# CABLE_JIG_TEST_SCH.net
KiCad netlist of a schematic drawn in Altium Designer
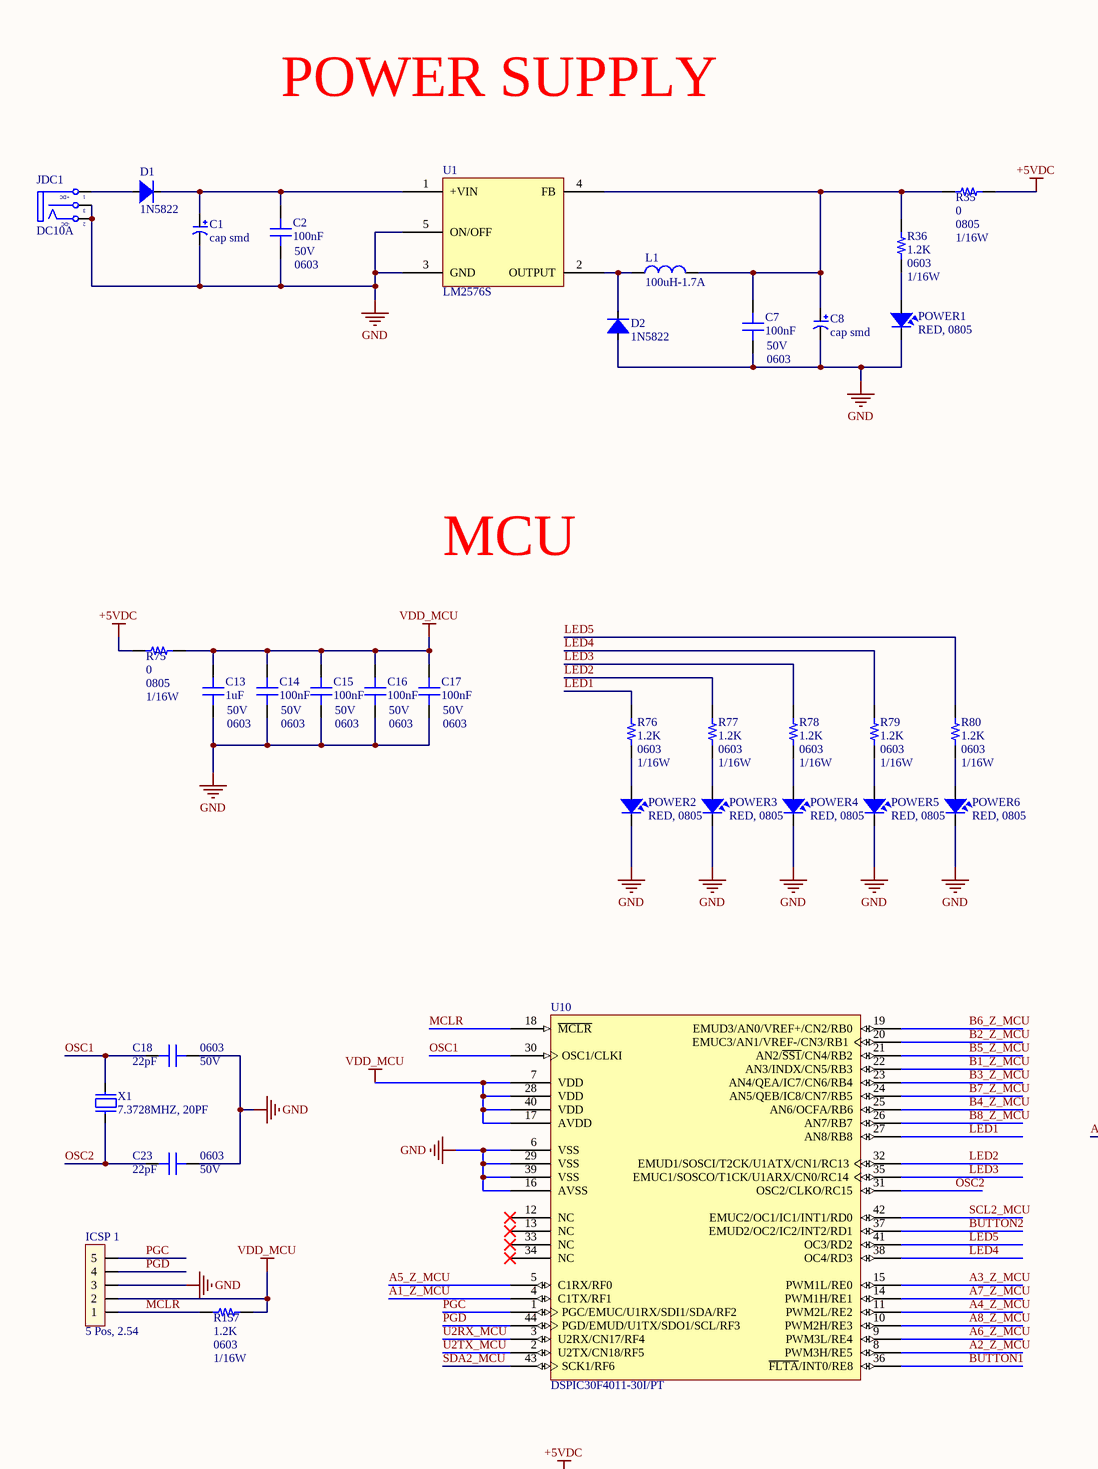
[diagram p0: CABLE_JIG_TEST_SCH.SchDoc, top left]
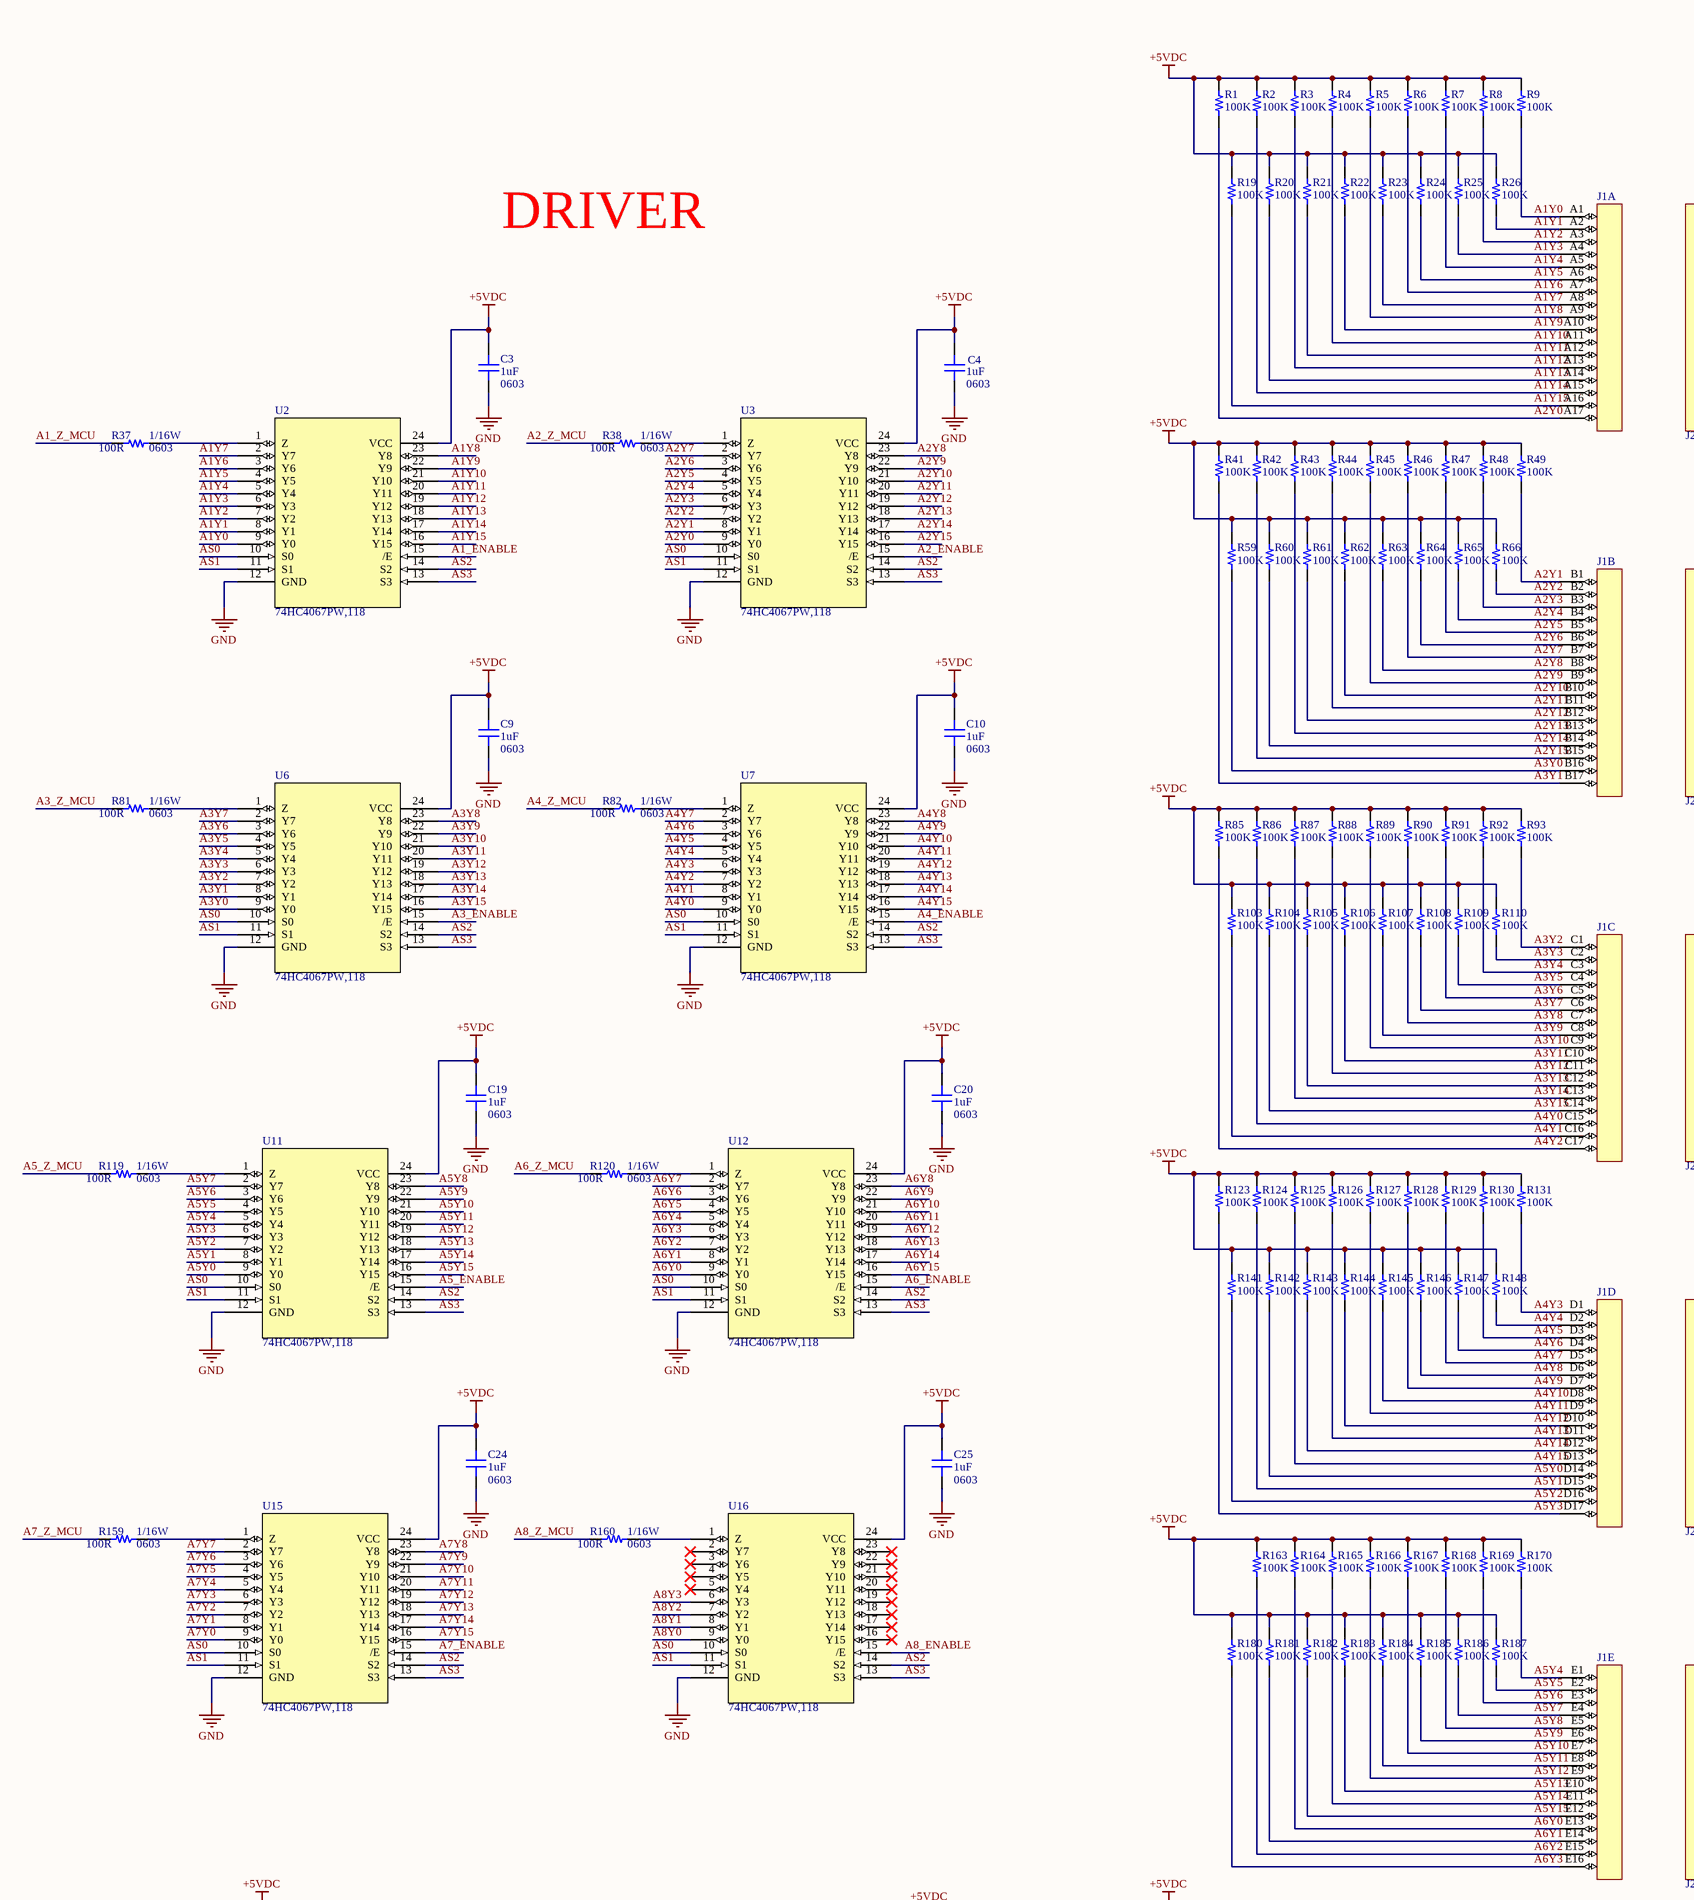
[diagram p1: CABLE_JIG_TEST_SCH.SchDoc, top middle]
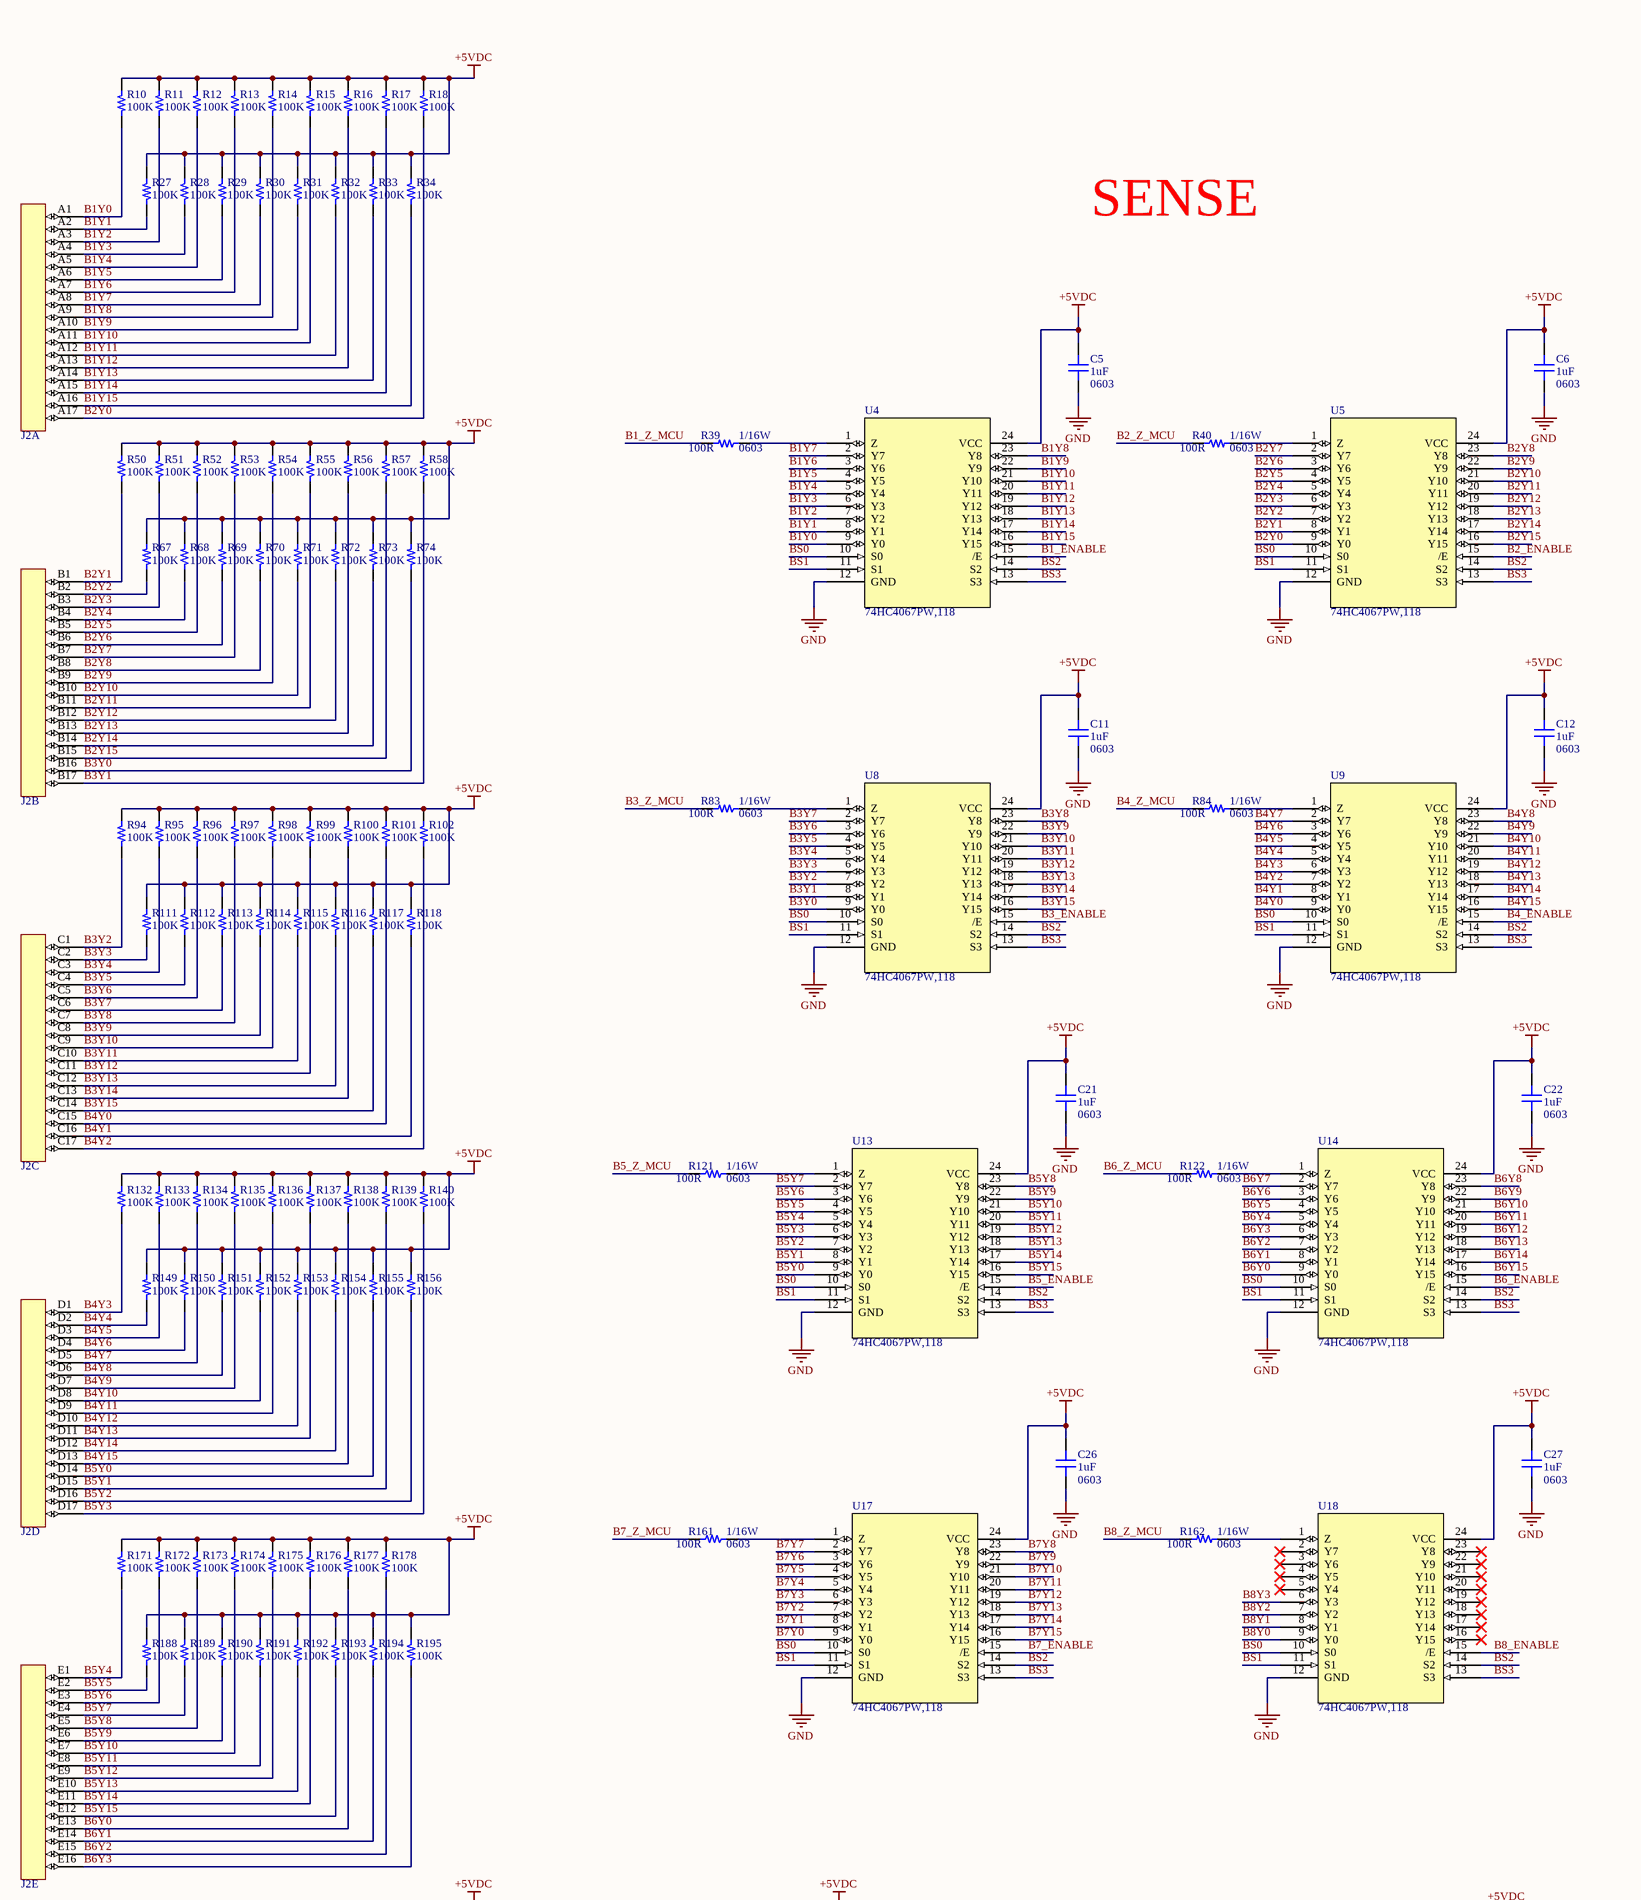
[diagram p2: CABLE_JIG_TEST_SCH.SchDoc, top right]
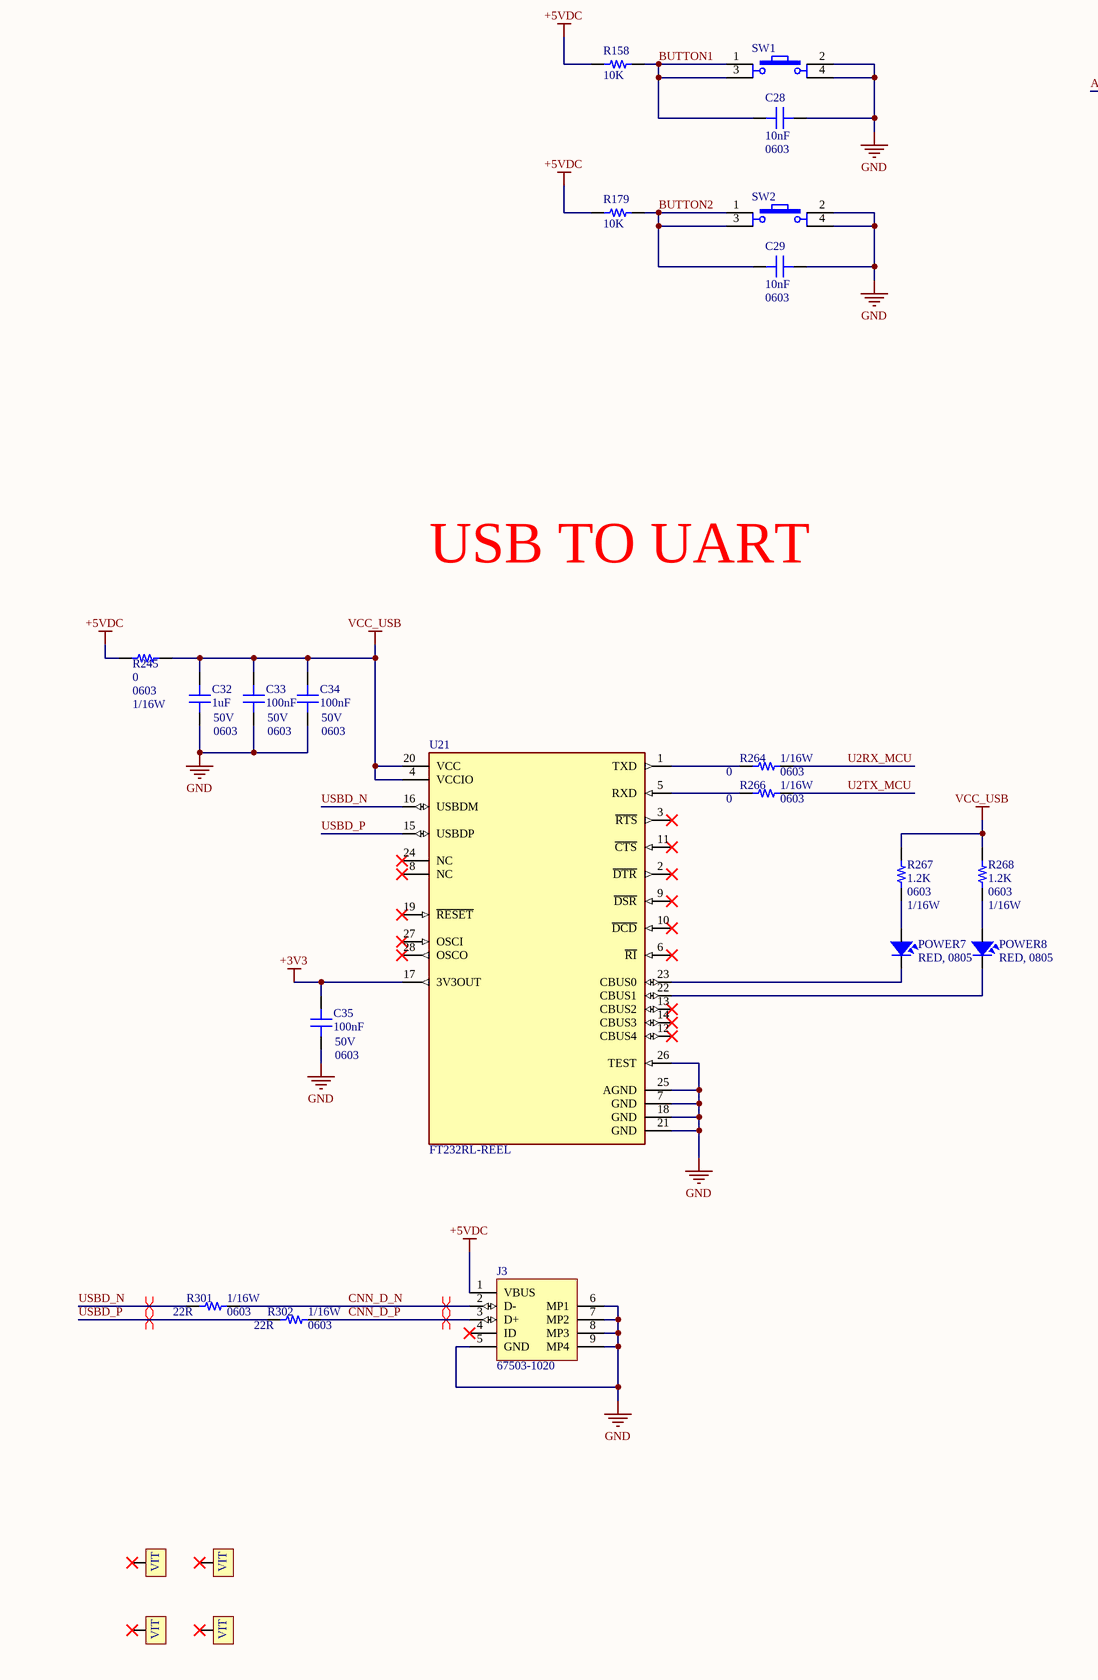
[diagram p3: CABLE_JIG_TEST_SCH.SchDoc, bottom left]
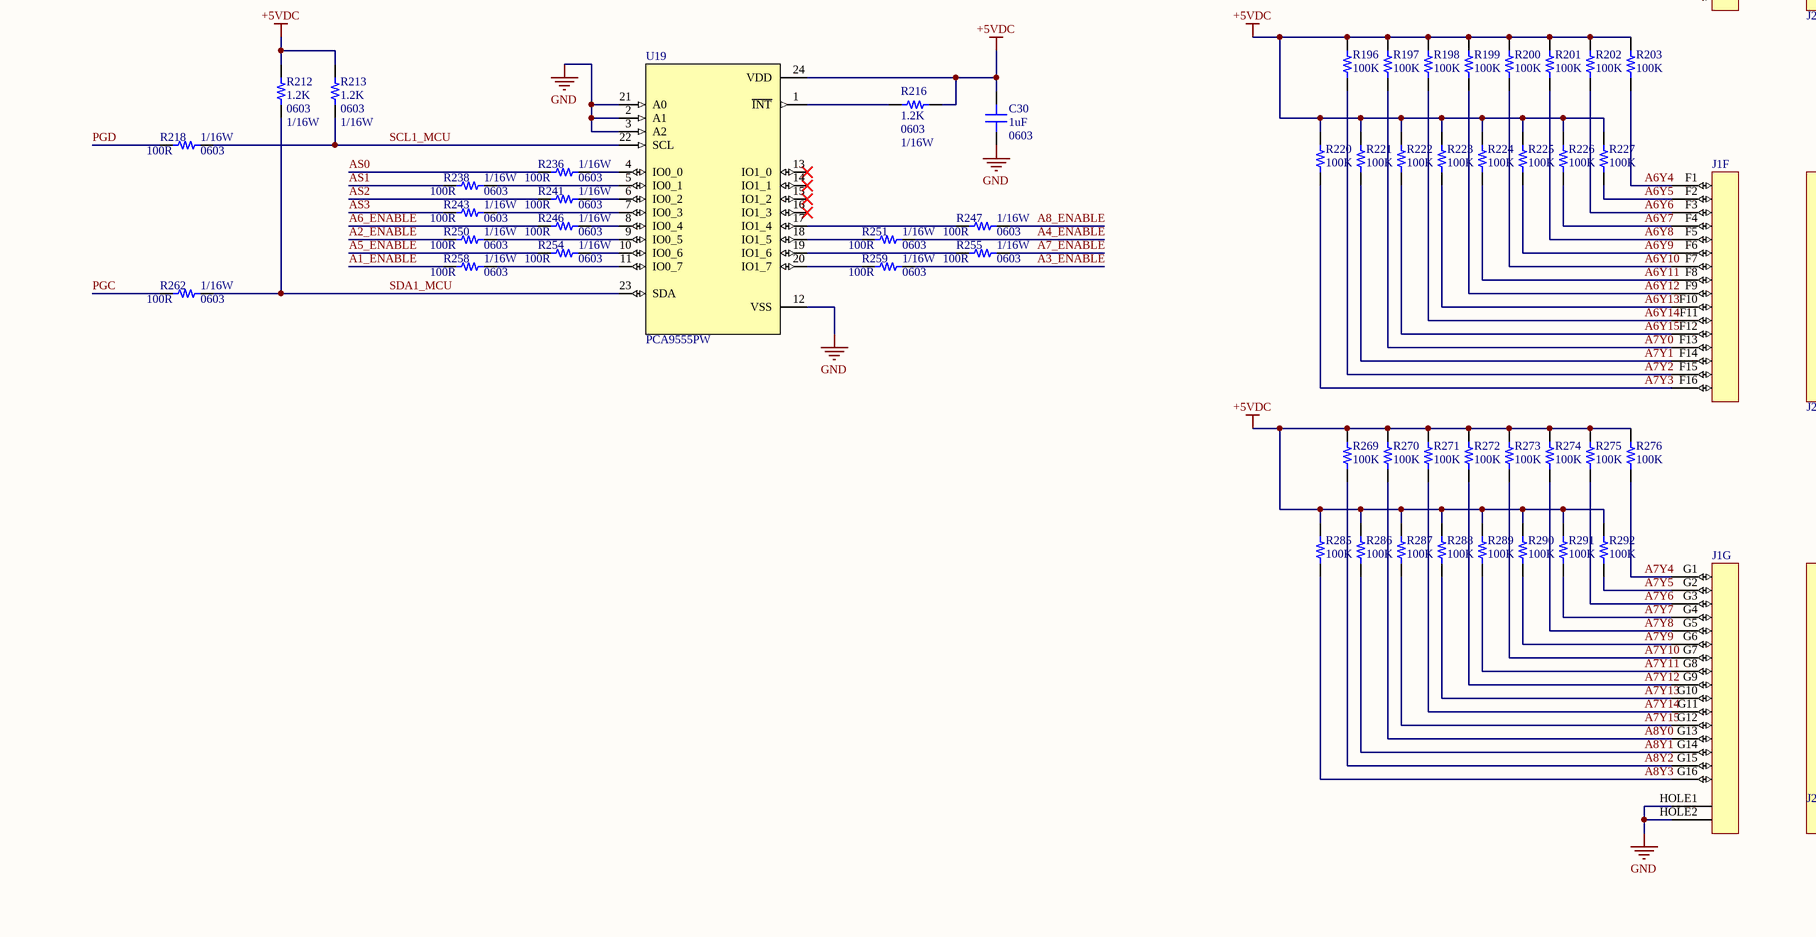
[diagram p4: CABLE_JIG_TEST_SCH.SchDoc, bottom middle]
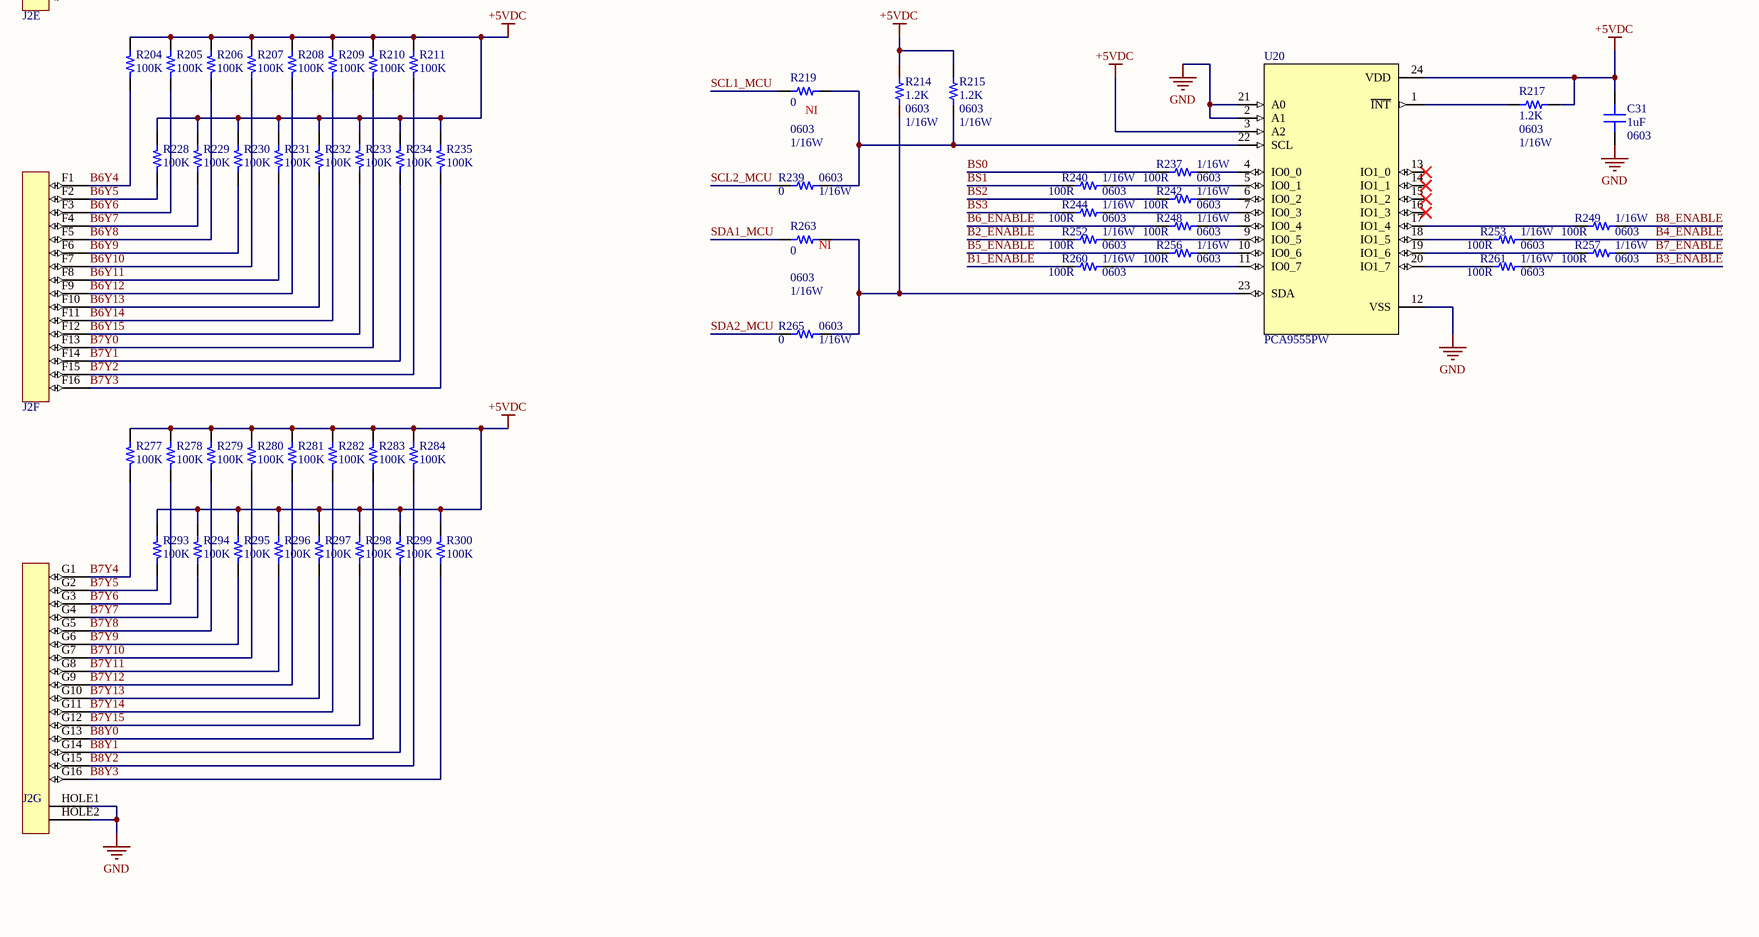
[diagram p5: CABLE_JIG_TEST_SCH.SchDoc, bottom right]

(export (version "E")
  (design (tool "Eeschema 10.0.6"))
  (components
    (comp (ref "C1")
      (value "cap smd")
      (footprint "Cap_SMD_10x10.5mm")
      (libsource (lib "DoraTek_Schematic.~(41)") (part "CAP_SMD"))
    )
    (comp (ref "C2")
      (value "100nF")
      (footprint "C0603N")
      (description "CAP CER 22UF 10V X5R 0603")
      (fields (field (name "PACKAGE") "0603") (field (name "VOLTAGE") "50V"))
      (libsource (lib "Altium_Component_Lib_Database") (part "CAP"))
    )
    (comp (ref "C3")
      (value "1uF")
      (footprint "C0603N")
      (description "CAP CER 22UF 10V X5R 0603")
      (fields (field (name "PACKAGE") "0603"))
      (libsource (lib "Altium_Component_Lib_Database") (part "CAP"))
    )
    (comp (ref "C4")
      (value "1uF")
      (footprint "C0603N")
      (description "CAP CER 22UF 10V X5R 0603")
      (fields (field (name "PACKAGE") "0603"))
      (libsource (lib "Altium_Component_Lib_Database") (part "CAP"))
    )
    (comp (ref "C5")
      (value "1uF")
      (footprint "C0603N")
      (description "CAP CER 22UF 10V X5R 0603")
      (fields (field (name "PACKAGE") "0603"))
      (libsource (lib "Altium_Component_Lib_Database") (part "CAP"))
    )
    (comp (ref "C6")
      (value "1uF")
      (footprint "C0603N")
      (description "CAP CER 22UF 10V X5R 0603")
      (fields (field (name "PACKAGE") "0603"))
      (libsource (lib "Altium_Component_Lib_Database") (part "CAP"))
    )
    (comp (ref "C7")
      (value "100nF")
      (footprint "C0603N")
      (description "CAP CER 22UF 10V X5R 0603")
      (fields (field (name "PACKAGE") "0603") (field (name "VOLTAGE") "50V"))
      (libsource (lib "Altium_Component_Lib_Database") (part "CAP"))
    )
    (comp (ref "C8")
      (value "cap smd")
      (footprint "Cap_SMD_10x10.5mm")
      (libsource (lib "DoraTek_Schematic.~(41)") (part "CAP_SMD"))
    )
    (comp (ref "C9")
      (value "1uF")
      (footprint "C0603N")
      (description "CAP CER 22UF 10V X5R 0603")
      (fields (field (name "PACKAGE") "0603"))
      (libsource (lib "Altium_Component_Lib_Database") (part "CAP"))
    )
    (comp (ref "C10")
      (value "1uF")
      (footprint "C0603N")
      (description "CAP CER 22UF 10V X5R 0603")
      (fields (field (name "PACKAGE") "0603"))
      (libsource (lib "Altium_Component_Lib_Database") (part "CAP"))
    )
    (comp (ref "C11")
      (value "1uF")
      (footprint "C0603N")
      (description "CAP CER 22UF 10V X5R 0603")
      (fields (field (name "PACKAGE") "0603"))
      (libsource (lib "Altium_Component_Lib_Database") (part "CAP"))
    )
    (comp (ref "C12")
      (value "1uF")
      (footprint "C0603N")
      (description "CAP CER 22UF 10V X5R 0603")
      (fields (field (name "PACKAGE") "0603"))
      (libsource (lib "Altium_Component_Lib_Database") (part "CAP"))
    )
    (comp (ref "C13")
      (value "1uF")
      (footprint "C0603N")
      (description "CAP CER 22UF 10V X5R 0603")
      (fields (field (name "PACKAGE") "0603") (field (name "VOLTAGE") "50V"))
      (libsource (lib "Altium_Component_Lib_Database") (part "CAP"))
    )
    (comp (ref "C14")
      (value "100nF")
      (footprint "C0603N")
      (description "CAP CER 22UF 10V X5R 0603")
      (fields (field (name "PACKAGE") "0603") (field (name "VOLTAGE") "50V"))
      (libsource (lib "Altium_Component_Lib_Database") (part "CAP"))
    )
    (comp (ref "C15")
      (value "100nF")
      (footprint "C0603N")
      (description "CAP CER 22UF 10V X5R 0603")
      (fields (field (name "PACKAGE") "0603") (field (name "VOLTAGE") "50V"))
      (libsource (lib "Altium_Component_Lib_Database") (part "CAP"))
    )
    (comp (ref "C16")
      (value "100nF")
      (footprint "C0603N")
      (description "CAP CER 22UF 10V X5R 0603")
      (fields (field (name "PACKAGE") "0603") (field (name "VOLTAGE") "50V"))
      (libsource (lib "Altium_Component_Lib_Database") (part "CAP"))
    )
    (comp (ref "C17")
      (value "100nF")
      (footprint "C0603N")
      (description "CAP CER 22UF 10V X5R 0603")
      (fields (field (name "PACKAGE") "0603") (field (name "VOLTAGE") "50V"))
      (libsource (lib "Altium_Component_Lib_Database") (part "CAP"))
    )
    (comp (ref "C18")
      (value "22pF")
      (footprint "C0603N")
      (description "CAP CER 22UF 10V X5R 0603")
      (fields (field (name "PACKAGE") "0603") (field (name "VOLTAGE") "50V"))
      (libsource (lib "Altium_Component_Lib_Database") (part "CAP"))
    )
    (comp (ref "C19")
      (value "1uF")
      (footprint "C0603N")
      (description "CAP CER 22UF 10V X5R 0603")
      (fields (field (name "PACKAGE") "0603"))
      (libsource (lib "Altium_Component_Lib_Database") (part "CAP"))
    )
    (comp (ref "C20")
      (value "1uF")
      (footprint "C0603N")
      (description "CAP CER 22UF 10V X5R 0603")
      (fields (field (name "PACKAGE") "0603"))
      (libsource (lib "Altium_Component_Lib_Database") (part "CAP"))
    )
    (comp (ref "C21")
      (value "1uF")
      (footprint "C0603N")
      (description "CAP CER 22UF 10V X5R 0603")
      (fields (field (name "PACKAGE") "0603"))
      (libsource (lib "Altium_Component_Lib_Database") (part "CAP"))
    )
    (comp (ref "C22")
      (value "1uF")
      (footprint "C0603N")
      (description "CAP CER 22UF 10V X5R 0603")
      (fields (field (name "PACKAGE") "0603"))
      (libsource (lib "Altium_Component_Lib_Database") (part "CAP"))
    )
    (comp (ref "C23")
      (value "22pF")
      (footprint "C0603N")
      (description "CAP CER 22UF 10V X5R 0603")
      (fields (field (name "PACKAGE") "0603") (field (name "VOLTAGE") "50V"))
      (libsource (lib "Altium_Component_Lib_Database") (part "CAP"))
    )
    (comp (ref "C24")
      (value "1uF")
      (footprint "C0603N")
      (description "CAP CER 22UF 10V X5R 0603")
      (fields (field (name "PACKAGE") "0603"))
      (libsource (lib "Altium_Component_Lib_Database") (part "CAP"))
    )
    (comp (ref "C25")
      (value "1uF")
      (footprint "C0603N")
      (description "CAP CER 22UF 10V X5R 0603")
      (fields (field (name "PACKAGE") "0603"))
      (libsource (lib "Altium_Component_Lib_Database") (part "CAP"))
    )
    (comp (ref "C26")
      (value "1uF")
      (footprint "C0603N")
      (description "CAP CER 22UF 10V X5R 0603")
      (fields (field (name "PACKAGE") "0603"))
      (libsource (lib "Altium_Component_Lib_Database") (part "CAP"))
    )
    (comp (ref "C27")
      (value "1uF")
      (footprint "C0603N")
      (description "CAP CER 22UF 10V X5R 0603")
      (fields (field (name "PACKAGE") "0603"))
      (libsource (lib "Altium_Component_Lib_Database") (part "CAP"))
    )
    (comp (ref "C28")
      (value "10nF")
      (footprint "C0603N")
      (description "CAP CER 22UF 10V X5R 0603")
      (fields (field (name "PACKAGE") "0603"))
      (libsource (lib "Altium_Component_Lib_Database") (part "CAP"))
    )
    (comp (ref "C29")
      (value "10nF")
      (footprint "C0603N")
      (description "CAP CER 22UF 10V X5R 0603")
      (fields (field (name "PACKAGE") "0603"))
      (libsource (lib "Altium_Component_Lib_Database") (part "CAP"))
    )
    (comp (ref "C30")
      (value "1uF")
      (footprint "C0603N")
      (description "CAP CER 22UF 10V X5R 0603")
      (fields (field (name "PACKAGE") "0603"))
      (libsource (lib "Altium_Component_Lib_Database") (part "CAP"))
    )
    (comp (ref "C31")
      (value "1uF")
      (footprint "C0603N")
      (description "CAP CER 22UF 10V X5R 0603")
      (fields (field (name "PACKAGE") "0603"))
      (libsource (lib "Altium_Component_Lib_Database") (part "CAP"))
    )
    (comp (ref "C32")
      (value "1uF")
      (footprint "C0603N")
      (description "CAP CER 22UF 10V X5R 0603")
      (fields (field (name "PACKAGE") "0603") (field (name "VOLTAGE") "50V"))
      (libsource (lib "Altium_Component_Lib_Database") (part "CAP"))
    )
    (comp (ref "C33")
      (value "100nF")
      (footprint "C0603N")
      (description "CAP CER 22UF 10V X5R 0603")
      (fields (field (name "PACKAGE") "0603") (field (name "VOLTAGE") "50V"))
      (libsource (lib "Altium_Component_Lib_Database") (part "CAP"))
    )
    (comp (ref "C34")
      (value "100nF")
      (footprint "C0603N")
      (description "CAP CER 22UF 10V X5R 0603")
      (fields (field (name "PACKAGE") "0603") (field (name "VOLTAGE") "50V"))
      (libsource (lib "Altium_Component_Lib_Database") (part "CAP"))
    )
    (comp (ref "C35")
      (value "100nF")
      (footprint "C0603N")
      (description "CAP CER 22UF 10V X5R 0603")
      (fields (field (name "PACKAGE") "0603") (field (name "VOLTAGE") "50V"))
      (libsource (lib "Altium_Component_Lib_Database") (part "CAP"))
    )
    (comp (ref "D1")
      (value "1N5822")
      (footprint "DO214 SMA")
      (description "SS34 1N5822")
      (libsource (lib "APESLAB") (part "Diode 1N5822"))
    )
    (comp (ref "D2")
      (value "1N5822")
      (footprint "DO214 SMA")
      (description "SS34 1N5822")
      (libsource (lib "APESLAB") (part "Diode 1N5822"))
    )
    (comp (ref "ICSP 1")
      (value "5 Pos, 2.54")
      (footprint "JP5")
      (description "CONN  WIRE-BOARD 5 POSITION, 2.54 mm")
      (libsource (lib "luong.nv1610") (part "3-644456-5"))
    )
    (comp (ref "J1")
      (value "CNN_CABLE_116PINS")
      (footprint "CNN_CABLE_116PINS")
      (libsource (lib "DoraTek_Schematic.~(41)") (part "CNN_CABLE_116PINS"))
    )
    (comp (ref "J2")
      (value "CNN_CABLE_116PINS")
      (footprint "CNN_CABLE_116PINS")
      (libsource (lib "") (part "CNN_CABLE_116PINS_1"))
    )
    (comp (ref "J3")
      (value "67503-1020")
      (footprint "MOLX-67503-1020_V")
      (description "USB, MINI, SMD, RA KME04-USBMU03A01")
      (fields (field (name "MANUFACTURER") "Molex"))
      (libsource (lib "DoraTek_Schematic.~(41)") (part "CNN_67503-1020"))
    )
    (comp (ref "JDC1")
      (value "DC10A")
      (footprint "DC-IN")
      (description "CLIFF ELECTRONIC COMPONENTS - DC10A - SOCKET, PCB, DC POWER, 2.1MM, PK10")
      (libsource (lib "luong.nv1610") (part "DC10A"))
    )
    (comp (ref "L1")
      (value "100uH-1.7A")
      (footprint "IND_SMD_12.5x12.5")
      (description "Inductor")
      (libsource (lib "DoraTek_Schematic.~(41)") (part "Inductor"))
    )
    (comp (ref "POWER1")
      (value "RED, 0805")
      (footprint "LED 0805")
      (description "LED, 0805, RED, 0805")
      (libsource (lib "luong.nv1610") (part "150080SS75000"))
    )
    (comp (ref "POWER2")
      (value "RED, 0805")
      (footprint "LED 0805")
      (description "LED, 0805, RED, 0805")
      (libsource (lib "luong.nv1610") (part "150080SS75000"))
    )
    (comp (ref "POWER3")
      (value "RED, 0805")
      (footprint "LED 0805")
      (description "LED, 0805, RED, 0805")
      (libsource (lib "luong.nv1610") (part "150080SS75000"))
    )
    (comp (ref "POWER4")
      (value "RED, 0805")
      (footprint "LED 0805")
      (description "LED, 0805, RED, 0805")
      (libsource (lib "luong.nv1610") (part "150080SS75000"))
    )
    (comp (ref "POWER5")
      (value "RED, 0805")
      (footprint "LED 0805")
      (description "LED, 0805, RED, 0805")
      (libsource (lib "luong.nv1610") (part "150080SS75000"))
    )
    (comp (ref "POWER6")
      (value "RED, 0805")
      (footprint "LED 0805")
      (description "LED, 0805, RED, 0805")
      (libsource (lib "luong.nv1610") (part "150080SS75000"))
    )
    (comp (ref "POWER7")
      (value "RED, 0805")
      (footprint "LED 0805")
      (description "LED, 0805, RED, 0805")
      (libsource (lib "luong.nv1610") (part "150080SS75000"))
    )
    (comp (ref "POWER8")
      (value "RED, 0805")
      (footprint "LED 0805")
      (description "LED, 0805, RED, 0805")
      (libsource (lib "luong.nv1610") (part "150080SS75000"))
    )
    (comp (ref "R1")
      (value "100K")
      (footprint "R0603N")
      (description "RES 0 OHM JUMPER 1/16W 0603")
      (fields (field (name "TOLERANCE") "Jumper"))
      (libsource (lib "Altium_Component_Lib_Database") (part "RES"))
    )
    (comp (ref "R2")
      (value "100K")
      (footprint "R0603N")
      (description "RES 0 OHM JUMPER 1/16W 0603")
      (fields (field (name "TOLERANCE") "Jumper"))
      (libsource (lib "Altium_Component_Lib_Database") (part "RES"))
    )
    (comp (ref "R3")
      (value "100K")
      (footprint "R0603N")
      (description "RES 0 OHM JUMPER 1/16W 0603")
      (fields (field (name "TOLERANCE") "Jumper"))
      (libsource (lib "Altium_Component_Lib_Database") (part "RES"))
    )
    (comp (ref "R4")
      (value "100K")
      (footprint "R0603N")
      (description "RES 0 OHM JUMPER 1/16W 0603")
      (fields (field (name "TOLERANCE") "Jumper"))
      (libsource (lib "Altium_Component_Lib_Database") (part "RES"))
    )
    (comp (ref "R5")
      (value "100K")
      (footprint "R0603N")
      (description "RES 0 OHM JUMPER 1/16W 0603")
      (fields (field (name "TOLERANCE") "Jumper"))
      (libsource (lib "Altium_Component_Lib_Database") (part "RES"))
    )
    (comp (ref "R6")
      (value "100K")
      (footprint "R0603N")
      (description "RES 0 OHM JUMPER 1/16W 0603")
      (fields (field (name "TOLERANCE") "Jumper"))
      (libsource (lib "Altium_Component_Lib_Database") (part "RES"))
    )
    (comp (ref "R7")
      (value "100K")
      (footprint "R0603N")
      (description "RES 0 OHM JUMPER 1/16W 0603")
      (fields (field (name "TOLERANCE") "Jumper"))
      (libsource (lib "Altium_Component_Lib_Database") (part "RES"))
    )
    (comp (ref "R8")
      (value "100K")
      (footprint "R0603N")
      (description "RES 0 OHM JUMPER 1/16W 0603")
      (fields (field (name "TOLERANCE") "Jumper"))
      (libsource (lib "Altium_Component_Lib_Database") (part "RES"))
    )
    (comp (ref "R9")
      (value "100K")
      (footprint "R0603N")
      (description "RES 0 OHM JUMPER 1/16W 0603")
      (fields (field (name "TOLERANCE") "Jumper"))
      (libsource (lib "Altium_Component_Lib_Database") (part "RES"))
    )
    (comp (ref "R10")
      (value "100K")
      (footprint "R0603N")
      (description "RES 0 OHM JUMPER 1/16W 0603")
      (fields (field (name "TOLERANCE") "Jumper"))
      (libsource (lib "Altium_Component_Lib_Database") (part "RES"))
    )
    (comp (ref "R11")
      (value "100K")
      (footprint "R0603N")
      (description "RES 0 OHM JUMPER 1/16W 0603")
      (fields (field (name "TOLERANCE") "Jumper"))
      (libsource (lib "Altium_Component_Lib_Database") (part "RES"))
    )
    (comp (ref "R12")
      (value "100K")
      (footprint "R0603N")
      (description "RES 0 OHM JUMPER 1/16W 0603")
      (fields (field (name "TOLERANCE") "Jumper"))
      (libsource (lib "Altium_Component_Lib_Database") (part "RES"))
    )
    (comp (ref "R13")
      (value "100K")
      (footprint "R0603N")
      (description "RES 0 OHM JUMPER 1/16W 0603")
      (fields (field (name "TOLERANCE") "Jumper"))
      (libsource (lib "Altium_Component_Lib_Database") (part "RES"))
    )
    (comp (ref "R14")
      (value "100K")
      (footprint "R0603N")
      (description "RES 0 OHM JUMPER 1/16W 0603")
      (fields (field (name "TOLERANCE") "Jumper"))
      (libsource (lib "Altium_Component_Lib_Database") (part "RES"))
    )
    (comp (ref "R15")
      (value "100K")
      (footprint "R0603N")
      (description "RES 0 OHM JUMPER 1/16W 0603")
      (fields (field (name "TOLERANCE") "Jumper"))
      (libsource (lib "Altium_Component_Lib_Database") (part "RES"))
    )
    (comp (ref "R16")
      (value "100K")
      (footprint "R0603N")
      (description "RES 0 OHM JUMPER 1/16W 0603")
      (fields (field (name "TOLERANCE") "Jumper"))
      (libsource (lib "Altium_Component_Lib_Database") (part "RES"))
    )
    (comp (ref "R17")
      (value "100K")
      (footprint "R0603N")
      (description "RES 0 OHM JUMPER 1/16W 0603")
      (fields (field (name "TOLERANCE") "Jumper"))
      (libsource (lib "Altium_Component_Lib_Database") (part "RES"))
    )
    (comp (ref "R18")
      (value "100K")
      (footprint "R0603N")
      (description "RES 0 OHM JUMPER 1/16W 0603")
      (fields (field (name "TOLERANCE") "Jumper"))
      (libsource (lib "Altium_Component_Lib_Database") (part "RES"))
    )
    (comp (ref "R19")
      (value "100K")
      (footprint "R0603N")
      (description "RES 0 OHM JUMPER 1/16W 0603")
      (fields (field (name "TOLERANCE") "Jumper"))
      (libsource (lib "Altium_Component_Lib_Database") (part "RES"))
    )
    (comp (ref "R20")
      (value "100K")
      (footprint "R0603N")
      (description "RES 0 OHM JUMPER 1/16W 0603")
      (fields (field (name "TOLERANCE") "Jumper"))
      (libsource (lib "Altium_Component_Lib_Database") (part "RES"))
    )
    (comp (ref "R21")
      (value "100K")
      (footprint "R0603N")
      (description "RES 0 OHM JUMPER 1/16W 0603")
      (fields (field (name "TOLERANCE") "Jumper"))
      (libsource (lib "Altium_Component_Lib_Database") (part "RES"))
    )
    (comp (ref "R22")
      (value "100K")
      (footprint "R0603N")
      (description "RES 0 OHM JUMPER 1/16W 0603")
      (fields (field (name "TOLERANCE") "Jumper"))
      (libsource (lib "Altium_Component_Lib_Database") (part "RES"))
    )
    (comp (ref "R23")
      (value "100K")
      (footprint "R0603N")
      (description "RES 0 OHM JUMPER 1/16W 0603")
      (fields (field (name "TOLERANCE") "Jumper"))
      (libsource (lib "Altium_Component_Lib_Database") (part "RES"))
    )
    (comp (ref "R24")
      (value "100K")
      (footprint "R0603N")
      (description "RES 0 OHM JUMPER 1/16W 0603")
      (fields (field (name "TOLERANCE") "Jumper"))
      (libsource (lib "Altium_Component_Lib_Database") (part "RES"))
    )
    (comp (ref "R25")
      (value "100K")
      (footprint "R0603N")
      (description "RES 0 OHM JUMPER 1/16W 0603")
      (fields (field (name "TOLERANCE") "Jumper"))
      (libsource (lib "Altium_Component_Lib_Database") (part "RES"))
    )
    (comp (ref "R26")
      (value "100K")
      (footprint "R0603N")
      (description "RES 0 OHM JUMPER 1/16W 0603")
      (fields (field (name "TOLERANCE") "Jumper"))
      (libsource (lib "Altium_Component_Lib_Database") (part "RES"))
    )
    (comp (ref "R27")
      (value "100K")
      (footprint "R0603N")
      (description "RES 0 OHM JUMPER 1/16W 0603")
      (fields (field (name "TOLERANCE") "Jumper"))
      (libsource (lib "Altium_Component_Lib_Database") (part "RES"))
    )
    (comp (ref "R28")
      (value "100K")
      (footprint "R0603N")
      (description "RES 0 OHM JUMPER 1/16W 0603")
      (fields (field (name "TOLERANCE") "Jumper"))
      (libsource (lib "Altium_Component_Lib_Database") (part "RES"))
    )
    (comp (ref "R29")
      (value "100K")
      (footprint "R0603N")
      (description "RES 0 OHM JUMPER 1/16W 0603")
      (fields (field (name "TOLERANCE") "Jumper"))
      (libsource (lib "Altium_Component_Lib_Database") (part "RES"))
    )
    (comp (ref "R30")
      (value "100K")
      (footprint "R0603N")
      (description "RES 0 OHM JUMPER 1/16W 0603")
      (fields (field (name "TOLERANCE") "Jumper"))
      (libsource (lib "Altium_Component_Lib_Database") (part "RES"))
    )
    (comp (ref "R31")
      (value "100K")
      (footprint "R0603N")
      (description "RES 0 OHM JUMPER 1/16W 0603")
      (fields (field (name "TOLERANCE") "Jumper"))
      (libsource (lib "Altium_Component_Lib_Database") (part "RES"))
    )
    (comp (ref "R32")
      (value "100K")
      (footprint "R0603N")
      (description "RES 0 OHM JUMPER 1/16W 0603")
      (fields (field (name "TOLERANCE") "Jumper"))
      (libsource (lib "Altium_Component_Lib_Database") (part "RES"))
    )
    (comp (ref "R33")
      (value "100K")
      (footprint "R0603N")
      (description "RES 0 OHM JUMPER 1/16W 0603")
      (fields (field (name "TOLERANCE") "Jumper"))
      (libsource (lib "Altium_Component_Lib_Database") (part "RES"))
    )
    (comp (ref "R34")
      (value "100K")
      (footprint "R0603N")
      (description "RES 0 OHM JUMPER 1/16W 0603")
      (fields (field (name "TOLERANCE") "Jumper"))
      (libsource (lib "Altium_Component_Lib_Database") (part "RES"))
    )
    (comp (ref "R35")
      (value "0")
      (footprint "R0805N")
      (description "RES 0 OHM JUMPER 1/16W 0603")
      (fields
        (field (name "PACKAGE") "0805")
        (field (name "POWER RATING") "1/16W")
        (field (name "TOLERANCE") "Jumper")
      )
      (libsource (lib "Altium_Component_Lib_Database") (part "RES"))
    )
    (comp (ref "R36")
      (value "1.2K")
      (footprint "R0603N")
      (description "RES 0 OHM JUMPER 1/16W 0603")
      (fields
        (field (name "PACKAGE") "0603")
        (field (name "POWER RATING") "1/16W")
        (field (name "TOLERANCE") "Jumper")
      )
      (libsource (lib "Altium_Component_Lib_Database") (part "RES"))
    )
    (comp (ref "R37")
      (value "100R")
      (footprint "R0603N")
      (description "RES 0 OHM JUMPER 1/16W 0603")
      (fields
        (field (name "PACKAGE") "0603")
        (field (name "POWER RATING") "1/16W")
        (field (name "TOLERANCE") "Jumper")
      )
      (libsource (lib "Altium_Component_Lib_Database") (part "RES"))
    )
    (comp (ref "R38")
      (value "100R")
      (footprint "R0603N")
      (description "RES 0 OHM JUMPER 1/16W 0603")
      (fields
        (field (name "PACKAGE") "0603")
        (field (name "POWER RATING") "1/16W")
        (field (name "TOLERANCE") "Jumper")
      )
      (libsource (lib "Altium_Component_Lib_Database") (part "RES"))
    )
    (comp (ref "R39")
      (value "100R")
      (footprint "R0603N")
      (description "RES 0 OHM JUMPER 1/16W 0603")
      (fields
        (field (name "PACKAGE") "0603")
        (field (name "POWER RATING") "1/16W")
        (field (name "TOLERANCE") "Jumper")
      )
      (libsource (lib "Altium_Component_Lib_Database") (part "RES"))
    )
    (comp (ref "R40")
      (value "100R")
      (footprint "R0603N")
      (description "RES 0 OHM JUMPER 1/16W 0603")
      (fields
        (field (name "PACKAGE") "0603")
        (field (name "POWER RATING") "1/16W")
        (field (name "TOLERANCE") "Jumper")
      )
      (libsource (lib "Altium_Component_Lib_Database") (part "RES"))
    )
    (comp (ref "R41")
      (value "100K")
      (footprint "R0603N")
      (description "RES 0 OHM JUMPER 1/16W 0603")
      (fields (field (name "TOLERANCE") "Jumper"))
      (libsource (lib "Altium_Component_Lib_Database") (part "RES"))
    )
    (comp (ref "R42")
      (value "100K")
      (footprint "R0603N")
      (description "RES 0 OHM JUMPER 1/16W 0603")
      (fields (field (name "TOLERANCE") "Jumper"))
      (libsource (lib "Altium_Component_Lib_Database") (part "RES"))
    )
    (comp (ref "R43")
      (value "100K")
      (footprint "R0603N")
      (description "RES 0 OHM JUMPER 1/16W 0603")
      (fields (field (name "TOLERANCE") "Jumper"))
      (libsource (lib "Altium_Component_Lib_Database") (part "RES"))
    )
    (comp (ref "R44")
      (value "100K")
      (footprint "R0603N")
      (description "RES 0 OHM JUMPER 1/16W 0603")
      (fields (field (name "TOLERANCE") "Jumper"))
      (libsource (lib "Altium_Component_Lib_Database") (part "RES"))
    )
    (comp (ref "R45")
      (value "100K")
      (footprint "R0603N")
      (description "RES 0 OHM JUMPER 1/16W 0603")
      (fields (field (name "TOLERANCE") "Jumper"))
      (libsource (lib "Altium_Component_Lib_Database") (part "RES"))
    )
    (comp (ref "R46")
      (value "100K")
      (footprint "R0603N")
      (description "RES 0 OHM JUMPER 1/16W 0603")
      (fields (field (name "TOLERANCE") "Jumper"))
      (libsource (lib "Altium_Component_Lib_Database") (part "RES"))
    )
    (comp (ref "R47")
      (value "100K")
      (footprint "R0603N")
      (description "RES 0 OHM JUMPER 1/16W 0603")
      (fields (field (name "TOLERANCE") "Jumper"))
      (libsource (lib "Altium_Component_Lib_Database") (part "RES"))
    )
    (comp (ref "R48")
      (value "100K")
      (footprint "R0603N")
      (description "RES 0 OHM JUMPER 1/16W 0603")
      (fields (field (name "TOLERANCE") "Jumper"))
      (libsource (lib "Altium_Component_Lib_Database") (part "RES"))
    )
    (comp (ref "R49")
      (value "100K")
      (footprint "R0603N")
      (description "RES 0 OHM JUMPER 1/16W 0603")
      (fields (field (name "TOLERANCE") "Jumper"))
      (libsource (lib "Altium_Component_Lib_Database") (part "RES"))
    )
    (comp (ref "R50")
      (value "100K")
      (footprint "R0603N")
      (description "RES 0 OHM JUMPER 1/16W 0603")
      (fields (field (name "TOLERANCE") "Jumper"))
      (libsource (lib "Altium_Component_Lib_Database") (part "RES"))
    )
    (comp (ref "R51")
      (value "100K")
      (footprint "R0603N")
      (description "RES 0 OHM JUMPER 1/16W 0603")
      (fields (field (name "TOLERANCE") "Jumper"))
      (libsource (lib "Altium_Component_Lib_Database") (part "RES"))
    )
    (comp (ref "R52")
      (value "100K")
      (footprint "R0603N")
      (description "RES 0 OHM JUMPER 1/16W 0603")
      (fields (field (name "TOLERANCE") "Jumper"))
      (libsource (lib "Altium_Component_Lib_Database") (part "RES"))
    )
    (comp (ref "R53")
      (value "100K")
      (footprint "R0603N")
      (description "RES 0 OHM JUMPER 1/16W 0603")
      (fields (field (name "TOLERANCE") "Jumper"))
      (libsource (lib "Altium_Component_Lib_Database") (part "RES"))
    )
    (comp (ref "R54")
      (value "100K")
      (footprint "R0603N")
      (description "RES 0 OHM JUMPER 1/16W 0603")
      (fields (field (name "TOLERANCE") "Jumper"))
      (libsource (lib "Altium_Component_Lib_Database") (part "RES"))
    )
    (comp (ref "R55")
      (value "100K")
      (footprint "R0603N")
      (description "RES 0 OHM JUMPER 1/16W 0603")
      (fields (field (name "TOLERANCE") "Jumper"))
      (libsource (lib "Altium_Component_Lib_Database") (part "RES"))
    )
    (comp (ref "R56")
      (value "100K")
      (footprint "R0603N")
      (description "RES 0 OHM JUMPER 1/16W 0603")
      (fields (field (name "TOLERANCE") "Jumper"))
      (libsource (lib "Altium_Component_Lib_Database") (part "RES"))
    )
    (comp (ref "R57")
      (value "100K")
      (footprint "R0603N")
      (description "RES 0 OHM JUMPER 1/16W 0603")
      (fields (field (name "TOLERANCE") "Jumper"))
      (libsource (lib "Altium_Component_Lib_Database") (part "RES"))
    )
    (comp (ref "R58")
      (value "100K")
      (footprint "R0603N")
      (description "RES 0 OHM JUMPER 1/16W 0603")
      (fields (field (name "TOLERANCE") "Jumper"))
      (libsource (lib "Altium_Component_Lib_Database") (part "RES"))
    )
    (comp (ref "R59")
      (value "100K")
      (footprint "R0603N")
      (description "RES 0 OHM JUMPER 1/16W 0603")
      (fields (field (name "TOLERANCE") "Jumper"))
      (libsource (lib "Altium_Component_Lib_Database") (part "RES"))
    )
    (comp (ref "R60")
      (value "100K")
      (footprint "R0603N")
      (description "RES 0 OHM JUMPER 1/16W 0603")
      (fields (field (name "TOLERANCE") "Jumper"))
      (libsource (lib "Altium_Component_Lib_Database") (part "RES"))
    )
    (comp (ref "R61")
      (value "100K")
      (footprint "R0603N")
      (description "RES 0 OHM JUMPER 1/16W 0603")
      (fields (field (name "TOLERANCE") "Jumper"))
      (libsource (lib "Altium_Component_Lib_Database") (part "RES"))
    )
    (comp (ref "R62")
      (value "100K")
      (footprint "R0603N")
      (description "RES 0 OHM JUMPER 1/16W 0603")
      (fields (field (name "TOLERANCE") "Jumper"))
      (libsource (lib "Altium_Component_Lib_Database") (part "RES"))
    )
    (comp (ref "R63")
      (value "100K")
      (footprint "R0603N")
      (description "RES 0 OHM JUMPER 1/16W 0603")
      (fields (field (name "TOLERANCE") "Jumper"))
      (libsource (lib "Altium_Component_Lib_Database") (part "RES"))
    )
    (comp (ref "R64")
      (value "100K")
      (footprint "R0603N")
      (description "RES 0 OHM JUMPER 1/16W 0603")
      (fields (field (name "TOLERANCE") "Jumper"))
      (libsource (lib "Altium_Component_Lib_Database") (part "RES"))
    )
    (comp (ref "R65")
      (value "100K")
      (footprint "R0603N")
      (description "RES 0 OHM JUMPER 1/16W 0603")
      (fields (field (name "TOLERANCE") "Jumper"))
      (libsource (lib "Altium_Component_Lib_Database") (part "RES"))
    )
    (comp (ref "R66")
      (value "100K")
      (footprint "R0603N")
      (description "RES 0 OHM JUMPER 1/16W 0603")
      (fields (field (name "TOLERANCE") "Jumper"))
      (libsource (lib "Altium_Component_Lib_Database") (part "RES"))
    )
    (comp (ref "R67")
      (value "100K")
      (footprint "R0603N")
      (description "RES 0 OHM JUMPER 1/16W 0603")
      (fields (field (name "TOLERANCE") "Jumper"))
      (libsource (lib "Altium_Component_Lib_Database") (part "RES"))
    )
    (comp (ref "R68")
      (value "100K")
      (footprint "R0603N")
      (description "RES 0 OHM JUMPER 1/16W 0603")
      (fields (field (name "TOLERANCE") "Jumper"))
      (libsource (lib "Altium_Component_Lib_Database") (part "RES"))
    )
    (comp (ref "R69")
      (value "100K")
      (footprint "R0603N")
      (description "RES 0 OHM JUMPER 1/16W 0603")
      (fields (field (name "TOLERANCE") "Jumper"))
      (libsource (lib "Altium_Component_Lib_Database") (part "RES"))
    )
    (comp (ref "R70")
      (value "100K")
      (footprint "R0603N")
      (description "RES 0 OHM JUMPER 1/16W 0603")
      (fields (field (name "TOLERANCE") "Jumper"))
      (libsource (lib "Altium_Component_Lib_Database") (part "RES"))
    )
    (comp (ref "R71")
      (value "100K")
      (footprint "R0603N")
      (description "RES 0 OHM JUMPER 1/16W 0603")
      (fields (field (name "TOLERANCE") "Jumper"))
      (libsource (lib "Altium_Component_Lib_Database") (part "RES"))
    )
    (comp (ref "R72")
      (value "100K")
      (footprint "R0603N")
      (description "RES 0 OHM JUMPER 1/16W 0603")
      (fields (field (name "TOLERANCE") "Jumper"))
      (libsource (lib "Altium_Component_Lib_Database") (part "RES"))
    )
    (comp (ref "R73")
      (value "100K")
      (footprint "R0603N")
      (description "RES 0 OHM JUMPER 1/16W 0603")
      (fields (field (name "TOLERANCE") "Jumper"))
      (libsource (lib "Altium_Component_Lib_Database") (part "RES"))
    )
    (comp (ref "R74")
      (value "100K")
      (footprint "R0603N")
      (description "RES 0 OHM JUMPER 1/16W 0603")
      (fields (field (name "TOLERANCE") "Jumper"))
      (libsource (lib "Altium_Component_Lib_Database") (part "RES"))
    )
    (comp (ref "R75")
      (value "0")
      (footprint "R0805N")
      (description "RES 0 OHM JUMPER 1/16W 0603")
      (fields
        (field (name "PACKAGE") "0805")
        (field (name "POWER RATING") "1/16W")
        (field (name "TOLERANCE") "Jumper")
      )
      (libsource (lib "Altium_Component_Lib_Database") (part "RES"))
    )
    (comp (ref "R76")
      (value "1.2K")
      (footprint "R0603N")
      (description "RES 0 OHM JUMPER 1/16W 0603")
      (fields
        (field (name "PACKAGE") "0603")
        (field (name "POWER RATING") "1/16W")
        (field (name "TOLERANCE") "Jumper")
      )
      (libsource (lib "Altium_Component_Lib_Database") (part "RES"))
    )
    (comp (ref "R77")
      (value "1.2K")
      (footprint "R0603N")
      (description "RES 0 OHM JUMPER 1/16W 0603")
      (fields
        (field (name "PACKAGE") "0603")
        (field (name "POWER RATING") "1/16W")
        (field (name "TOLERANCE") "Jumper")
      )
      (libsource (lib "Altium_Component_Lib_Database") (part "RES"))
    )
    (comp (ref "R78")
      (value "1.2K")
      (footprint "R0603N")
      (description "RES 0 OHM JUMPER 1/16W 0603")
      (fields
        (field (name "PACKAGE") "0603")
        (field (name "POWER RATING") "1/16W")
        (field (name "TOLERANCE") "Jumper")
      )
      (libsource (lib "Altium_Component_Lib_Database") (part "RES"))
    )
    (comp (ref "R79")
      (value "1.2K")
      (footprint "R0603N")
      (description "RES 0 OHM JUMPER 1/16W 0603")
      (fields
        (field (name "PACKAGE") "0603")
        (field (name "POWER RATING") "1/16W")
        (field (name "TOLERANCE") "Jumper")
      )
      (libsource (lib "Altium_Component_Lib_Database") (part "RES"))
    )
    (comp (ref "R80")
      (value "1.2K")
      (footprint "R0603N")
      (description "RES 0 OHM JUMPER 1/16W 0603")
      (fields
        (field (name "PACKAGE") "0603")
        (field (name "POWER RATING") "1/16W")
        (field (name "TOLERANCE") "Jumper")
      )
      (libsource (lib "Altium_Component_Lib_Database") (part "RES"))
    )
    (comp (ref "R81")
      (value "100R")
      (footprint "R0603N")
      (description "RES 0 OHM JUMPER 1/16W 0603")
      (fields
        (field (name "PACKAGE") "0603")
        (field (name "POWER RATING") "1/16W")
        (field (name "TOLERANCE") "Jumper")
      )
      (libsource (lib "Altium_Component_Lib_Database") (part "RES"))
    )
    (comp (ref "R82")
      (value "100R")
      (footprint "R0603N")
      (description "RES 0 OHM JUMPER 1/16W 0603")
      (fields
        (field (name "PACKAGE") "0603")
        (field (name "POWER RATING") "1/16W")
        (field (name "TOLERANCE") "Jumper")
      )
      (libsource (lib "Altium_Component_Lib_Database") (part "RES"))
    )
    (comp (ref "R83")
      (value "100R")
      (footprint "R0603N")
      (description "RES 0 OHM JUMPER 1/16W 0603")
      (fields
        (field (name "PACKAGE") "0603")
        (field (name "POWER RATING") "1/16W")
        (field (name "TOLERANCE") "Jumper")
      )
      (libsource (lib "Altium_Component_Lib_Database") (part "RES"))
    )
    (comp (ref "R84")
      (value "100R")
      (footprint "R0603N")
      (description "RES 0 OHM JUMPER 1/16W 0603")
      (fields
        (field (name "PACKAGE") "0603")
        (field (name "POWER RATING") "1/16W")
        (field (name "TOLERANCE") "Jumper")
      )
      (libsource (lib "Altium_Component_Lib_Database") (part "RES"))
    )
    (comp (ref "R85")
      (value "100K")
      (footprint "R0603N")
      (description "RES 0 OHM JUMPER 1/16W 0603")
      (fields (field (name "TOLERANCE") "Jumper"))
      (libsource (lib "Altium_Component_Lib_Database") (part "RES"))
    )
    (comp (ref "R86")
      (value "100K")
      (footprint "R0603N")
      (description "RES 0 OHM JUMPER 1/16W 0603")
      (fields (field (name "TOLERANCE") "Jumper"))
      (libsource (lib "Altium_Component_Lib_Database") (part "RES"))
    )
    (comp (ref "R87")
      (value "100K")
      (footprint "R0603N")
      (description "RES 0 OHM JUMPER 1/16W 0603")
      (fields (field (name "TOLERANCE") "Jumper"))
      (libsource (lib "Altium_Component_Lib_Database") (part "RES"))
    )
    (comp (ref "R88")
      (value "100K")
      (footprint "R0603N")
      (description "RES 0 OHM JUMPER 1/16W 0603")
      (fields (field (name "TOLERANCE") "Jumper"))
      (libsource (lib "Altium_Component_Lib_Database") (part "RES"))
    )
    (comp (ref "R89")
      (value "100K")
      (footprint "R0603N")
      (description "RES 0 OHM JUMPER 1/16W 0603")
      (fields (field (name "TOLERANCE") "Jumper"))
      (libsource (lib "Altium_Component_Lib_Database") (part "RES"))
    )
    (comp (ref "R90")
      (value "100K")
      (footprint "R0603N")
      (description "RES 0 OHM JUMPER 1/16W 0603")
      (fields (field (name "TOLERANCE") "Jumper"))
      (libsource (lib "Altium_Component_Lib_Database") (part "RES"))
    )
    (comp (ref "R91")
      (value "100K")
      (footprint "R0603N")
      (description "RES 0 OHM JUMPER 1/16W 0603")
      (fields (field (name "TOLERANCE") "Jumper"))
      (libsource (lib "Altium_Component_Lib_Database") (part "RES"))
    )
    (comp (ref "R92")
      (value "100K")
      (footprint "R0603N")
      (description "RES 0 OHM JUMPER 1/16W 0603")
      (fields (field (name "TOLERANCE") "Jumper"))
      (libsource (lib "Altium_Component_Lib_Database") (part "RES"))
    )
    (comp (ref "R93")
      (value "100K")
      (footprint "R0603N")
      (description "RES 0 OHM JUMPER 1/16W 0603")
      (fields (field (name "TOLERANCE") "Jumper"))
      (libsource (lib "Altium_Component_Lib_Database") (part "RES"))
    )
    (comp (ref "R94")
      (value "100K")
      (footprint "R0603N")
      (description "RES 0 OHM JUMPER 1/16W 0603")
      (fields (field (name "TOLERANCE") "Jumper"))
      (libsource (lib "Altium_Component_Lib_Database") (part "RES"))
    )
    (comp (ref "R95")
      (value "100K")
      (footprint "R0603N")
      (description "RES 0 OHM JUMPER 1/16W 0603")
      (fields (field (name "TOLERANCE") "Jumper"))
      (libsource (lib "Altium_Component_Lib_Database") (part "RES"))
    )
    (comp (ref "R96")
      (value "100K")
      (footprint "R0603N")
      (description "RES 0 OHM JUMPER 1/16W 0603")
      (fields (field (name "TOLERANCE") "Jumper"))
      (libsource (lib "Altium_Component_Lib_Database") (part "RES"))
    )
    (comp (ref "R97")
      (value "100K")
      (footprint "R0603N")
      (description "RES 0 OHM JUMPER 1/16W 0603")
      (fields (field (name "TOLERANCE") "Jumper"))
      (libsource (lib "Altium_Component_Lib_Database") (part "RES"))
    )
    (comp (ref "R98")
      (value "100K")
      (footprint "R0603N")
      (description "RES 0 OHM JUMPER 1/16W 0603")
      (fields (field (name "TOLERANCE") "Jumper"))
      (libsource (lib "Altium_Component_Lib_Database") (part "RES"))
    )
    (comp (ref "R99")
      (value "100K")
      (footprint "R0603N")
      (description "RES 0 OHM JUMPER 1/16W 0603")
      (fields (field (name "TOLERANCE") "Jumper"))
      (libsource (lib "Altium_Component_Lib_Database") (part "RES"))
    )
    (comp (ref "R100")
      (value "100K")
      (footprint "R0603N")
      (description "RES 0 OHM JUMPER 1/16W 0603")
      (fields (field (name "TOLERANCE") "Jumper"))
      (libsource (lib "Altium_Component_Lib_Database") (part "RES"))
    )
    (comp (ref "R101")
      (value "100K")
      (footprint "R0603N")
      (description "RES 0 OHM JUMPER 1/16W 0603")
      (fields (field (name "TOLERANCE") "Jumper"))
      (libsource (lib "Altium_Component_Lib_Database") (part "RES"))
    )
    (comp (ref "R102")
      (value "100K")
      (footprint "R0603N")
      (description "RES 0 OHM JUMPER 1/16W 0603")
      (fields (field (name "TOLERANCE") "Jumper"))
      (libsource (lib "Altium_Component_Lib_Database") (part "RES"))
    )
    (comp (ref "R103")
      (value "100K")
      (footprint "R0603N")
      (description "RES 0 OHM JUMPER 1/16W 0603")
      (fields (field (name "TOLERANCE") "Jumper"))
      (libsource (lib "Altium_Component_Lib_Database") (part "RES"))
    )
    (comp (ref "R104")
      (value "100K")
      (footprint "R0603N")
      (description "RES 0 OHM JUMPER 1/16W 0603")
      (fields (field (name "TOLERANCE") "Jumper"))
      (libsource (lib "Altium_Component_Lib_Database") (part "RES"))
    )
    (comp (ref "R105")
      (value "100K")
      (footprint "R0603N")
      (description "RES 0 OHM JUMPER 1/16W 0603")
      (fields (field (name "TOLERANCE") "Jumper"))
      (libsource (lib "Altium_Component_Lib_Database") (part "RES"))
    )
    (comp (ref "R106")
      (value "100K")
      (footprint "R0603N")
      (description "RES 0 OHM JUMPER 1/16W 0603")
      (fields (field (name "TOLERANCE") "Jumper"))
      (libsource (lib "Altium_Component_Lib_Database") (part "RES"))
    )
    (comp (ref "R107")
      (value "100K")
      (footprint "R0603N")
      (description "RES 0 OHM JUMPER 1/16W 0603")
      (fields (field (name "TOLERANCE") "Jumper"))
      (libsource (lib "Altium_Component_Lib_Database") (part "RES"))
    )
    (comp (ref "R108")
      (value "100K")
      (footprint "R0603N")
      (description "RES 0 OHM JUMPER 1/16W 0603")
      (fields (field (name "TOLERANCE") "Jumper"))
      (libsource (lib "Altium_Component_Lib_Database") (part "RES"))
    )
    (comp (ref "R109")
      (value "100K")
      (footprint "R0603N")
      (description "RES 0 OHM JUMPER 1/16W 0603")
      (fields (field (name "TOLERANCE") "Jumper"))
      (libsource (lib "Altium_Component_Lib_Database") (part "RES"))
    )
    (comp (ref "R110")
      (value "100K")
      (footprint "R0603N")
      (description "RES 0 OHM JUMPER 1/16W 0603")
      (fields (field (name "TOLERANCE") "Jumper"))
      (libsource (lib "Altium_Component_Lib_Database") (part "RES"))
    )
    (comp (ref "R111")
      (value "100K")
      (footprint "R0603N")
      (description "RES 0 OHM JUMPER 1/16W 0603")
      (fields (field (name "TOLERANCE") "Jumper"))
      (libsource (lib "Altium_Component_Lib_Database") (part "RES"))
    )
    (comp (ref "R112")
      (value "100K")
      (footprint "R0603N")
      (description "RES 0 OHM JUMPER 1/16W 0603")
      (fields (field (name "TOLERANCE") "Jumper"))
      (libsource (lib "Altium_Component_Lib_Database") (part "RES"))
    )
    (comp (ref "R113")
      (value "100K")
      (footprint "R0603N")
      (description "RES 0 OHM JUMPER 1/16W 0603")
      (fields (field (name "TOLERANCE") "Jumper"))
      (libsource (lib "Altium_Component_Lib_Database") (part "RES"))
    )
    (comp (ref "R114")
      (value "100K")
      (footprint "R0603N")
      (description "RES 0 OHM JUMPER 1/16W 0603")
      (fields (field (name "TOLERANCE") "Jumper"))
      (libsource (lib "Altium_Component_Lib_Database") (part "RES"))
    )
    (comp (ref "R115")
      (value "100K")
      (footprint "R0603N")
      (description "RES 0 OHM JUMPER 1/16W 0603")
      (fields (field (name "TOLERANCE") "Jumper"))
      (libsource (lib "Altium_Component_Lib_Database") (part "RES"))
    )
    (comp (ref "R116")
      (value "100K")
      (footprint "R0603N")
      (description "RES 0 OHM JUMPER 1/16W 0603")
      (fields (field (name "TOLERANCE") "Jumper"))
      (libsource (lib "Altium_Component_Lib_Database") (part "RES"))
    )
    (comp (ref "R117")
      (value "100K")
      (footprint "R0603N")
      (description "RES 0 OHM JUMPER 1/16W 0603")
      (fields (field (name "TOLERANCE") "Jumper"))
      (libsource (lib "Altium_Component_Lib_Database") (part "RES"))
    )
    (comp (ref "R118")
      (value "100K")
      (footprint "R0603N")
      (description "RES 0 OHM JUMPER 1/16W 0603")
      (fields (field (name "TOLERANCE") "Jumper"))
      (libsource (lib "Altium_Component_Lib_Database") (part "RES"))
    )
    (comp (ref "R119")
      (value "100R")
      (footprint "R0603N")
      (description "RES 0 OHM JUMPER 1/16W 0603")
      (fields
        (field (name "PACKAGE") "0603")
        (field (name "POWER RATING") "1/16W")
        (field (name "TOLERANCE") "Jumper")
      )
      (libsource (lib "Altium_Component_Lib_Database") (part "RES"))
    )
    (comp (ref "R120")
      (value "100R")
      (footprint "R0603N")
      (description "RES 0 OHM JUMPER 1/16W 0603")
      (fields
        (field (name "PACKAGE") "0603")
        (field (name "POWER RATING") "1/16W")
        (field (name "TOLERANCE") "Jumper")
      )
      (libsource (lib "Altium_Component_Lib_Database") (part "RES"))
    )
    (comp (ref "R121")
      (value "100R")
      (footprint "R0603N")
      (description "RES 0 OHM JUMPER 1/16W 0603")
      (fields
        (field (name "PACKAGE") "0603")
        (field (name "POWER RATING") "1/16W")
        (field (name "TOLERANCE") "Jumper")
      )
      (libsource (lib "Altium_Component_Lib_Database") (part "RES"))
    )
    (comp (ref "R122")
      (value "100R")
      (footprint "R0603N")
      (description "RES 0 OHM JUMPER 1/16W 0603")
      (fields
        (field (name "PACKAGE") "0603")
        (field (name "POWER RATING") "1/16W")
        (field (name "TOLERANCE") "Jumper")
      )
      (libsource (lib "Altium_Component_Lib_Database") (part "RES"))
    )
    (comp (ref "R123")
      (value "100K")
      (footprint "R0603N")
      (description "RES 0 OHM JUMPER 1/16W 0603")
      (fields (field (name "TOLERANCE") "Jumper"))
      (libsource (lib "Altium_Component_Lib_Database") (part "RES"))
    )
    (comp (ref "R124")
      (value "100K")
      (footprint "R0603N")
      (description "RES 0 OHM JUMPER 1/16W 0603")
      (fields (field (name "TOLERANCE") "Jumper"))
      (libsource (lib "Altium_Component_Lib_Database") (part "RES"))
    )
    (comp (ref "R125")
      (value "100K")
      (footprint "R0603N")
      (description "RES 0 OHM JUMPER 1/16W 0603")
      (fields (field (name "TOLERANCE") "Jumper"))
      (libsource (lib "Altium_Component_Lib_Database") (part "RES"))
    )
    (comp (ref "R126")
      (value "100K")
      (footprint "R0603N")
      (description "RES 0 OHM JUMPER 1/16W 0603")
      (fields (field (name "TOLERANCE") "Jumper"))
      (libsource (lib "Altium_Component_Lib_Database") (part "RES"))
    )
    (comp (ref "R127")
      (value "100K")
      (footprint "R0603N")
      (description "RES 0 OHM JUMPER 1/16W 0603")
      (fields (field (name "TOLERANCE") "Jumper"))
      (libsource (lib "Altium_Component_Lib_Database") (part "RES"))
    )
    (comp (ref "R128")
      (value "100K")
      (footprint "R0603N")
      (description "RES 0 OHM JUMPER 1/16W 0603")
      (fields (field (name "TOLERANCE") "Jumper"))
      (libsource (lib "Altium_Component_Lib_Database") (part "RES"))
    )
    (comp (ref "R129")
      (value "100K")
      (footprint "R0603N")
      (description "RES 0 OHM JUMPER 1/16W 0603")
      (fields (field (name "TOLERANCE") "Jumper"))
      (libsource (lib "Altium_Component_Lib_Database") (part "RES"))
    )
    (comp (ref "R130")
      (value "100K")
      (footprint "R0603N")
      (description "RES 0 OHM JUMPER 1/16W 0603")
      (fields (field (name "TOLERANCE") "Jumper"))
      (libsource (lib "Altium_Component_Lib_Database") (part "RES"))
    )
    (comp (ref "R131")
      (value "100K")
      (footprint "R0603N")
      (description "RES 0 OHM JUMPER 1/16W 0603")
      (fields (field (name "TOLERANCE") "Jumper"))
      (libsource (lib "Altium_Component_Lib_Database") (part "RES"))
    )
    (comp (ref "R132")
      (value "100K")
      (footprint "R0603N")
      (description "RES 0 OHM JUMPER 1/16W 0603")
      (fields (field (name "TOLERANCE") "Jumper"))
      (libsource (lib "Altium_Component_Lib_Database") (part "RES"))
    )
    (comp (ref "R133")
      (value "100K")
      (footprint "R0603N")
      (description "RES 0 OHM JUMPER 1/16W 0603")
      (fields (field (name "TOLERANCE") "Jumper"))
      (libsource (lib "Altium_Component_Lib_Database") (part "RES"))
    )
    (comp (ref "R134")
      (value "100K")
      (footprint "R0603N")
      (description "RES 0 OHM JUMPER 1/16W 0603")
      (fields (field (name "TOLERANCE") "Jumper"))
      (libsource (lib "Altium_Component_Lib_Database") (part "RES"))
    )
    (comp (ref "R135")
      (value "100K")
      (footprint "R0603N")
      (description "RES 0 OHM JUMPER 1/16W 0603")
      (fields (field (name "TOLERANCE") "Jumper"))
      (libsource (lib "Altium_Component_Lib_Database") (part "RES"))
    )
    (comp (ref "R136")
      (value "100K")
      (footprint "R0603N")
      (description "RES 0 OHM JUMPER 1/16W 0603")
      (fields (field (name "TOLERANCE") "Jumper"))
      (libsource (lib "Altium_Component_Lib_Database") (part "RES"))
    )
    (comp (ref "R137")
      (value "100K")
      (footprint "R0603N")
      (description "RES 0 OHM JUMPER 1/16W 0603")
      (fields (field (name "TOLERANCE") "Jumper"))
      (libsource (lib "Altium_Component_Lib_Database") (part "RES"))
    )
    (comp (ref "R138")
      (value "100K")
      (footprint "R0603N")
      (description "RES 0 OHM JUMPER 1/16W 0603")
      (fields (field (name "TOLERANCE") "Jumper"))
      (libsource (lib "Altium_Component_Lib_Database") (part "RES"))
    )
    (comp (ref "R139")
      (value "100K")
      (footprint "R0603N")
      (description "RES 0 OHM JUMPER 1/16W 0603")
      (fields (field (name "TOLERANCE") "Jumper"))
      (libsource (lib "Altium_Component_Lib_Database") (part "RES"))
    )
    (comp (ref "R140")
      (value "100K")
      (footprint "R0603N")
      (description "RES 0 OHM JUMPER 1/16W 0603")
      (fields (field (name "TOLERANCE") "Jumper"))
      (libsource (lib "Altium_Component_Lib_Database") (part "RES"))
    )
    (comp (ref "R141")
      (value "100K")
      (footprint "R0603N")
      (description "RES 0 OHM JUMPER 1/16W 0603")
      (fields (field (name "TOLERANCE") "Jumper"))
      (libsource (lib "Altium_Component_Lib_Database") (part "RES"))
    )
    (comp (ref "R142")
      (value "100K")
      (footprint "R0603N")
      (description "RES 0 OHM JUMPER 1/16W 0603")
      (fields (field (name "TOLERANCE") "Jumper"))
      (libsource (lib "Altium_Component_Lib_Database") (part "RES"))
    )
    (comp (ref "R143")
      (value "100K")
      (footprint "R0603N")
      (description "RES 0 OHM JUMPER 1/16W 0603")
      (fields (field (name "TOLERANCE") "Jumper"))
      (libsource (lib "Altium_Component_Lib_Database") (part "RES"))
    )
    (comp (ref "R144")
      (value "100K")
      (footprint "R0603N")
      (description "RES 0 OHM JUMPER 1/16W 0603")
      (fields (field (name "TOLERANCE") "Jumper"))
      (libsource (lib "Altium_Component_Lib_Database") (part "RES"))
    )
    (comp (ref "R145")
      (value "100K")
      (footprint "R0603N")
      (description "RES 0 OHM JUMPER 1/16W 0603")
      (fields (field (name "TOLERANCE") "Jumper"))
      (libsource (lib "Altium_Component_Lib_Database") (part "RES"))
    )
    (comp (ref "R146")
      (value "100K")
      (footprint "R0603N")
      (description "RES 0 OHM JUMPER 1/16W 0603")
      (fields (field (name "TOLERANCE") "Jumper"))
      (libsource (lib "Altium_Component_Lib_Database") (part "RES"))
    )
    (comp (ref "R147")
      (value "100K")
      (footprint "R0603N")
      (description "RES 0 OHM JUMPER 1/16W 0603")
      (fields (field (name "TOLERANCE") "Jumper"))
      (libsource (lib "Altium_Component_Lib_Database") (part "RES"))
    )
    (comp (ref "R148")
      (value "100K")
      (footprint "R0603N")
      (description "RES 0 OHM JUMPER 1/16W 0603")
      (fields (field (name "TOLERANCE") "Jumper"))
      (libsource (lib "Altium_Component_Lib_Database") (part "RES"))
    )
    (comp (ref "R149")
      (value "100K")
      (footprint "R0603N")
      (description "RES 0 OHM JUMPER 1/16W 0603")
      (fields (field (name "TOLERANCE") "Jumper"))
      (libsource (lib "Altium_Component_Lib_Database") (part "RES"))
    )
    (comp (ref "R150")
      (value "100K")
      (footprint "R0603N")
      (description "RES 0 OHM JUMPER 1/16W 0603")
      (fields (field (name "TOLERANCE") "Jumper"))
      (libsource (lib "Altium_Component_Lib_Database") (part "RES"))
    )
    (comp (ref "R151")
      (value "100K")
      (footprint "R0603N")
      (description "RES 0 OHM JUMPER 1/16W 0603")
      (fields (field (name "TOLERANCE") "Jumper"))
      (libsource (lib "Altium_Component_Lib_Database") (part "RES"))
    )
    (comp (ref "R152")
      (value "100K")
      (footprint "R0603N")
      (description "RES 0 OHM JUMPER 1/16W 0603")
      (fields (field (name "TOLERANCE") "Jumper"))
      (libsource (lib "Altium_Component_Lib_Database") (part "RES"))
    )
    (comp (ref "R153")
      (value "100K")
      (footprint "R0603N")
      (description "RES 0 OHM JUMPER 1/16W 0603")
      (fields (field (name "TOLERANCE") "Jumper"))
      (libsource (lib "Altium_Component_Lib_Database") (part "RES"))
    )
    (comp (ref "R154")
      (value "100K")
      (footprint "R0603N")
      (description "RES 0 OHM JUMPER 1/16W 0603")
      (fields (field (name "TOLERANCE") "Jumper"))
      (libsource (lib "Altium_Component_Lib_Database") (part "RES"))
    )
    (comp (ref "R155")
      (value "100K")
      (footprint "R0603N")
      (description "RES 0 OHM JUMPER 1/16W 0603")
      (fields (field (name "TOLERANCE") "Jumper"))
      (libsource (lib "Altium_Component_Lib_Database") (part "RES"))
    )
    (comp (ref "R156")
      (value "100K")
      (footprint "R0603N")
      (description "RES 0 OHM JUMPER 1/16W 0603")
      (fields (field (name "TOLERANCE") "Jumper"))
      (libsource (lib "Altium_Component_Lib_Database") (part "RES"))
    )
    (comp (ref "R157")
      (value "1.2K")
      (footprint "R0603N")
      (description "RES 0 OHM JUMPER 1/16W 0603")
      (fields
        (field (name "PACKAGE") "0603")
        (field (name "POWER RATING") "1/16W")
        (field (name "TOLERANCE") "Jumper")
      )
      (libsource (lib "Altium_Component_Lib_Database") (part "RES"))
    )
    (comp (ref "R158")
      (value "10K")
      (footprint "R0603N")
      (description "RES 0 OHM JUMPER 1/16W 0603")
      (fields (field (name "TOLERANCE") "Jumper"))
      (libsource (lib "Altium_Component_Lib_Database") (part "RES"))
    )
    (comp (ref "R159")
      (value "100R")
      (footprint "R0603N")
      (description "RES 0 OHM JUMPER 1/16W 0603")
      (fields
        (field (name "PACKAGE") "0603")
        (field (name "POWER RATING") "1/16W")
        (field (name "TOLERANCE") "Jumper")
      )
      (libsource (lib "Altium_Component_Lib_Database") (part "RES"))
    )
    (comp (ref "R160")
      (value "100R")
      (footprint "R0603N")
      (description "RES 0 OHM JUMPER 1/16W 0603")
      (fields
        (field (name "PACKAGE") "0603")
        (field (name "POWER RATING") "1/16W")
        (field (name "TOLERANCE") "Jumper")
      )
      (libsource (lib "Altium_Component_Lib_Database") (part "RES"))
    )
    (comp (ref "R161")
      (value "100R")
      (footprint "R0603N")
      (description "RES 0 OHM JUMPER 1/16W 0603")
      (fields
        (field (name "PACKAGE") "0603")
        (field (name "POWER RATING") "1/16W")
        (field (name "TOLERANCE") "Jumper")
      )
      (libsource (lib "Altium_Component_Lib_Database") (part "RES"))
    )
    (comp (ref "R162")
      (value "100R")
      (footprint "R0603N")
      (description "RES 0 OHM JUMPER 1/16W 0603")
      (fields
        (field (name "PACKAGE") "0603")
        (field (name "POWER RATING") "1/16W")
        (field (name "TOLERANCE") "Jumper")
      )
      (libsource (lib "Altium_Component_Lib_Database") (part "RES"))
    )
    (comp (ref "R163")
      (value "100K")
      (footprint "R0603N")
      (description "RES 0 OHM JUMPER 1/16W 0603")
      (fields (field (name "TOLERANCE") "Jumper"))
      (libsource (lib "Altium_Component_Lib_Database") (part "RES"))
    )
    (comp (ref "R164")
      (value "100K")
      (footprint "R0603N")
      (description "RES 0 OHM JUMPER 1/16W 0603")
      (fields (field (name "TOLERANCE") "Jumper"))
      (libsource (lib "Altium_Component_Lib_Database") (part "RES"))
    )
    (comp (ref "R165")
      (value "100K")
      (footprint "R0603N")
      (description "RES 0 OHM JUMPER 1/16W 0603")
      (fields (field (name "TOLERANCE") "Jumper"))
      (libsource (lib "Altium_Component_Lib_Database") (part "RES"))
    )
    (comp (ref "R166")
      (value "100K")
      (footprint "R0603N")
      (description "RES 0 OHM JUMPER 1/16W 0603")
      (fields (field (name "TOLERANCE") "Jumper"))
      (libsource (lib "Altium_Component_Lib_Database") (part "RES"))
    )
    (comp (ref "R167")
      (value "100K")
      (footprint "R0603N")
      (description "RES 0 OHM JUMPER 1/16W 0603")
      (fields (field (name "TOLERANCE") "Jumper"))
      (libsource (lib "Altium_Component_Lib_Database") (part "RES"))
    )
    (comp (ref "R168")
      (value "100K")
      (footprint "R0603N")
      (description "RES 0 OHM JUMPER 1/16W 0603")
      (fields (field (name "TOLERANCE") "Jumper"))
      (libsource (lib "Altium_Component_Lib_Database") (part "RES"))
    )
    (comp (ref "R169")
      (value "100K")
      (footprint "R0603N")
      (description "RES 0 OHM JUMPER 1/16W 0603")
      (fields (field (name "TOLERANCE") "Jumper"))
      (libsource (lib "Altium_Component_Lib_Database") (part "RES"))
    )
    (comp (ref "R170")
      (value "100K")
      (footprint "R0603N")
      (description "RES 0 OHM JUMPER 1/16W 0603")
      (fields (field (name "TOLERANCE") "Jumper"))
      (libsource (lib "Altium_Component_Lib_Database") (part "RES"))
    )
    (comp (ref "R171")
      (value "100K")
      (footprint "R0603N")
      (description "RES 0 OHM JUMPER 1/16W 0603")
      (fields (field (name "TOLERANCE") "Jumper"))
      (libsource (lib "Altium_Component_Lib_Database") (part "RES"))
    )
    (comp (ref "R172")
      (value "100K")
      (footprint "R0603N")
      (description "RES 0 OHM JUMPER 1/16W 0603")
      (fields (field (name "TOLERANCE") "Jumper"))
      (libsource (lib "Altium_Component_Lib_Database") (part "RES"))
    )
    (comp (ref "R173")
      (value "100K")
      (footprint "R0603N")
      (description "RES 0 OHM JUMPER 1/16W 0603")
      (fields (field (name "TOLERANCE") "Jumper"))
      (libsource (lib "Altium_Component_Lib_Database") (part "RES"))
    )
    (comp (ref "R174")
      (value "100K")
      (footprint "R0603N")
      (description "RES 0 OHM JUMPER 1/16W 0603")
      (fields (field (name "TOLERANCE") "Jumper"))
      (libsource (lib "Altium_Component_Lib_Database") (part "RES"))
    )
    (comp (ref "R175")
      (value "100K")
      (footprint "R0603N")
      (description "RES 0 OHM JUMPER 1/16W 0603")
      (fields (field (name "TOLERANCE") "Jumper"))
      (libsource (lib "Altium_Component_Lib_Database") (part "RES"))
    )
    (comp (ref "R176")
      (value "100K")
      (footprint "R0603N")
      (description "RES 0 OHM JUMPER 1/16W 0603")
      (fields (field (name "TOLERANCE") "Jumper"))
      (libsource (lib "Altium_Component_Lib_Database") (part "RES"))
    )
    (comp (ref "R177")
      (value "100K")
      (footprint "R0603N")
      (description "RES 0 OHM JUMPER 1/16W 0603")
      (fields (field (name "TOLERANCE") "Jumper"))
      (libsource (lib "Altium_Component_Lib_Database") (part "RES"))
    )
    (comp (ref "R178")
      (value "100K")
      (footprint "R0603N")
      (description "RES 0 OHM JUMPER 1/16W 0603")
      (fields (field (name "TOLERANCE") "Jumper"))
      (libsource (lib "Altium_Component_Lib_Database") (part "RES"))
    )
    (comp (ref "R179")
      (value "10K")
      (footprint "R0603N")
      (description "RES 0 OHM JUMPER 1/16W 0603")
      (fields (field (name "TOLERANCE") "Jumper"))
      (libsource (lib "Altium_Component_Lib_Database") (part "RES"))
    )
    (comp (ref "R180")
      (value "100K")
      (footprint "R0603N")
      (description "RES 0 OHM JUMPER 1/16W 0603")
      (fields (field (name "TOLERANCE") "Jumper"))
      (libsource (lib "Altium_Component_Lib_Database") (part "RES"))
    )
    (comp (ref "R181")
      (value "100K")
      (footprint "R0603N")
      (description "RES 0 OHM JUMPER 1/16W 0603")
      (fields (field (name "TOLERANCE") "Jumper"))
      (libsource (lib "Altium_Component_Lib_Database") (part "RES"))
    )
    (comp (ref "R182")
      (value "100K")
      (footprint "R0603N")
      (description "RES 0 OHM JUMPER 1/16W 0603")
      (fields (field (name "TOLERANCE") "Jumper"))
      (libsource (lib "Altium_Component_Lib_Database") (part "RES"))
    )
    (comp (ref "R183")
      (value "100K")
      (footprint "R0603N")
      (description "RES 0 OHM JUMPER 1/16W 0603")
      (fields (field (name "TOLERANCE") "Jumper"))
      (libsource (lib "Altium_Component_Lib_Database") (part "RES"))
    )
    (comp (ref "R184")
      (value "100K")
      (footprint "R0603N")
      (description "RES 0 OHM JUMPER 1/16W 0603")
      (fields (field (name "TOLERANCE") "Jumper"))
      (libsource (lib "Altium_Component_Lib_Database") (part "RES"))
    )
    (comp (ref "R185")
      (value "100K")
      (footprint "R0603N")
      (description "RES 0 OHM JUMPER 1/16W 0603")
      (fields (field (name "TOLERANCE") "Jumper"))
      (libsource (lib "Altium_Component_Lib_Database") (part "RES"))
    )
    (comp (ref "R186")
      (value "100K")
      (footprint "R0603N")
      (description "RES 0 OHM JUMPER 1/16W 0603")
      (fields (field (name "TOLERANCE") "Jumper"))
      (libsource (lib "Altium_Component_Lib_Database") (part "RES"))
    )
    (comp (ref "R187")
      (value "100K")
      (footprint "R0603N")
      (description "RES 0 OHM JUMPER 1/16W 0603")
      (fields (field (name "TOLERANCE") "Jumper"))
      (libsource (lib "Altium_Component_Lib_Database") (part "RES"))
    )
    (comp (ref "R188")
      (value "100K")
      (footprint "R0603N")
      (description "RES 0 OHM JUMPER 1/16W 0603")
      (fields (field (name "TOLERANCE") "Jumper"))
      (libsource (lib "Altium_Component_Lib_Database") (part "RES"))
    )
    (comp (ref "R189")
      (value "100K")
      (footprint "R0603N")
      (description "RES 0 OHM JUMPER 1/16W 0603")
      (fields (field (name "TOLERANCE") "Jumper"))
      (libsource (lib "Altium_Component_Lib_Database") (part "RES"))
    )
    (comp (ref "R190")
      (value "100K")
      (footprint "R0603N")
      (description "RES 0 OHM JUMPER 1/16W 0603")
      (fields (field (name "TOLERANCE") "Jumper"))
      (libsource (lib "Altium_Component_Lib_Database") (part "RES"))
    )
    (comp (ref "R191")
      (value "100K")
      (footprint "R0603N")
      (description "RES 0 OHM JUMPER 1/16W 0603")
      (fields (field (name "TOLERANCE") "Jumper"))
      (libsource (lib "Altium_Component_Lib_Database") (part "RES"))
    )
    (comp (ref "R192")
      (value "100K")
      (footprint "R0603N")
      (description "RES 0 OHM JUMPER 1/16W 0603")
      (fields (field (name "TOLERANCE") "Jumper"))
      (libsource (lib "Altium_Component_Lib_Database") (part "RES"))
    )
    (comp (ref "R193")
      (value "100K")
      (footprint "R0603N")
      (description "RES 0 OHM JUMPER 1/16W 0603")
      (fields (field (name "TOLERANCE") "Jumper"))
      (libsource (lib "Altium_Component_Lib_Database") (part "RES"))
    )
    (comp (ref "R194")
      (value "100K")
      (footprint "R0603N")
      (description "RES 0 OHM JUMPER 1/16W 0603")
      (fields (field (name "TOLERANCE") "Jumper"))
      (libsource (lib "Altium_Component_Lib_Database") (part "RES"))
    )
    (comp (ref "R195")
      (value "100K")
      (footprint "R0603N")
      (description "RES 0 OHM JUMPER 1/16W 0603")
      (fields (field (name "TOLERANCE") "Jumper"))
      (libsource (lib "Altium_Component_Lib_Database") (part "RES"))
    )
    (comp (ref "R196")
      (value "100K")
      (footprint "R0603N")
      (description "RES 0 OHM JUMPER 1/16W 0603")
      (fields (field (name "TOLERANCE") "Jumper"))
      (libsource (lib "Altium_Component_Lib_Database") (part "RES"))
    )
    (comp (ref "R197")
      (value "100K")
      (footprint "R0603N")
      (description "RES 0 OHM JUMPER 1/16W 0603")
      (fields (field (name "TOLERANCE") "Jumper"))
      (libsource (lib "Altium_Component_Lib_Database") (part "RES"))
    )
    (comp (ref "R198")
      (value "100K")
      (footprint "R0603N")
      (description "RES 0 OHM JUMPER 1/16W 0603")
      (fields (field (name "TOLERANCE") "Jumper"))
      (libsource (lib "Altium_Component_Lib_Database") (part "RES"))
    )
    (comp (ref "R199")
      (value "100K")
      (footprint "R0603N")
      (description "RES 0 OHM JUMPER 1/16W 0603")
      (fields (field (name "TOLERANCE") "Jumper"))
      (libsource (lib "Altium_Component_Lib_Database") (part "RES"))
    )
    (comp (ref "R200")
      (value "100K")
      (footprint "R0603N")
      (description "RES 0 OHM JUMPER 1/16W 0603")
      (fields (field (name "TOLERANCE") "Jumper"))
      (libsource (lib "Altium_Component_Lib_Database") (part "RES"))
    )
    (comp (ref "R201")
      (value "100K")
      (footprint "R0603N")
      (description "RES 0 OHM JUMPER 1/16W 0603")
      (fields (field (name "TOLERANCE") "Jumper"))
      (libsource (lib "Altium_Component_Lib_Database") (part "RES"))
    )
    (comp (ref "R202")
      (value "100K")
      (footprint "R0603N")
      (description "RES 0 OHM JUMPER 1/16W 0603")
      (fields (field (name "TOLERANCE") "Jumper"))
      (libsource (lib "Altium_Component_Lib_Database") (part "RES"))
    )
    (comp (ref "R203")
      (value "100K")
      (footprint "R0603N")
      (description "RES 0 OHM JUMPER 1/16W 0603")
      (fields (field (name "TOLERANCE") "Jumper"))
      (libsource (lib "Altium_Component_Lib_Database") (part "RES"))
    )
    (comp (ref "R204")
      (value "100K")
      (footprint "R0603N")
      (description "RES 0 OHM JUMPER 1/16W 0603")
      (fields (field (name "TOLERANCE") "Jumper"))
      (libsource (lib "Altium_Component_Lib_Database") (part "RES"))
    )
    (comp (ref "R205")
      (value "100K")
      (footprint "R0603N")
      (description "RES 0 OHM JUMPER 1/16W 0603")
      (fields (field (name "TOLERANCE") "Jumper"))
      (libsource (lib "Altium_Component_Lib_Database") (part "RES"))
    )
    (comp (ref "R206")
      (value "100K")
      (footprint "R0603N")
      (description "RES 0 OHM JUMPER 1/16W 0603")
      (fields (field (name "TOLERANCE") "Jumper"))
      (libsource (lib "Altium_Component_Lib_Database") (part "RES"))
    )
    (comp (ref "R207")
      (value "100K")
      (footprint "R0603N")
      (description "RES 0 OHM JUMPER 1/16W 0603")
      (fields (field (name "TOLERANCE") "Jumper"))
      (libsource (lib "Altium_Component_Lib_Database") (part "RES"))
    )
    (comp (ref "R208")
      (value "100K")
      (footprint "R0603N")
      (description "RES 0 OHM JUMPER 1/16W 0603")
      (fields (field (name "TOLERANCE") "Jumper"))
      (libsource (lib "Altium_Component_Lib_Database") (part "RES"))
    )
    (comp (ref "R209")
      (value "100K")
      (footprint "R0603N")
      (description "RES 0 OHM JUMPER 1/16W 0603")
      (fields (field (name "TOLERANCE") "Jumper"))
      (libsource (lib "Altium_Component_Lib_Database") (part "RES"))
    )
    (comp (ref "R210")
      (value "100K")
      (footprint "R0603N")
      (description "RES 0 OHM JUMPER 1/16W 0603")
      (fields (field (name "TOLERANCE") "Jumper"))
      (libsource (lib "Altium_Component_Lib_Database") (part "RES"))
    )
    (comp (ref "R211")
      (value "100K")
      (footprint "R0603N")
      (description "RES 0 OHM JUMPER 1/16W 0603")
      (fields (field (name "TOLERANCE") "Jumper"))
      (libsource (lib "Altium_Component_Lib_Database") (part "RES"))
    )
    (comp (ref "R212")
      (value "1.2K")
      (footprint "R0603N")
      (description "RES 0 OHM JUMPER 1/16W 0603")
      (fields
        (field (name "PACKAGE") "0603")
        (field (name "POWER RATING") "1/16W")
        (field (name "TOLERANCE") "Jumper")
      )
      (libsource (lib "Altium_Component_Lib_Database") (part "RES"))
    )
    (comp (ref "R213")
      (value "1.2K")
      (footprint "R0603N")
      (description "RES 0 OHM JUMPER 1/16W 0603")
      (fields
        (field (name "PACKAGE") "0603")
        (field (name "POWER RATING") "1/16W")
        (field (name "TOLERANCE") "Jumper")
      )
      (libsource (lib "Altium_Component_Lib_Database") (part "RES"))
    )
    (comp (ref "R214")
      (value "1.2K")
      (footprint "R0603N")
      (description "RES 0 OHM JUMPER 1/16W 0603")
      (fields
        (field (name "PACKAGE") "0603")
        (field (name "POWER RATING") "1/16W")
        (field (name "TOLERANCE") "Jumper")
      )
      (libsource (lib "Altium_Component_Lib_Database") (part "RES"))
    )
    (comp (ref "R215")
      (value "1.2K")
      (footprint "R0603N")
      (description "RES 0 OHM JUMPER 1/16W 0603")
      (fields
        (field (name "PACKAGE") "0603")
        (field (name "POWER RATING") "1/16W")
        (field (name "TOLERANCE") "Jumper")
      )
      (libsource (lib "Altium_Component_Lib_Database") (part "RES"))
    )
    (comp (ref "R216")
      (value "1.2K")
      (footprint "R0603N")
      (description "RES 0 OHM JUMPER 1/16W 0603")
      (fields
        (field (name "PACKAGE") "0603")
        (field (name "POWER RATING") "1/16W")
        (field (name "TOLERANCE") "Jumper")
      )
      (libsource (lib "Altium_Component_Lib_Database") (part "RES"))
    )
    (comp (ref "R217")
      (value "1.2K")
      (footprint "R0603N")
      (description "RES 0 OHM JUMPER 1/16W 0603")
      (fields
        (field (name "PACKAGE") "0603")
        (field (name "POWER RATING") "1/16W")
        (field (name "TOLERANCE") "Jumper")
      )
      (libsource (lib "Altium_Component_Lib_Database") (part "RES"))
    )
    (comp (ref "R218")
      (value "100R")
      (footprint "R0603N")
      (description "RES 0 OHM JUMPER 1/16W 0603")
      (fields
        (field (name "PACKAGE") "0603")
        (field (name "POWER RATING") "1/16W")
        (field (name "TOLERANCE") "Jumper")
      )
      (libsource (lib "Altium_Component_Lib_Database") (part "RES"))
    )
    (comp (ref "R219")
      (value "0")
      (footprint "R0603N")
      (description "RES 0 OHM JUMPER 1/16W 0603")
      (fields
        (field (name "NI_MARK") "NI")
        (field (name "PACKAGE") "0603")
        (field (name "POWER RATING") "1/16W")
        (field (name "TOLERANCE") "Jumper")
      )
      (libsource (lib "Altium_Component_Lib_Database") (part "RES"))
    )
    (comp (ref "R220")
      (value "100K")
      (footprint "R0603N")
      (description "RES 0 OHM JUMPER 1/16W 0603")
      (fields (field (name "TOLERANCE") "Jumper"))
      (libsource (lib "Altium_Component_Lib_Database") (part "RES"))
    )
    (comp (ref "R221")
      (value "100K")
      (footprint "R0603N")
      (description "RES 0 OHM JUMPER 1/16W 0603")
      (fields (field (name "TOLERANCE") "Jumper"))
      (libsource (lib "Altium_Component_Lib_Database") (part "RES"))
    )
    (comp (ref "R222")
      (value "100K")
      (footprint "R0603N")
      (description "RES 0 OHM JUMPER 1/16W 0603")
      (fields (field (name "TOLERANCE") "Jumper"))
      (libsource (lib "Altium_Component_Lib_Database") (part "RES"))
    )
    (comp (ref "R223")
      (value "100K")
      (footprint "R0603N")
      (description "RES 0 OHM JUMPER 1/16W 0603")
      (fields (field (name "TOLERANCE") "Jumper"))
      (libsource (lib "Altium_Component_Lib_Database") (part "RES"))
    )
    (comp (ref "R224")
      (value "100K")
      (footprint "R0603N")
      (description "RES 0 OHM JUMPER 1/16W 0603")
      (fields (field (name "TOLERANCE") "Jumper"))
      (libsource (lib "Altium_Component_Lib_Database") (part "RES"))
    )
    (comp (ref "R225")
      (value "100K")
      (footprint "R0603N")
      (description "RES 0 OHM JUMPER 1/16W 0603")
      (fields (field (name "TOLERANCE") "Jumper"))
      (libsource (lib "Altium_Component_Lib_Database") (part "RES"))
    )
    (comp (ref "R226")
      (value "100K")
      (footprint "R0603N")
      (description "RES 0 OHM JUMPER 1/16W 0603")
      (fields (field (name "TOLERANCE") "Jumper"))
      (libsource (lib "Altium_Component_Lib_Database") (part "RES"))
    )
    (comp (ref "R227")
      (value "100K")
      (footprint "R0603N")
      (description "RES 0 OHM JUMPER 1/16W 0603")
      (fields (field (name "TOLERANCE") "Jumper"))
      (libsource (lib "Altium_Component_Lib_Database") (part "RES"))
    )
    (comp (ref "R228")
      (value "100K")
      (footprint "R0603N")
      (description "RES 0 OHM JUMPER 1/16W 0603")
      (fields (field (name "TOLERANCE") "Jumper"))
      (libsource (lib "Altium_Component_Lib_Database") (part "RES"))
    )
    (comp (ref "R229")
      (value "100K")
      (footprint "R0603N")
      (description "RES 0 OHM JUMPER 1/16W 0603")
      (fields (field (name "TOLERANCE") "Jumper"))
      (libsource (lib "Altium_Component_Lib_Database") (part "RES"))
    )
    (comp (ref "R230")
      (value "100K")
      (footprint "R0603N")
      (description "RES 0 OHM JUMPER 1/16W 0603")
      (fields (field (name "TOLERANCE") "Jumper"))
      (libsource (lib "Altium_Component_Lib_Database") (part "RES"))
    )
    (comp (ref "R231")
      (value "100K")
      (footprint "R0603N")
      (description "RES 0 OHM JUMPER 1/16W 0603")
      (fields (field (name "TOLERANCE") "Jumper"))
      (libsource (lib "Altium_Component_Lib_Database") (part "RES"))
    )
    (comp (ref "R232")
      (value "100K")
      (footprint "R0603N")
      (description "RES 0 OHM JUMPER 1/16W 0603")
      (fields (field (name "TOLERANCE") "Jumper"))
      (libsource (lib "Altium_Component_Lib_Database") (part "RES"))
    )
    (comp (ref "R233")
      (value "100K")
      (footprint "R0603N")
      (description "RES 0 OHM JUMPER 1/16W 0603")
      (fields (field (name "TOLERANCE") "Jumper"))
      (libsource (lib "Altium_Component_Lib_Database") (part "RES"))
    )
    (comp (ref "R234")
      (value "100K")
      (footprint "R0603N")
      (description "RES 0 OHM JUMPER 1/16W 0603")
      (fields (field (name "TOLERANCE") "Jumper"))
      (libsource (lib "Altium_Component_Lib_Database") (part "RES"))
    )
    (comp (ref "R235")
      (value "100K")
      (footprint "R0603N")
      (description "RES 0 OHM JUMPER 1/16W 0603")
      (fields (field (name "TOLERANCE") "Jumper"))
      (libsource (lib "Altium_Component_Lib_Database") (part "RES"))
    )
    (comp (ref "R236")
      (value "100R")
      (footprint "R0603N")
      (description "RES 0 OHM JUMPER 1/16W 0603")
      (fields
        (field (name "PACKAGE") "0603")
        (field (name "POWER RATING") "1/16W")
        (field (name "TOLERANCE") "Jumper")
      )
      (libsource (lib "Altium_Component_Lib_Database") (part "RES"))
    )
    (comp (ref "R237")
      (value "100R")
      (footprint "R0603N")
      (description "RES 0 OHM JUMPER 1/16W 0603")
      (fields
        (field (name "PACKAGE") "0603")
        (field (name "POWER RATING") "1/16W")
        (field (name "TOLERANCE") "Jumper")
      )
      (libsource (lib "Altium_Component_Lib_Database") (part "RES"))
    )
    (comp (ref "R238")
      (value "100R")
      (footprint "R0603N")
      (description "RES 0 OHM JUMPER 1/16W 0603")
      (fields
        (field (name "PACKAGE") "0603")
        (field (name "POWER RATING") "1/16W")
        (field (name "TOLERANCE") "Jumper")
      )
      (libsource (lib "Altium_Component_Lib_Database") (part "RES"))
    )
    (comp (ref "R239")
      (value "0")
      (footprint "R0603N")
      (description "RES 0 OHM JUMPER 1/16W 0603")
      (fields
        (field (name "PACKAGE") "0603")
        (field (name "POWER RATING") "1/16W")
        (field (name "TOLERANCE") "Jumper")
      )
      (libsource (lib "Altium_Component_Lib_Database") (part "RES"))
    )
    (comp (ref "R240")
      (value "100R")
      (footprint "R0603N")
      (description "RES 0 OHM JUMPER 1/16W 0603")
      (fields
        (field (name "PACKAGE") "0603")
        (field (name "POWER RATING") "1/16W")
        (field (name "TOLERANCE") "Jumper")
      )
      (libsource (lib "Altium_Component_Lib_Database") (part "RES"))
    )
    (comp (ref "R241")
      (value "100R")
      (footprint "R0603N")
      (description "RES 0 OHM JUMPER 1/16W 0603")
      (fields
        (field (name "PACKAGE") "0603")
        (field (name "POWER RATING") "1/16W")
        (field (name "TOLERANCE") "Jumper")
      )
      (libsource (lib "Altium_Component_Lib_Database") (part "RES"))
    )
    (comp (ref "R242")
      (value "100R")
      (footprint "R0603N")
      (description "RES 0 OHM JUMPER 1/16W 0603")
      (fields
        (field (name "PACKAGE") "0603")
        (field (name "POWER RATING") "1/16W")
        (field (name "TOLERANCE") "Jumper")
      )
      (libsource (lib "Altium_Component_Lib_Database") (part "RES"))
    )
    (comp (ref "R243")
      (value "100R")
      (footprint "R0603N")
      (description "RES 0 OHM JUMPER 1/16W 0603")
      (fields
        (field (name "PACKAGE") "0603")
        (field (name "POWER RATING") "1/16W")
        (field (name "TOLERANCE") "Jumper")
      )
      (libsource (lib "Altium_Component_Lib_Database") (part "RES"))
    )
    (comp (ref "R244")
      (value "100R")
      (footprint "R0603N")
      (description "RES 0 OHM JUMPER 1/16W 0603")
      (fields
        (field (name "PACKAGE") "0603")
        (field (name "POWER RATING") "1/16W")
        (field (name "TOLERANCE") "Jumper")
      )
      (libsource (lib "Altium_Component_Lib_Database") (part "RES"))
    )
    (comp (ref "R245")
      (value "0")
      (footprint "R0603N")
      (description "RES 0 OHM JUMPER 1/16W 0603")
      (fields
        (field (name "PACKAGE") "0603")
        (field (name "POWER RATING") "1/16W")
        (field (name "TOLERANCE") "Jumper")
      )
      (libsource (lib "Altium_Component_Lib_Database") (part "RES"))
    )
    (comp (ref "R246")
      (value "100R")
      (footprint "R0603N")
      (description "RES 0 OHM JUMPER 1/16W 0603")
      (fields
        (field (name "PACKAGE") "0603")
        (field (name "POWER RATING") "1/16W")
        (field (name "TOLERANCE") "Jumper")
      )
      (libsource (lib "Altium_Component_Lib_Database") (part "RES"))
    )
    (comp (ref "R247")
      (value "100R")
      (footprint "R0603N")
      (description "RES 0 OHM JUMPER 1/16W 0603")
      (fields
        (field (name "PACKAGE") "0603")
        (field (name "POWER RATING") "1/16W")
        (field (name "TOLERANCE") "Jumper")
      )
      (libsource (lib "Altium_Component_Lib_Database") (part "RES"))
    )
    (comp (ref "R248")
      (value "100R")
      (footprint "R0603N")
      (description "RES 0 OHM JUMPER 1/16W 0603")
      (fields
        (field (name "PACKAGE") "0603")
        (field (name "POWER RATING") "1/16W")
        (field (name "TOLERANCE") "Jumper")
      )
      (libsource (lib "Altium_Component_Lib_Database") (part "RES"))
    )
    (comp (ref "R249")
      (value "100R")
      (footprint "R0603N")
      (description "RES 0 OHM JUMPER 1/16W 0603")
      (fields
        (field (name "PACKAGE") "0603")
        (field (name "POWER RATING") "1/16W")
        (field (name "TOLERANCE") "Jumper")
      )
      (libsource (lib "Altium_Component_Lib_Database") (part "RES"))
    )
    (comp (ref "R250")
      (value "100R")
      (footprint "R0603N")
      (description "RES 0 OHM JUMPER 1/16W 0603")
      (fields
        (field (name "PACKAGE") "0603")
        (field (name "POWER RATING") "1/16W")
        (field (name "TOLERANCE") "Jumper")
      )
      (libsource (lib "Altium_Component_Lib_Database") (part "RES"))
    )
    (comp (ref "R251")
      (value "100R")
      (footprint "R0603N")
      (description "RES 0 OHM JUMPER 1/16W 0603")
      (fields
        (field (name "PACKAGE") "0603")
        (field (name "POWER RATING") "1/16W")
        (field (name "TOLERANCE") "Jumper")
      )
      (libsource (lib "Altium_Component_Lib_Database") (part "RES"))
    )
    (comp (ref "R252")
      (value "100R")
      (footprint "R0603N")
      (description "RES 0 OHM JUMPER 1/16W 0603")
      (fields
        (field (name "PACKAGE") "0603")
        (field (name "POWER RATING") "1/16W")
        (field (name "TOLERANCE") "Jumper")
      )
      (libsource (lib "Altium_Component_Lib_Database") (part "RES"))
    )
    (comp (ref "R253")
      (value "100R")
      (footprint "R0603N")
      (description "RES 0 OHM JUMPER 1/16W 0603")
      (fields
        (field (name "PACKAGE") "0603")
        (field (name "POWER RATING") "1/16W")
        (field (name "TOLERANCE") "Jumper")
      )
      (libsource (lib "Altium_Component_Lib_Database") (part "RES"))
    )
    (comp (ref "R254")
      (value "100R")
      (footprint "R0603N")
      (description "RES 0 OHM JUMPER 1/16W 0603")
      (fields
        (field (name "PACKAGE") "0603")
        (field (name "POWER RATING") "1/16W")
        (field (name "TOLERANCE") "Jumper")
      )
      (libsource (lib "Altium_Component_Lib_Database") (part "RES"))
    )
    (comp (ref "R255")
      (value "100R")
      (footprint "R0603N")
      (description "RES 0 OHM JUMPER 1/16W 0603")
      (fields
        (field (name "PACKAGE") "0603")
        (field (name "POWER RATING") "1/16W")
        (field (name "TOLERANCE") "Jumper")
      )
      (libsource (lib "Altium_Component_Lib_Database") (part "RES"))
    )
    (comp (ref "R256")
      (value "100R")
      (footprint "R0603N")
      (description "RES 0 OHM JUMPER 1/16W 0603")
      (fields
        (field (name "PACKAGE") "0603")
        (field (name "POWER RATING") "1/16W")
        (field (name "TOLERANCE") "Jumper")
      )
      (libsource (lib "Altium_Component_Lib_Database") (part "RES"))
    )
    (comp (ref "R257")
      (value "100R")
      (footprint "R0603N")
      (description "RES 0 OHM JUMPER 1/16W 0603")
      (fields
        (field (name "PACKAGE") "0603")
        (field (name "POWER RATING") "1/16W")
        (field (name "TOLERANCE") "Jumper")
      )
      (libsource (lib "Altium_Component_Lib_Database") (part "RES"))
    )
    (comp (ref "R258")
      (value "100R")
      (footprint "R0603N")
      (description "RES 0 OHM JUMPER 1/16W 0603")
      (fields
        (field (name "PACKAGE") "0603")
        (field (name "POWER RATING") "1/16W")
        (field (name "TOLERANCE") "Jumper")
      )
      (libsource (lib "Altium_Component_Lib_Database") (part "RES"))
    )
    (comp (ref "R259")
      (value "100R")
      (footprint "R0603N")
      (description "RES 0 OHM JUMPER 1/16W 0603")
      (fields
        (field (name "PACKAGE") "0603")
        (field (name "POWER RATING") "1/16W")
        (field (name "TOLERANCE") "Jumper")
      )
      (libsource (lib "Altium_Component_Lib_Database") (part "RES"))
    )
    (comp (ref "R260")
      (value "100R")
      (footprint "R0603N")
      (description "RES 0 OHM JUMPER 1/16W 0603")
      (fields
        (field (name "PACKAGE") "0603")
        (field (name "POWER RATING") "1/16W")
        (field (name "TOLERANCE") "Jumper")
      )
      (libsource (lib "Altium_Component_Lib_Database") (part "RES"))
    )
    (comp (ref "R261")
      (value "100R")
      (footprint "R0603N")
      (description "RES 0 OHM JUMPER 1/16W 0603")
      (fields
        (field (name "PACKAGE") "0603")
        (field (name "POWER RATING") "1/16W")
        (field (name "TOLERANCE") "Jumper")
      )
      (libsource (lib "Altium_Component_Lib_Database") (part "RES"))
    )
    (comp (ref "R262")
      (value "100R")
      (footprint "R0603N")
      (description "RES 0 OHM JUMPER 1/16W 0603")
      (fields
        (field (name "PACKAGE") "0603")
        (field (name "POWER RATING") "1/16W")
        (field (name "TOLERANCE") "Jumper")
      )
      (libsource (lib "Altium_Component_Lib_Database") (part "RES"))
    )
    (comp (ref "R263")
      (value "0")
      (footprint "R0603N")
      (description "RES 0 OHM JUMPER 1/16W 0603")
      (fields
        (field (name "NI_MARK") "NI")
        (field (name "PACKAGE") "0603")
        (field (name "POWER RATING") "1/16W")
        (field (name "TOLERANCE") "Jumper")
      )
      (libsource (lib "Altium_Component_Lib_Database") (part "RES"))
    )
    (comp (ref "R264")
      (value "0")
      (footprint "R0603N")
      (description "RES 0 OHM JUMPER 1/16W 0603")
      (fields
        (field (name "PACKAGE") "0603")
        (field (name "POWER RATING") "1/16W")
        (field (name "TOLERANCE") "Jumper")
      )
      (libsource (lib "Altium_Component_Lib_Database") (part "RES"))
    )
    (comp (ref "R265")
      (value "0")
      (footprint "R0603N")
      (description "RES 0 OHM JUMPER 1/16W 0603")
      (fields
        (field (name "PACKAGE") "0603")
        (field (name "POWER RATING") "1/16W")
        (field (name "TOLERANCE") "Jumper")
      )
      (libsource (lib "Altium_Component_Lib_Database") (part "RES"))
    )
    (comp (ref "R266")
      (value "0")
      (footprint "R0603N")
      (description "RES 0 OHM JUMPER 1/16W 0603")
      (fields
        (field (name "PACKAGE") "0603")
        (field (name "POWER RATING") "1/16W")
        (field (name "TOLERANCE") "Jumper")
      )
      (libsource (lib "Altium_Component_Lib_Database") (part "RES"))
    )
    (comp (ref "R267")
      (value "1.2K")
      (footprint "R0603N")
      (description "RES 0 OHM JUMPER 1/16W 0603")
      (fields
        (field (name "PACKAGE") "0603")
        (field (name "POWER RATING") "1/16W")
        (field (name "TOLERANCE") "Jumper")
      )
      (libsource (lib "Altium_Component_Lib_Database") (part "RES"))
    )
    (comp (ref "R268")
      (value "1.2K")
      (footprint "R0603N")
      (description "RES 0 OHM JUMPER 1/16W 0603")
      (fields
        (field (name "PACKAGE") "0603")
        (field (name "POWER RATING") "1/16W")
        (field (name "TOLERANCE") "Jumper")
      )
      (libsource (lib "Altium_Component_Lib_Database") (part "RES"))
    )
    (comp (ref "R269")
      (value "100K")
      (footprint "R0603N")
      (description "RES 0 OHM JUMPER 1/16W 0603")
      (fields (field (name "TOLERANCE") "Jumper"))
      (libsource (lib "Altium_Component_Lib_Database") (part "RES"))
    )
    (comp (ref "R270")
      (value "100K")
      (footprint "R0603N")
      (description "RES 0 OHM JUMPER 1/16W 0603")
      (fields (field (name "TOLERANCE") "Jumper"))
      (libsource (lib "Altium_Component_Lib_Database") (part "RES"))
    )
    (comp (ref "R271")
      (value "100K")
      (footprint "R0603N")
      (description "RES 0 OHM JUMPER 1/16W 0603")
      (fields (field (name "TOLERANCE") "Jumper"))
      (libsource (lib "Altium_Component_Lib_Database") (part "RES"))
    )
    (comp (ref "R272")
      (value "100K")
      (footprint "R0603N")
      (description "RES 0 OHM JUMPER 1/16W 0603")
      (fields (field (name "TOLERANCE") "Jumper"))
      (libsource (lib "Altium_Component_Lib_Database") (part "RES"))
    )
    (comp (ref "R273")
      (value "100K")
      (footprint "R0603N")
      (description "RES 0 OHM JUMPER 1/16W 0603")
      (fields (field (name "TOLERANCE") "Jumper"))
      (libsource (lib "Altium_Component_Lib_Database") (part "RES"))
    )
    (comp (ref "R274")
      (value "100K")
      (footprint "R0603N")
      (description "RES 0 OHM JUMPER 1/16W 0603")
      (fields (field (name "TOLERANCE") "Jumper"))
      (libsource (lib "Altium_Component_Lib_Database") (part "RES"))
    )
    (comp (ref "R275")
      (value "100K")
      (footprint "R0603N")
      (description "RES 0 OHM JUMPER 1/16W 0603")
      (fields (field (name "TOLERANCE") "Jumper"))
      (libsource (lib "Altium_Component_Lib_Database") (part "RES"))
    )
    (comp (ref "R276")
      (value "100K")
      (footprint "R0603N")
      (description "RES 0 OHM JUMPER 1/16W 0603")
      (fields (field (name "TOLERANCE") "Jumper"))
      (libsource (lib "Altium_Component_Lib_Database") (part "RES"))
    )
    (comp (ref "R277")
      (value "100K")
      (footprint "R0603N")
      (description "RES 0 OHM JUMPER 1/16W 0603")
      (fields (field (name "TOLERANCE") "Jumper"))
      (libsource (lib "Altium_Component_Lib_Database") (part "RES"))
    )
    (comp (ref "R278")
      (value "100K")
      (footprint "R0603N")
      (description "RES 0 OHM JUMPER 1/16W 0603")
      (fields (field (name "TOLERANCE") "Jumper"))
      (libsource (lib "Altium_Component_Lib_Database") (part "RES"))
    )
    (comp (ref "R279")
      (value "100K")
      (footprint "R0603N")
      (description "RES 0 OHM JUMPER 1/16W 0603")
      (fields (field (name "TOLERANCE") "Jumper"))
      (libsource (lib "Altium_Component_Lib_Database") (part "RES"))
    )
    (comp (ref "R280")
      (value "100K")
      (footprint "R0603N")
      (description "RES 0 OHM JUMPER 1/16W 0603")
      (fields (field (name "TOLERANCE") "Jumper"))
      (libsource (lib "Altium_Component_Lib_Database") (part "RES"))
    )
    (comp (ref "R281")
      (value "100K")
      (footprint "R0603N")
      (description "RES 0 OHM JUMPER 1/16W 0603")
      (fields (field (name "TOLERANCE") "Jumper"))
      (libsource (lib "Altium_Component_Lib_Database") (part "RES"))
    )
    (comp (ref "R282")
      (value "100K")
      (footprint "R0603N")
      (description "RES 0 OHM JUMPER 1/16W 0603")
      (fields (field (name "TOLERANCE") "Jumper"))
      (libsource (lib "Altium_Component_Lib_Database") (part "RES"))
    )
    (comp (ref "R283")
      (value "100K")
      (footprint "R0603N")
      (description "RES 0 OHM JUMPER 1/16W 0603")
      (fields (field (name "TOLERANCE") "Jumper"))
      (libsource (lib "Altium_Component_Lib_Database") (part "RES"))
    )
    (comp (ref "R284")
      (value "100K")
      (footprint "R0603N")
      (description "RES 0 OHM JUMPER 1/16W 0603")
      (fields (field (name "TOLERANCE") "Jumper"))
      (libsource (lib "Altium_Component_Lib_Database") (part "RES"))
    )
    (comp (ref "R285")
      (value "100K")
      (footprint "R0603N")
      (description "RES 0 OHM JUMPER 1/16W 0603")
      (fields (field (name "TOLERANCE") "Jumper"))
      (libsource (lib "Altium_Component_Lib_Database") (part "RES"))
    )
    (comp (ref "R286")
      (value "100K")
      (footprint "R0603N")
      (description "RES 0 OHM JUMPER 1/16W 0603")
      (fields (field (name "TOLERANCE") "Jumper"))
      (libsource (lib "Altium_Component_Lib_Database") (part "RES"))
    )
    (comp (ref "R287")
      (value "100K")
      (footprint "R0603N")
      (description "RES 0 OHM JUMPER 1/16W 0603")
      (fields (field (name "TOLERANCE") "Jumper"))
      (libsource (lib "Altium_Component_Lib_Database") (part "RES"))
    )
    (comp (ref "R288")
      (value "100K")
      (footprint "R0603N")
      (description "RES 0 OHM JUMPER 1/16W 0603")
      (fields (field (name "TOLERANCE") "Jumper"))
      (libsource (lib "Altium_Component_Lib_Database") (part "RES"))
    )
    (comp (ref "R289")
      (value "100K")
      (footprint "R0603N")
      (description "RES 0 OHM JUMPER 1/16W 0603")
      (fields (field (name "TOLERANCE") "Jumper"))
      (libsource (lib "Altium_Component_Lib_Database") (part "RES"))
    )
    (comp (ref "R290")
      (value "100K")
      (footprint "R0603N")
      (description "RES 0 OHM JUMPER 1/16W 0603")
      (fields (field (name "TOLERANCE") "Jumper"))
      (libsource (lib "Altium_Component_Lib_Database") (part "RES"))
    )
    (comp (ref "R291")
      (value "100K")
      (footprint "R0603N")
      (description "RES 0 OHM JUMPER 1/16W 0603")
      (fields (field (name "TOLERANCE") "Jumper"))
      (libsource (lib "Altium_Component_Lib_Database") (part "RES"))
    )
    (comp (ref "R292")
      (value "100K")
      (footprint "R0603N")
      (description "RES 0 OHM JUMPER 1/16W 0603")
      (fields (field (name "TOLERANCE") "Jumper"))
      (libsource (lib "Altium_Component_Lib_Database") (part "RES"))
    )
    (comp (ref "R293")
      (value "100K")
      (footprint "R0603N")
      (description "RES 0 OHM JUMPER 1/16W 0603")
      (fields (field (name "TOLERANCE") "Jumper"))
      (libsource (lib "Altium_Component_Lib_Database") (part "RES"))
    )
    (comp (ref "R294")
      (value "100K")
      (footprint "R0603N")
      (description "RES 0 OHM JUMPER 1/16W 0603")
      (fields (field (name "TOLERANCE") "Jumper"))
      (libsource (lib "Altium_Component_Lib_Database") (part "RES"))
    )
    (comp (ref "R295")
      (value "100K")
      (footprint "R0603N")
      (description "RES 0 OHM JUMPER 1/16W 0603")
      (fields (field (name "TOLERANCE") "Jumper"))
      (libsource (lib "Altium_Component_Lib_Database") (part "RES"))
    )
    (comp (ref "R296")
      (value "100K")
      (footprint "R0603N")
      (description "RES 0 OHM JUMPER 1/16W 0603")
      (fields (field (name "TOLERANCE") "Jumper"))
      (libsource (lib "Altium_Component_Lib_Database") (part "RES"))
    )
    (comp (ref "R297")
      (value "100K")
      (footprint "R0603N")
      (description "RES 0 OHM JUMPER 1/16W 0603")
      (fields (field (name "TOLERANCE") "Jumper"))
      (libsource (lib "Altium_Component_Lib_Database") (part "RES"))
    )
    (comp (ref "R298")
      (value "100K")
      (footprint "R0603N")
      (description "RES 0 OHM JUMPER 1/16W 0603")
      (fields (field (name "TOLERANCE") "Jumper"))
      (libsource (lib "Altium_Component_Lib_Database") (part "RES"))
    )
    (comp (ref "R299")
      (value "100K")
      (footprint "R0603N")
      (description "RES 0 OHM JUMPER 1/16W 0603")
      (fields (field (name "TOLERANCE") "Jumper"))
      (libsource (lib "Altium_Component_Lib_Database") (part "RES"))
    )
    (comp (ref "R300")
      (value "100K")
      (footprint "R0603N")
      (description "RES 0 OHM JUMPER 1/16W 0603")
      (fields (field (name "TOLERANCE") "Jumper"))
      (libsource (lib "Altium_Component_Lib_Database") (part "RES"))
    )
    (comp (ref "R301")
      (value "22R")
      (footprint "R0603N")
      (description "RES 0 OHM JUMPER 1/16W 0603")
      (fields
        (field (name "PACKAGE") "0603")
        (field (name "POWER RATING") "1/16W")
        (field (name "TOLERANCE") "Jumper")
      )
      (libsource (lib "Altium_Component_Lib_Database") (part "RES"))
    )
    (comp (ref "R302")
      (value "22R")
      (footprint "R0603N")
      (description "RES 0 OHM JUMPER 1/16W 0603")
      (fields
        (field (name "PACKAGE") "0603")
        (field (name "POWER RATING") "1/16W")
        (field (name "TOLERANCE") "Jumper")
      )
      (libsource (lib "Altium_Component_Lib_Database") (part "RES"))
    )
    (comp (ref "SW1")
      (value "SW")
      (footprint "SW4")
      (description "Switch button 4 pin")
      (libsource (lib "PELAB") (part "SW4"))
    )
    (comp (ref "SW2")
      (value "SW")
      (footprint "SW4")
      (description "Switch button 4 pin")
      (libsource (lib "PELAB") (part "SW4"))
    )
    (comp (ref "U1")
      (value "LM2576S")
      (footprint "TO263-5")
      (libsource (lib "DoraTek_Schematic.~(41)") (part "LM2576S"))
    )
    (comp (ref "U2")
      (value "74HC4067PW,118")
      (footprint "TSSOP24_SOT355-1_NEX-M")
      (description "Description")
      (fields (field (name "COPYRIGHT") "Copyright (C) 2025 Ultra Librarian. All rights reserved."))
      (libsource (lib "DoraTek_Schematic.~(41)") (part "74HC4067PW,118"))
    )
    (comp (ref "U3")
      (value "74HC4067PW,118")
      (footprint "TSSOP24_SOT355-1_NEX-M")
      (description "Description")
      (fields (field (name "COPYRIGHT") "Copyright (C) 2025 Ultra Librarian. All rights reserved."))
      (libsource (lib "DoraTek_Schematic.~(41)") (part "74HC4067PW,118"))
    )
    (comp (ref "U4")
      (value "74HC4067PW,118")
      (footprint "TSSOP24_SOT355-1_NEX-M")
      (description "Description")
      (fields (field (name "COPYRIGHT") "Copyright (C) 2025 Ultra Librarian. All rights reserved."))
      (libsource (lib "DoraTek_Schematic.~(41)") (part "74HC4067PW,118"))
    )
    (comp (ref "U5")
      (value "74HC4067PW,118")
      (footprint "TSSOP24_SOT355-1_NEX-M")
      (description "Description")
      (fields (field (name "COPYRIGHT") "Copyright (C) 2025 Ultra Librarian. All rights reserved."))
      (libsource (lib "DoraTek_Schematic.~(41)") (part "74HC4067PW,118"))
    )
    (comp (ref "U6")
      (value "74HC4067PW,118")
      (footprint "TSSOP24_SOT355-1_NEX-M")
      (description "Description")
      (fields (field (name "COPYRIGHT") "Copyright (C) 2025 Ultra Librarian. All rights reserved."))
      (libsource (lib "DoraTek_Schematic.~(41)") (part "74HC4067PW,118"))
    )
    (comp (ref "U7")
      (value "74HC4067PW,118")
      (footprint "TSSOP24_SOT355-1_NEX-M")
      (description "Description")
      (fields (field (name "COPYRIGHT") "Copyright (C) 2025 Ultra Librarian. All rights reserved."))
      (libsource (lib "DoraTek_Schematic.~(41)") (part "74HC4067PW,118"))
    )
    (comp (ref "U8")
      (value "74HC4067PW,118")
      (footprint "TSSOP24_SOT355-1_NEX-M")
      (description "Description")
      (fields (field (name "COPYRIGHT") "Copyright (C) 2025 Ultra Librarian. All rights reserved."))
      (libsource (lib "DoraTek_Schematic.~(41)") (part "74HC4067PW,118"))
    )
    (comp (ref "U9")
      (value "74HC4067PW,118")
      (footprint "TSSOP24_SOT355-1_NEX-M")
      (description "Description")
      (fields (field (name "COPYRIGHT") "Copyright (C) 2025 Ultra Librarian. All rights reserved."))
      (libsource (lib "DoraTek_Schematic.~(41)") (part "74HC4067PW,118"))
    )
    (comp (ref "U10")
      (value "DSPIC30F4011-30I/PT")
      (footprint "TQFP44_MC_MCH-M")
      (description "MICROCHIP - DSPIC30F4011-30I/PT - DSC, 32BIT, 120MHZ, 48KB, 5.5V, TQFP-44")
      (libsource (lib "DoraTek_Schematic.~(41)") (part "DSPIC30F4011-30I/PT"))
    )
    (comp (ref "U11")
      (value "74HC4067PW,118")
      (footprint "TSSOP24_SOT355-1_NEX-M")
      (description "Description")
      (fields (field (name "COPYRIGHT") "Copyright (C) 2025 Ultra Librarian. All rights reserved."))
      (libsource (lib "DoraTek_Schematic.~(41)") (part "74HC4067PW,118"))
    )
    (comp (ref "U12")
      (value "74HC4067PW,118")
      (footprint "TSSOP24_SOT355-1_NEX-M")
      (description "Description")
      (fields (field (name "COPYRIGHT") "Copyright (C) 2025 Ultra Librarian. All rights reserved."))
      (libsource (lib "DoraTek_Schematic.~(41)") (part "74HC4067PW,118"))
    )
    (comp (ref "U13")
      (value "74HC4067PW,118")
      (footprint "TSSOP24_SOT355-1_NEX-M")
      (description "Description")
      (fields (field (name "COPYRIGHT") "Copyright (C) 2025 Ultra Librarian. All rights reserved."))
      (libsource (lib "DoraTek_Schematic.~(41)") (part "74HC4067PW,118"))
    )
    (comp (ref "U14")
      (value "74HC4067PW,118")
      (footprint "TSSOP24_SOT355-1_NEX-M")
      (description "Description")
      (fields (field (name "COPYRIGHT") "Copyright (C) 2025 Ultra Librarian. All rights reserved."))
      (libsource (lib "DoraTek_Schematic.~(41)") (part "74HC4067PW,118"))
    )
    (comp (ref "U15")
      (value "74HC4067PW,118")
      (footprint "TSSOP24_SOT355-1_NEX-M")
      (description "Description")
      (fields (field (name "COPYRIGHT") "Copyright (C) 2025 Ultra Librarian. All rights reserved."))
      (libsource (lib "DoraTek_Schematic.~(41)") (part "74HC4067PW,118"))
    )
    (comp (ref "U16")
      (value "74HC4067PW,118")
      (footprint "TSSOP24_SOT355-1_NEX-M")
      (description "Description")
      (fields (field (name "COPYRIGHT") "Copyright (C) 2025 Ultra Librarian. All rights reserved."))
      (libsource (lib "DoraTek_Schematic.~(41)") (part "74HC4067PW,118"))
    )
    (comp (ref "U17")
      (value "74HC4067PW,118")
      (footprint "TSSOP24_SOT355-1_NEX-M")
      (description "Description")
      (fields (field (name "COPYRIGHT") "Copyright (C) 2025 Ultra Librarian. All rights reserved."))
      (libsource (lib "DoraTek_Schematic.~(41)") (part "74HC4067PW,118"))
    )
    (comp (ref "U18")
      (value "74HC4067PW,118")
      (footprint "TSSOP24_SOT355-1_NEX-M")
      (description "Description")
      (fields (field (name "COPYRIGHT") "Copyright (C) 2025 Ultra Librarian. All rights reserved."))
      (libsource (lib "DoraTek_Schematic.~(41)") (part "74HC4067PW,118"))
    )
    (comp (ref "U19")
      (value "PCA9555PW")
      (footprint "SOP65P640X120-24N")
      (description "16-bit 2.3- to 5.5-V I2C/SMBus I/O expander with interrupt, weak pull-up & config registers")
      (fields (field (name "MF") "Texas Instruments"))
      (libsource (lib "DoraTek_Schematic.~(41)") (part "PCA9555PW"))
    )
    (comp (ref "U20")
      (value "PCA9555PW")
      (footprint "SOP65P640X120-24N")
      (description "16-bit 2.3- to 5.5-V I2C/SMBus I/O expander with interrupt, weak pull-up & config registers")
      (fields (field (name "MF") "Texas Instruments"))
      (libsource (lib "DoraTek_Schematic.~(41)") (part "PCA9555PW"))
    )
    (comp (ref "U21")
      (value "FT232RL-REEL")
      (footprint "FP-SSOP-28-MFG")
      (description "IC USB FS SERIAL UART 28-SSOP")
      (fields (field (name "VOLTAGE") "5V"))
      (libsource (lib "DoraTek_Schematic.~(41)") (part "FT232RL"))
    )
    (comp (ref "VIT1")
      (value "1")
      (footprint "luong.nv1610:VIT")
      (description "Oc Vit")
      (libsource (lib "luong.nv1610") (part "VIT"))
    )
    (comp (ref "VIT2")
      (value "1")
      (footprint "luong.nv1610:VIT")
      (description "Oc Vit")
      (libsource (lib "luong.nv1610") (part "VIT"))
    )
    (comp (ref "VIT3")
      (value "1")
      (footprint "luong.nv1610:VIT")
      (description "Oc Vit")
      (libsource (lib "luong.nv1610") (part "VIT"))
    )
    (comp (ref "VIT4")
      (value "1")
      (footprint "luong.nv1610:VIT")
      (description "Oc Vit")
      (libsource (lib "luong.nv1610") (part "VIT"))
    )
    (comp (ref "X1")
      (value "7.3728MHZ, 20PF")
      (footprint "XT2")
      (description "CRYSTAL, 7.3728MHZ, 20PF")
      (libsource (lib "luong.nv1610") (part "FOXSLF/073-20"))
    )
  )
  (nets
    (net (code "1") (name "+3V3") (class "Default")
      (node (ref "C35") (pin "1") (pinfunction "1_1") (pintype "passive"))
      (node (ref "U21") (pin "17") (pinfunction "3V3OUT_17") (pintype "output"))
    )
    (net (code "2") (name "+5VDC") (class "Default")
      (node (ref "C10") (pin "1") (pinfunction "1_1") (pintype "passive"))
      (node (ref "C11") (pin "1") (pinfunction "1_1") (pintype "passive"))
      (node (ref "C12") (pin "1") (pinfunction "1_1") (pintype "passive"))
      (node (ref "C19") (pin "1") (pinfunction "1_1") (pintype "passive"))
      (node (ref "C20") (pin "1") (pinfunction "1_1") (pintype "passive"))
      (node (ref "C21") (pin "1") (pinfunction "1_1") (pintype "passive"))
      (node (ref "C22") (pin "1") (pinfunction "1_1") (pintype "passive"))
      (node (ref "C24") (pin "1") (pinfunction "1_1") (pintype "passive"))
      (node (ref "C25") (pin "1") (pinfunction "1_1") (pintype "passive"))
      (node (ref "C26") (pin "1") (pinfunction "1_1") (pintype "passive"))
      (node (ref "C27") (pin "1") (pinfunction "1_1") (pintype "passive"))
      (node (ref "C3") (pin "1") (pinfunction "1_1") (pintype "passive"))
      (node (ref "C30") (pin "1") (pinfunction "1_1") (pintype "passive"))
      (node (ref "C31") (pin "1") (pinfunction "1_1") (pintype "passive"))
      (node (ref "C4") (pin "1") (pinfunction "1_1") (pintype "passive"))
      (node (ref "C5") (pin "1") (pinfunction "1_1") (pintype "passive"))
      (node (ref "C6") (pin "1") (pinfunction "1_1") (pintype "passive"))
      (node (ref "C9") (pin "1") (pinfunction "1_1") (pintype "passive"))
      (node (ref "J3") (pin "1") (pinfunction "VBUS_1") (pintype "power_in"))
      (node (ref "R1") (pin "2") (pinfunction "2_2") (pintype "passive"))
      (node (ref "R10") (pin "2") (pinfunction "2_2") (pintype "passive"))
      (node (ref "R100") (pin "2") (pinfunction "2_2") (pintype "passive"))
      (node (ref "R101") (pin "2") (pinfunction "2_2") (pintype "passive"))
      (node (ref "R102") (pin "2") (pinfunction "2_2") (pintype "passive"))
      (node (ref "R103") (pin "2") (pinfunction "2_2") (pintype "passive"))
      (node (ref "R104") (pin "2") (pinfunction "2_2") (pintype "passive"))
      (node (ref "R105") (pin "2") (pinfunction "2_2") (pintype "passive"))
      (node (ref "R106") (pin "2") (pinfunction "2_2") (pintype "passive"))
      (node (ref "R107") (pin "2") (pinfunction "2_2") (pintype "passive"))
      (node (ref "R108") (pin "2") (pinfunction "2_2") (pintype "passive"))
      (node (ref "R109") (pin "2") (pinfunction "2_2") (pintype "passive"))
      (node (ref "R11") (pin "2") (pinfunction "2_2") (pintype "passive"))
      (node (ref "R110") (pin "2") (pinfunction "2_2") (pintype "passive"))
      (node (ref "R111") (pin "2") (pinfunction "2_2") (pintype "passive"))
      (node (ref "R112") (pin "2") (pinfunction "2_2") (pintype "passive"))
      (node (ref "R113") (pin "2") (pinfunction "2_2") (pintype "passive"))
      (node (ref "R114") (pin "2") (pinfunction "2_2") (pintype "passive"))
      (node (ref "R115") (pin "2") (pinfunction "2_2") (pintype "passive"))
      (node (ref "R116") (pin "2") (pinfunction "2_2") (pintype "passive"))
      (node (ref "R117") (pin "2") (pinfunction "2_2") (pintype "passive"))
      (node (ref "R118") (pin "2") (pinfunction "2_2") (pintype "passive"))
      (node (ref "R12") (pin "2") (pinfunction "2_2") (pintype "passive"))
      (node (ref "R123") (pin "2") (pinfunction "2_2") (pintype "passive"))
      (node (ref "R124") (pin "2") (pinfunction "2_2") (pintype "passive"))
      (node (ref "R125") (pin "2") (pinfunction "2_2") (pintype "passive"))
      (node (ref "R126") (pin "2") (pinfunction "2_2") (pintype "passive"))
      (node (ref "R127") (pin "2") (pinfunction "2_2") (pintype "passive"))
      (node (ref "R128") (pin "2") (pinfunction "2_2") (pintype "passive"))
      (node (ref "R129") (pin "2") (pinfunction "2_2") (pintype "passive"))
      (node (ref "R13") (pin "2") (pinfunction "2_2") (pintype "passive"))
      (node (ref "R130") (pin "2") (pinfunction "2_2") (pintype "passive"))
      (node (ref "R131") (pin "2") (pinfunction "2_2") (pintype "passive"))
      (node (ref "R132") (pin "2") (pinfunction "2_2") (pintype "passive"))
      (node (ref "R133") (pin "2") (pinfunction "2_2") (pintype "passive"))
      (node (ref "R134") (pin "2") (pinfunction "2_2") (pintype "passive"))
      (node (ref "R135") (pin "2") (pinfunction "2_2") (pintype "passive"))
      (node (ref "R136") (pin "2") (pinfunction "2_2") (pintype "passive"))
      (node (ref "R137") (pin "2") (pinfunction "2_2") (pintype "passive"))
      (node (ref "R138") (pin "2") (pinfunction "2_2") (pintype "passive"))
      (node (ref "R139") (pin "2") (pinfunction "2_2") (pintype "passive"))
      (node (ref "R14") (pin "2") (pinfunction "2_2") (pintype "passive"))
      (node (ref "R140") (pin "2") (pinfunction "2_2") (pintype "passive"))
      (node (ref "R141") (pin "2") (pinfunction "2_2") (pintype "passive"))
      (node (ref "R142") (pin "2") (pinfunction "2_2") (pintype "passive"))
      (node (ref "R143") (pin "2") (pinfunction "2_2") (pintype "passive"))
      (node (ref "R144") (pin "2") (pinfunction "2_2") (pintype "passive"))
      (node (ref "R145") (pin "2") (pinfunction "2_2") (pintype "passive"))
      (node (ref "R146") (pin "2") (pinfunction "2_2") (pintype "passive"))
      (node (ref "R147") (pin "2") (pinfunction "2_2") (pintype "passive"))
      (node (ref "R148") (pin "2") (pinfunction "2_2") (pintype "passive"))
      (node (ref "R149") (pin "2") (pinfunction "2_2") (pintype "passive"))
      (node (ref "R15") (pin "2") (pinfunction "2_2") (pintype "passive"))
      (node (ref "R150") (pin "2") (pinfunction "2_2") (pintype "passive"))
      (node (ref "R151") (pin "2") (pinfunction "2_2") (pintype "passive"))
      (node (ref "R152") (pin "2") (pinfunction "2_2") (pintype "passive"))
      (node (ref "R153") (pin "2") (pinfunction "2_2") (pintype "passive"))
      (node (ref "R154") (pin "2") (pinfunction "2_2") (pintype "passive"))
      (node (ref "R155") (pin "2") (pinfunction "2_2") (pintype "passive"))
      (node (ref "R156") (pin "2") (pinfunction "2_2") (pintype "passive"))
      (node (ref "R158") (pin "2") (pinfunction "2_2") (pintype "passive"))
      (node (ref "R16") (pin "2") (pinfunction "2_2") (pintype "passive"))
      (node (ref "R163") (pin "2") (pinfunction "2_2") (pintype "passive"))
      (node (ref "R164") (pin "2") (pinfunction "2_2") (pintype "passive"))
      (node (ref "R165") (pin "2") (pinfunction "2_2") (pintype "passive"))
      (node (ref "R166") (pin "2") (pinfunction "2_2") (pintype "passive"))
      (node (ref "R167") (pin "2") (pinfunction "2_2") (pintype "passive"))
      (node (ref "R168") (pin "2") (pinfunction "2_2") (pintype "passive"))
      (node (ref "R169") (pin "2") (pinfunction "2_2") (pintype "passive"))
      (node (ref "R17") (pin "2") (pinfunction "2_2") (pintype "passive"))
      (node (ref "R170") (pin "2") (pinfunction "2_2") (pintype "passive"))
      (node (ref "R171") (pin "2") (pinfunction "2_2") (pintype "passive"))
      (node (ref "R172") (pin "2") (pinfunction "2_2") (pintype "passive"))
      (node (ref "R173") (pin "2") (pinfunction "2_2") (pintype "passive"))
      (node (ref "R174") (pin "2") (pinfunction "2_2") (pintype "passive"))
      (node (ref "R175") (pin "2") (pinfunction "2_2") (pintype "passive"))
      (node (ref "R176") (pin "2") (pinfunction "2_2") (pintype "passive"))
      (node (ref "R177") (pin "2") (pinfunction "2_2") (pintype "passive"))
      (node (ref "R178") (pin "2") (pinfunction "2_2") (pintype "passive"))
      (node (ref "R179") (pin "2") (pinfunction "2_2") (pintype "passive"))
      (node (ref "R18") (pin "2") (pinfunction "2_2") (pintype "passive"))
      (node (ref "R180") (pin "2") (pinfunction "2_2") (pintype "passive"))
      (node (ref "R181") (pin "2") (pinfunction "2_2") (pintype "passive"))
      (node (ref "R182") (pin "2") (pinfunction "2_2") (pintype "passive"))
      (node (ref "R183") (pin "2") (pinfunction "2_2") (pintype "passive"))
      (node (ref "R184") (pin "2") (pinfunction "2_2") (pintype "passive"))
      (node (ref "R185") (pin "2") (pinfunction "2_2") (pintype "passive"))
      (node (ref "R186") (pin "2") (pinfunction "2_2") (pintype "passive"))
      (node (ref "R187") (pin "2") (pinfunction "2_2") (pintype "passive"))
      (node (ref "R188") (pin "2") (pinfunction "2_2") (pintype "passive"))
      (node (ref "R189") (pin "2") (pinfunction "2_2") (pintype "passive"))
      (node (ref "R19") (pin "2") (pinfunction "2_2") (pintype "passive"))
      (node (ref "R190") (pin "2") (pinfunction "2_2") (pintype "passive"))
      (node (ref "R191") (pin "2") (pinfunction "2_2") (pintype "passive"))
      (node (ref "R192") (pin "2") (pinfunction "2_2") (pintype "passive"))
      (node (ref "R193") (pin "2") (pinfunction "2_2") (pintype "passive"))
      (node (ref "R194") (pin "2") (pinfunction "2_2") (pintype "passive"))
      (node (ref "R195") (pin "2") (pinfunction "2_2") (pintype "passive"))
      (node (ref "R196") (pin "2") (pinfunction "2_2") (pintype "passive"))
      (node (ref "R197") (pin "2") (pinfunction "2_2") (pintype "passive"))
      (node (ref "R198") (pin "2") (pinfunction "2_2") (pintype "passive"))
      (node (ref "R199") (pin "2") (pinfunction "2_2") (pintype "passive"))
      (node (ref "R2") (pin "2") (pinfunction "2_2") (pintype "passive"))
      (node (ref "R20") (pin "2") (pinfunction "2_2") (pintype "passive"))
      (node (ref "R200") (pin "2") (pinfunction "2_2") (pintype "passive"))
      (node (ref "R201") (pin "2") (pinfunction "2_2") (pintype "passive"))
      (node (ref "R202") (pin "2") (pinfunction "2_2") (pintype "passive"))
      (node (ref "R203") (pin "2") (pinfunction "2_2") (pintype "passive"))
      (node (ref "R204") (pin "2") (pinfunction "2_2") (pintype "passive"))
      (node (ref "R205") (pin "2") (pinfunction "2_2") (pintype "passive"))
      (node (ref "R206") (pin "2") (pinfunction "2_2") (pintype "passive"))
      (node (ref "R207") (pin "2") (pinfunction "2_2") (pintype "passive"))
      (node (ref "R208") (pin "2") (pinfunction "2_2") (pintype "passive"))
      (node (ref "R209") (pin "2") (pinfunction "2_2") (pintype "passive"))
      (node (ref "R21") (pin "2") (pinfunction "2_2") (pintype "passive"))
      (node (ref "R210") (pin "2") (pinfunction "2_2") (pintype "passive"))
      (node (ref "R211") (pin "2") (pinfunction "2_2") (pintype "passive"))
      (node (ref "R212") (pin "1") (pinfunction "1_1") (pintype "passive"))
      (node (ref "R213") (pin "1") (pinfunction "1_1") (pintype "passive"))
      (node (ref "R214") (pin "1") (pinfunction "1_1") (pintype "passive"))
      (node (ref "R215") (pin "1") (pinfunction "1_1") (pintype "passive"))
      (node (ref "R216") (pin "2") (pinfunction "2_2") (pintype "passive"))
      (node (ref "R217") (pin "2") (pinfunction "2_2") (pintype "passive"))
      (node (ref "R22") (pin "2") (pinfunction "2_2") (pintype "passive"))
      (node (ref "R220") (pin "2") (pinfunction "2_2") (pintype "passive"))
      (node (ref "R221") (pin "2") (pinfunction "2_2") (pintype "passive"))
      (node (ref "R222") (pin "2") (pinfunction "2_2") (pintype "passive"))
      (node (ref "R223") (pin "2") (pinfunction "2_2") (pintype "passive"))
      (node (ref "R224") (pin "2") (pinfunction "2_2") (pintype "passive"))
      (node (ref "R225") (pin "2") (pinfunction "2_2") (pintype "passive"))
      (node (ref "R226") (pin "2") (pinfunction "2_2") (pintype "passive"))
      (node (ref "R227") (pin "2") (pinfunction "2_2") (pintype "passive"))
      (node (ref "R228") (pin "2") (pinfunction "2_2") (pintype "passive"))
      (node (ref "R229") (pin "2") (pinfunction "2_2") (pintype "passive"))
      (node (ref "R23") (pin "2") (pinfunction "2_2") (pintype "passive"))
      (node (ref "R230") (pin "2") (pinfunction "2_2") (pintype "passive"))
      (node (ref "R231") (pin "2") (pinfunction "2_2") (pintype "passive"))
      (node (ref "R232") (pin "2") (pinfunction "2_2") (pintype "passive"))
      (node (ref "R233") (pin "2") (pinfunction "2_2") (pintype "passive"))
      (node (ref "R234") (pin "2") (pinfunction "2_2") (pintype "passive"))
      (node (ref "R235") (pin "2") (pinfunction "2_2") (pintype "passive"))
      (node (ref "R24") (pin "2") (pinfunction "2_2") (pintype "passive"))
      (node (ref "R245") (pin "2") (pinfunction "2_2") (pintype "passive"))
      (node (ref "R25") (pin "2") (pinfunction "2_2") (pintype "passive"))
      (node (ref "R26") (pin "2") (pinfunction "2_2") (pintype "passive"))
      (node (ref "R269") (pin "2") (pinfunction "2_2") (pintype "passive"))
      (node (ref "R27") (pin "2") (pinfunction "2_2") (pintype "passive"))
      (node (ref "R270") (pin "2") (pinfunction "2_2") (pintype "passive"))
      (node (ref "R271") (pin "2") (pinfunction "2_2") (pintype "passive"))
      (node (ref "R272") (pin "2") (pinfunction "2_2") (pintype "passive"))
      (node (ref "R273") (pin "2") (pinfunction "2_2") (pintype "passive"))
      (node (ref "R274") (pin "2") (pinfunction "2_2") (pintype "passive"))
      (node (ref "R275") (pin "2") (pinfunction "2_2") (pintype "passive"))
      (node (ref "R276") (pin "2") (pinfunction "2_2") (pintype "passive"))
      (node (ref "R277") (pin "2") (pinfunction "2_2") (pintype "passive"))
      (node (ref "R278") (pin "2") (pinfunction "2_2") (pintype "passive"))
      (node (ref "R279") (pin "2") (pinfunction "2_2") (pintype "passive"))
      (node (ref "R28") (pin "2") (pinfunction "2_2") (pintype "passive"))
      (node (ref "R280") (pin "2") (pinfunction "2_2") (pintype "passive"))
      (node (ref "R281") (pin "2") (pinfunction "2_2") (pintype "passive"))
      (node (ref "R282") (pin "2") (pinfunction "2_2") (pintype "passive"))
      (node (ref "R283") (pin "2") (pinfunction "2_2") (pintype "passive"))
      (node (ref "R284") (pin "2") (pinfunction "2_2") (pintype "passive"))
      (node (ref "R285") (pin "2") (pinfunction "2_2") (pintype "passive"))
      (node (ref "R286") (pin "2") (pinfunction "2_2") (pintype "passive"))
      (node (ref "R287") (pin "2") (pinfunction "2_2") (pintype "passive"))
      (node (ref "R288") (pin "2") (pinfunction "2_2") (pintype "passive"))
      (node (ref "R289") (pin "2") (pinfunction "2_2") (pintype "passive"))
      (node (ref "R29") (pin "2") (pinfunction "2_2") (pintype "passive"))
      (node (ref "R290") (pin "2") (pinfunction "2_2") (pintype "passive"))
      (node (ref "R291") (pin "2") (pinfunction "2_2") (pintype "passive"))
      (node (ref "R292") (pin "2") (pinfunction "2_2") (pintype "passive"))
      (node (ref "R293") (pin "2") (pinfunction "2_2") (pintype "passive"))
      (node (ref "R294") (pin "2") (pinfunction "2_2") (pintype "passive"))
      (node (ref "R295") (pin "2") (pinfunction "2_2") (pintype "passive"))
      (node (ref "R296") (pin "2") (pinfunction "2_2") (pintype "passive"))
      (node (ref "R297") (pin "2") (pinfunction "2_2") (pintype "passive"))
      (node (ref "R298") (pin "2") (pinfunction "2_2") (pintype "passive"))
      (node (ref "R299") (pin "2") (pinfunction "2_2") (pintype "passive"))
      (node (ref "R3") (pin "2") (pinfunction "2_2") (pintype "passive"))
      (node (ref "R30") (pin "2") (pinfunction "2_2") (pintype "passive"))
      (node (ref "R300") (pin "2") (pinfunction "2_2") (pintype "passive"))
      (node (ref "R31") (pin "2") (pinfunction "2_2") (pintype "passive"))
      (node (ref "R32") (pin "2") (pinfunction "2_2") (pintype "passive"))
      (node (ref "R33") (pin "2") (pinfunction "2_2") (pintype "passive"))
      (node (ref "R34") (pin "2") (pinfunction "2_2") (pintype "passive"))
      (node (ref "R35") (pin "1") (pinfunction "1_1") (pintype "passive"))
      (node (ref "R4") (pin "2") (pinfunction "2_2") (pintype "passive"))
      (node (ref "R41") (pin "2") (pinfunction "2_2") (pintype "passive"))
      (node (ref "R42") (pin "2") (pinfunction "2_2") (pintype "passive"))
      (node (ref "R43") (pin "2") (pinfunction "2_2") (pintype "passive"))
      (node (ref "R44") (pin "2") (pinfunction "2_2") (pintype "passive"))
      (node (ref "R45") (pin "2") (pinfunction "2_2") (pintype "passive"))
      (node (ref "R46") (pin "2") (pinfunction "2_2") (pintype "passive"))
      (node (ref "R47") (pin "2") (pinfunction "2_2") (pintype "passive"))
      (node (ref "R48") (pin "2") (pinfunction "2_2") (pintype "passive"))
      (node (ref "R49") (pin "2") (pinfunction "2_2") (pintype "passive"))
      (node (ref "R5") (pin "2") (pinfunction "2_2") (pintype "passive"))
      (node (ref "R50") (pin "2") (pinfunction "2_2") (pintype "passive"))
      (node (ref "R51") (pin "2") (pinfunction "2_2") (pintype "passive"))
      (node (ref "R52") (pin "2") (pinfunction "2_2") (pintype "passive"))
      (node (ref "R53") (pin "2") (pinfunction "2_2") (pintype "passive"))
      (node (ref "R54") (pin "2") (pinfunction "2_2") (pintype "passive"))
      (node (ref "R55") (pin "2") (pinfunction "2_2") (pintype "passive"))
      (node (ref "R56") (pin "2") (pinfunction "2_2") (pintype "passive"))
      (node (ref "R57") (pin "2") (pinfunction "2_2") (pintype "passive"))
      (node (ref "R58") (pin "2") (pinfunction "2_2") (pintype "passive"))
      (node (ref "R59") (pin "2") (pinfunction "2_2") (pintype "passive"))
      (node (ref "R6") (pin "2") (pinfunction "2_2") (pintype "passive"))
      (node (ref "R60") (pin "2") (pinfunction "2_2") (pintype "passive"))
      (node (ref "R61") (pin "2") (pinfunction "2_2") (pintype "passive"))
      (node (ref "R62") (pin "2") (pinfunction "2_2") (pintype "passive"))
      (node (ref "R63") (pin "2") (pinfunction "2_2") (pintype "passive"))
      (node (ref "R64") (pin "2") (pinfunction "2_2") (pintype "passive"))
      (node (ref "R65") (pin "2") (pinfunction "2_2") (pintype "passive"))
      (node (ref "R66") (pin "2") (pinfunction "2_2") (pintype "passive"))
      (node (ref "R67") (pin "2") (pinfunction "2_2") (pintype "passive"))
      (node (ref "R68") (pin "2") (pinfunction "2_2") (pintype "passive"))
      (node (ref "R69") (pin "2") (pinfunction "2_2") (pintype "passive"))
      (node (ref "R7") (pin "2") (pinfunction "2_2") (pintype "passive"))
      (node (ref "R70") (pin "2") (pinfunction "2_2") (pintype "passive"))
      (node (ref "R71") (pin "2") (pinfunction "2_2") (pintype "passive"))
      (node (ref "R72") (pin "2") (pinfunction "2_2") (pintype "passive"))
      (node (ref "R73") (pin "2") (pinfunction "2_2") (pintype "passive"))
      (node (ref "R74") (pin "2") (pinfunction "2_2") (pintype "passive"))
      (node (ref "R75") (pin "2") (pinfunction "2_2") (pintype "passive"))
      (node (ref "R8") (pin "2") (pinfunction "2_2") (pintype "passive"))
      (node (ref "R85") (pin "2") (pinfunction "2_2") (pintype "passive"))
      (node (ref "R86") (pin "2") (pinfunction "2_2") (pintype "passive"))
      (node (ref "R87") (pin "2") (pinfunction "2_2") (pintype "passive"))
      (node (ref "R88") (pin "2") (pinfunction "2_2") (pintype "passive"))
      (node (ref "R89") (pin "2") (pinfunction "2_2") (pintype "passive"))
      (node (ref "R9") (pin "2") (pinfunction "2_2") (pintype "passive"))
      (node (ref "R90") (pin "2") (pinfunction "2_2") (pintype "passive"))
      (node (ref "R91") (pin "2") (pinfunction "2_2") (pintype "passive"))
      (node (ref "R92") (pin "2") (pinfunction "2_2") (pintype "passive"))
      (node (ref "R93") (pin "2") (pinfunction "2_2") (pintype "passive"))
      (node (ref "R94") (pin "2") (pinfunction "2_2") (pintype "passive"))
      (node (ref "R95") (pin "2") (pinfunction "2_2") (pintype "passive"))
      (node (ref "R96") (pin "2") (pinfunction "2_2") (pintype "passive"))
      (node (ref "R97") (pin "2") (pinfunction "2_2") (pintype "passive"))
      (node (ref "R98") (pin "2") (pinfunction "2_2") (pintype "passive"))
      (node (ref "R99") (pin "2") (pinfunction "2_2") (pintype "passive"))
      (node (ref "U11") (pin "24") (pinfunction "VCC_24") (pintype "power_in"))
      (node (ref "U12") (pin "24") (pinfunction "VCC_24") (pintype "power_in"))
      (node (ref "U13") (pin "24") (pinfunction "VCC_24") (pintype "power_in"))
      (node (ref "U14") (pin "24") (pinfunction "VCC_24") (pintype "power_in"))
      (node (ref "U15") (pin "24") (pinfunction "VCC_24") (pintype "power_in"))
      (node (ref "U16") (pin "24") (pinfunction "VCC_24") (pintype "power_in"))
      (node (ref "U17") (pin "24") (pinfunction "VCC_24") (pintype "power_in"))
      (node (ref "U18") (pin "24") (pinfunction "VCC_24") (pintype "power_in"))
      (node (ref "U19") (pin "24") (pinfunction "VDD_24") (pintype "power_in"))
      (node (ref "U2") (pin "24") (pinfunction "VCC_24") (pintype "power_in"))
      (node (ref "U20") (pin "24") (pinfunction "VDD_24") (pintype "power_in"))
      (node (ref "U20") (pin "3") (pinfunction "A2_3") (pintype "input"))
      (node (ref "U3") (pin "24") (pinfunction "VCC_24") (pintype "power_in"))
      (node (ref "U4") (pin "24") (pinfunction "VCC_24") (pintype "power_in"))
      (node (ref "U5") (pin "24") (pinfunction "VCC_24") (pintype "power_in"))
      (node (ref "U6") (pin "24") (pinfunction "VCC_24") (pintype "power_in"))
      (node (ref "U7") (pin "24") (pinfunction "VCC_24") (pintype "power_in"))
      (node (ref "U8") (pin "24") (pinfunction "VCC_24") (pintype "power_in"))
      (node (ref "U9") (pin "24") (pinfunction "VCC_24") (pintype "power_in"))
    )
    (net (code "3") (name "/A1Y0") (class "Default")
      (node (ref "J1") (pin "A1") (pintype "bidirectional"))
      (node (ref "R9") (pin "1") (pinfunction "1_1") (pintype "passive"))
      (node (ref "U2") (pin "9") (pinfunction "Y0_9") (pintype "bidirectional"))
    )
    (net (code "4") (name "/A1Y1") (class "Default")
      (node (ref "J1") (pin "A2") (pintype "bidirectional"))
      (node (ref "R26") (pin "1") (pinfunction "1_1") (pintype "passive"))
      (node (ref "U2") (pin "8") (pinfunction "Y1_8") (pintype "bidirectional"))
    )
    (net (code "5") (name "/A1Y2") (class "Default")
      (node (ref "J1") (pin "A3") (pintype "bidirectional"))
      (node (ref "R8") (pin "1") (pinfunction "1_1") (pintype "passive"))
      (node (ref "U2") (pin "7") (pinfunction "Y2_7") (pintype "bidirectional"))
    )
    (net (code "6") (name "/A1Y3") (class "Default")
      (node (ref "J1") (pin "A4") (pintype "bidirectional"))
      (node (ref "R25") (pin "1") (pinfunction "1_1") (pintype "passive"))
      (node (ref "U2") (pin "6") (pinfunction "Y3_6") (pintype "bidirectional"))
    )
    (net (code "7") (name "/A1Y4") (class "Default")
      (node (ref "J1") (pin "A5") (pintype "bidirectional"))
      (node (ref "R7") (pin "1") (pinfunction "1_1") (pintype "passive"))
      (node (ref "U2") (pin "5") (pinfunction "Y4_5") (pintype "bidirectional"))
    )
    (net (code "8") (name "/A1Y5") (class "Default")
      (node (ref "J1") (pin "A6") (pintype "bidirectional"))
      (node (ref "R24") (pin "1") (pinfunction "1_1") (pintype "passive"))
      (node (ref "U2") (pin "4") (pinfunction "Y5_4") (pintype "bidirectional"))
    )
    (net (code "9") (name "/A1Y6") (class "Default")
      (node (ref "J1") (pin "A7") (pintype "bidirectional"))
      (node (ref "R6") (pin "1") (pinfunction "1_1") (pintype "passive"))
      (node (ref "U2") (pin "3") (pinfunction "Y6_3") (pintype "bidirectional"))
    )
    (net (code "10") (name "/A1Y7") (class "Default")
      (node (ref "J1") (pin "A8") (pintype "bidirectional"))
      (node (ref "R23") (pin "1") (pinfunction "1_1") (pintype "passive"))
      (node (ref "U2") (pin "2") (pinfunction "Y7_2") (pintype "bidirectional"))
    )
    (net (code "11") (name "/A1Y8") (class "Default")
      (node (ref "J1") (pin "A9") (pintype "bidirectional"))
      (node (ref "R5") (pin "1") (pinfunction "1_1") (pintype "passive"))
      (node (ref "U2") (pin "23") (pinfunction "Y8_23") (pintype "bidirectional"))
    )
    (net (code "12") (name "/A1Y9") (class "Default")
      (node (ref "J1") (pin "A10") (pintype "bidirectional"))
      (node (ref "R22") (pin "1") (pinfunction "1_1") (pintype "passive"))
      (node (ref "U2") (pin "22") (pinfunction "Y9_22") (pintype "bidirectional"))
    )
    (net (code "13") (name "/A1Y10") (class "Default")
      (node (ref "J1") (pin "A11") (pintype "bidirectional"))
      (node (ref "R4") (pin "1") (pinfunction "1_1") (pintype "passive"))
      (node (ref "U2") (pin "21") (pinfunction "Y10_21") (pintype "bidirectional"))
    )
    (net (code "14") (name "/A1Y11") (class "Default")
      (node (ref "J1") (pin "A12") (pintype "bidirectional"))
      (node (ref "R21") (pin "1") (pinfunction "1_1") (pintype "passive"))
      (node (ref "U2") (pin "20") (pinfunction "Y11_20") (pintype "bidirectional"))
    )
    (net (code "15") (name "/A1Y12") (class "Default")
      (node (ref "J1") (pin "A13") (pintype "bidirectional"))
      (node (ref "R3") (pin "1") (pinfunction "1_1") (pintype "passive"))
      (node (ref "U2") (pin "19") (pinfunction "Y12_19") (pintype "bidirectional"))
    )
    (net (code "16") (name "/A1Y13") (class "Default")
      (node (ref "J1") (pin "A14") (pintype "bidirectional"))
      (node (ref "R20") (pin "1") (pinfunction "1_1") (pintype "passive"))
      (node (ref "U2") (pin "18") (pinfunction "Y13_18") (pintype "bidirectional"))
    )
    (net (code "17") (name "/A1Y14") (class "Default")
      (node (ref "J1") (pin "A15") (pintype "bidirectional"))
      (node (ref "R2") (pin "1") (pinfunction "1_1") (pintype "passive"))
      (node (ref "U2") (pin "17") (pinfunction "Y14_17") (pintype "bidirectional"))
    )
    (net (code "18") (name "/A1Y15") (class "Default")
      (node (ref "J1") (pin "A16") (pintype "bidirectional"))
      (node (ref "R19") (pin "1") (pinfunction "1_1") (pintype "passive"))
      (node (ref "U2") (pin "16") (pinfunction "Y15_16") (pintype "bidirectional"))
    )
    (net (code "19") (name "/A1_ENABLE") (class "Default")
      (node (ref "R258") (pin "1") (pinfunction "1_1") (pintype "passive"))
      (node (ref "U2") (pin "15") (pinfunction "/E_15") (pintype "input"))
    )
    (net (code "20") (name "/A1_Z_MCU") (class "Default")
      (node (ref "R37") (pin "1") (pinfunction "1_1") (pintype "passive"))
      (node (ref "U10") (pin "4") (pinfunction "C1TX/RF1_4") (pintype "bidirectional"))
    )
    (net (code "21") (name "/A2Y0") (class "Default")
      (node (ref "J1") (pin "A17") (pintype "bidirectional"))
      (node (ref "R1") (pin "1") (pinfunction "1_1") (pintype "passive"))
      (node (ref "U3") (pin "9") (pinfunction "Y0_9") (pintype "bidirectional"))
    )
    (net (code "22") (name "/A2Y1") (class "Default")
      (node (ref "J1") (pin "B1") (pintype "bidirectional"))
      (node (ref "R49") (pin "1") (pinfunction "1_1") (pintype "passive"))
      (node (ref "U3") (pin "8") (pinfunction "Y1_8") (pintype "bidirectional"))
    )
    (net (code "23") (name "/A2Y2") (class "Default")
      (node (ref "J1") (pin "B2") (pintype "bidirectional"))
      (node (ref "R66") (pin "1") (pinfunction "1_1") (pintype "passive"))
      (node (ref "U3") (pin "7") (pinfunction "Y2_7") (pintype "bidirectional"))
    )
    (net (code "24") (name "/A2Y3") (class "Default")
      (node (ref "J1") (pin "B3") (pintype "bidirectional"))
      (node (ref "R48") (pin "1") (pinfunction "1_1") (pintype "passive"))
      (node (ref "U3") (pin "6") (pinfunction "Y3_6") (pintype "bidirectional"))
    )
    (net (code "25") (name "/A2Y4") (class "Default")
      (node (ref "J1") (pin "B4") (pintype "bidirectional"))
      (node (ref "R65") (pin "1") (pinfunction "1_1") (pintype "passive"))
      (node (ref "U3") (pin "5") (pinfunction "Y4_5") (pintype "bidirectional"))
    )
    (net (code "26") (name "/A2Y5") (class "Default")
      (node (ref "J1") (pin "B5") (pintype "bidirectional"))
      (node (ref "R47") (pin "1") (pinfunction "1_1") (pintype "passive"))
      (node (ref "U3") (pin "4") (pinfunction "Y5_4") (pintype "bidirectional"))
    )
    (net (code "27") (name "/A2Y6") (class "Default")
      (node (ref "J1") (pin "B6") (pintype "bidirectional"))
      (node (ref "R64") (pin "1") (pinfunction "1_1") (pintype "passive"))
      (node (ref "U3") (pin "3") (pinfunction "Y6_3") (pintype "bidirectional"))
    )
    (net (code "28") (name "/A2Y7") (class "Default")
      (node (ref "J1") (pin "B7") (pintype "bidirectional"))
      (node (ref "R46") (pin "1") (pinfunction "1_1") (pintype "passive"))
      (node (ref "U3") (pin "2") (pinfunction "Y7_2") (pintype "bidirectional"))
    )
    (net (code "29") (name "/A2Y8") (class "Default")
      (node (ref "J1") (pin "B8") (pintype "bidirectional"))
      (node (ref "R63") (pin "1") (pinfunction "1_1") (pintype "passive"))
      (node (ref "U3") (pin "23") (pinfunction "Y8_23") (pintype "bidirectional"))
    )
    (net (code "30") (name "/A2Y9") (class "Default")
      (node (ref "J1") (pin "B9") (pintype "bidirectional"))
      (node (ref "R45") (pin "1") (pinfunction "1_1") (pintype "passive"))
      (node (ref "U3") (pin "22") (pinfunction "Y9_22") (pintype "bidirectional"))
    )
    (net (code "31") (name "/A2Y10") (class "Default")
      (node (ref "J1") (pin "B10") (pintype "bidirectional"))
      (node (ref "R62") (pin "1") (pinfunction "1_1") (pintype "passive"))
      (node (ref "U3") (pin "21") (pinfunction "Y10_21") (pintype "bidirectional"))
    )
    (net (code "32") (name "/A2Y11") (class "Default")
      (node (ref "J1") (pin "B11") (pintype "bidirectional"))
      (node (ref "R44") (pin "1") (pinfunction "1_1") (pintype "passive"))
      (node (ref "U3") (pin "20") (pinfunction "Y11_20") (pintype "bidirectional"))
    )
    (net (code "33") (name "/A2Y12") (class "Default")
      (node (ref "J1") (pin "B12") (pintype "bidirectional"))
      (node (ref "R61") (pin "1") (pinfunction "1_1") (pintype "passive"))
      (node (ref "U3") (pin "19") (pinfunction "Y12_19") (pintype "bidirectional"))
    )
    (net (code "34") (name "/A2Y13") (class "Default")
      (node (ref "J1") (pin "B13") (pintype "bidirectional"))
      (node (ref "R43") (pin "1") (pinfunction "1_1") (pintype "passive"))
      (node (ref "U3") (pin "18") (pinfunction "Y13_18") (pintype "bidirectional"))
    )
    (net (code "35") (name "/A2Y14") (class "Default")
      (node (ref "J1") (pin "B14") (pintype "bidirectional"))
      (node (ref "R60") (pin "1") (pinfunction "1_1") (pintype "passive"))
      (node (ref "U3") (pin "17") (pinfunction "Y14_17") (pintype "bidirectional"))
    )
    (net (code "36") (name "/A2Y15") (class "Default")
      (node (ref "J1") (pin "B15") (pintype "bidirectional"))
      (node (ref "R42") (pin "1") (pinfunction "1_1") (pintype "passive"))
      (node (ref "U3") (pin "16") (pinfunction "Y15_16") (pintype "bidirectional"))
    )
    (net (code "37") (name "/A2_ENABLE") (class "Default")
      (node (ref "R250") (pin "1") (pinfunction "1_1") (pintype "passive"))
      (node (ref "U3") (pin "15") (pinfunction "/E_15") (pintype "input"))
    )
    (net (code "38") (name "/A2_Z_MCU") (class "Default")
      (node (ref "R38") (pin "1") (pinfunction "1_1") (pintype "passive"))
      (node (ref "U10") (pin "8") (pinfunction "PWM3H/RE5_8") (pintype "bidirectional"))
    )
    (net (code "39") (name "/A3Y0") (class "Default")
      (node (ref "J1") (pin "B16") (pintype "bidirectional"))
      (node (ref "R59") (pin "1") (pinfunction "1_1") (pintype "passive"))
      (node (ref "U6") (pin "9") (pinfunction "Y0_9") (pintype "bidirectional"))
    )
    (net (code "40") (name "/A3Y1") (class "Default")
      (node (ref "J1") (pin "B17") (pintype "bidirectional"))
      (node (ref "R41") (pin "1") (pinfunction "1_1") (pintype "passive"))
      (node (ref "U6") (pin "8") (pinfunction "Y1_8") (pintype "bidirectional"))
    )
    (net (code "41") (name "/A3Y2") (class "Default")
      (node (ref "J1") (pin "C1") (pintype "bidirectional"))
      (node (ref "R93") (pin "1") (pinfunction "1_1") (pintype "passive"))
      (node (ref "U6") (pin "7") (pinfunction "Y2_7") (pintype "bidirectional"))
    )
    (net (code "42") (name "/A3Y3") (class "Default")
      (node (ref "J1") (pin "C2") (pintype "bidirectional"))
      (node (ref "R110") (pin "1") (pinfunction "1_1") (pintype "passive"))
      (node (ref "U6") (pin "6") (pinfunction "Y3_6") (pintype "bidirectional"))
    )
    (net (code "43") (name "/A3Y4") (class "Default")
      (node (ref "J1") (pin "C3") (pintype "bidirectional"))
      (node (ref "R92") (pin "1") (pinfunction "1_1") (pintype "passive"))
      (node (ref "U6") (pin "5") (pinfunction "Y4_5") (pintype "bidirectional"))
    )
    (net (code "44") (name "/A3Y5") (class "Default")
      (node (ref "J1") (pin "C4") (pintype "bidirectional"))
      (node (ref "R109") (pin "1") (pinfunction "1_1") (pintype "passive"))
      (node (ref "U6") (pin "4") (pinfunction "Y5_4") (pintype "bidirectional"))
    )
    (net (code "45") (name "/A3Y6") (class "Default")
      (node (ref "J1") (pin "C5") (pintype "bidirectional"))
      (node (ref "R91") (pin "1") (pinfunction "1_1") (pintype "passive"))
      (node (ref "U6") (pin "3") (pinfunction "Y6_3") (pintype "bidirectional"))
    )
    (net (code "46") (name "/A3Y7") (class "Default")
      (node (ref "J1") (pin "C6") (pintype "bidirectional"))
      (node (ref "R108") (pin "1") (pinfunction "1_1") (pintype "passive"))
      (node (ref "U6") (pin "2") (pinfunction "Y7_2") (pintype "bidirectional"))
    )
    (net (code "47") (name "/A3Y8") (class "Default")
      (node (ref "J1") (pin "C7") (pintype "bidirectional"))
      (node (ref "R90") (pin "1") (pinfunction "1_1") (pintype "passive"))
      (node (ref "U6") (pin "23") (pinfunction "Y8_23") (pintype "bidirectional"))
    )
    (net (code "48") (name "/A3Y9") (class "Default")
      (node (ref "J1") (pin "C8") (pintype "bidirectional"))
      (node (ref "R107") (pin "1") (pinfunction "1_1") (pintype "passive"))
      (node (ref "U6") (pin "22") (pinfunction "Y9_22") (pintype "bidirectional"))
    )
    (net (code "49") (name "/A3Y10") (class "Default")
      (node (ref "J1") (pin "C9") (pintype "bidirectional"))
      (node (ref "R89") (pin "1") (pinfunction "1_1") (pintype "passive"))
      (node (ref "U6") (pin "21") (pinfunction "Y10_21") (pintype "bidirectional"))
    )
    (net (code "50") (name "/A3Y11") (class "Default")
      (node (ref "J1") (pin "C10") (pintype "bidirectional"))
      (node (ref "R106") (pin "1") (pinfunction "1_1") (pintype "passive"))
      (node (ref "U6") (pin "20") (pinfunction "Y11_20") (pintype "bidirectional"))
    )
    (net (code "51") (name "/A3Y12") (class "Default")
      (node (ref "J1") (pin "C11") (pintype "bidirectional"))
      (node (ref "R88") (pin "1") (pinfunction "1_1") (pintype "passive"))
      (node (ref "U6") (pin "19") (pinfunction "Y12_19") (pintype "bidirectional"))
    )
    (net (code "52") (name "/A3Y13") (class "Default")
      (node (ref "J1") (pin "C12") (pintype "bidirectional"))
      (node (ref "R105") (pin "1") (pinfunction "1_1") (pintype "passive"))
      (node (ref "U6") (pin "18") (pinfunction "Y13_18") (pintype "bidirectional"))
    )
    (net (code "53") (name "/A3Y14") (class "Default")
      (node (ref "J1") (pin "C13") (pintype "bidirectional"))
      (node (ref "R87") (pin "1") (pinfunction "1_1") (pintype "passive"))
      (node (ref "U6") (pin "17") (pinfunction "Y14_17") (pintype "bidirectional"))
    )
    (net (code "54") (name "/A3Y15") (class "Default")
      (node (ref "J1") (pin "C14") (pintype "bidirectional"))
      (node (ref "R104") (pin "1") (pinfunction "1_1") (pintype "passive"))
      (node (ref "U6") (pin "16") (pinfunction "Y15_16") (pintype "bidirectional"))
    )
    (net (code "55") (name "/A3_ENABLE") (class "Default")
      (node (ref "R259") (pin "2") (pinfunction "2_2") (pintype "passive"))
      (node (ref "U6") (pin "15") (pinfunction "/E_15") (pintype "input"))
    )
    (net (code "56") (name "/A3_Z_MCU") (class "Default")
      (node (ref "R81") (pin "1") (pinfunction "1_1") (pintype "passive"))
      (node (ref "U10") (pin "15") (pinfunction "PWM1L/RE0_15") (pintype "bidirectional"))
    )
    (net (code "57") (name "/A4Y0") (class "Default")
      (node (ref "J1") (pin "C15") (pintype "bidirectional"))
      (node (ref "R86") (pin "1") (pinfunction "1_1") (pintype "passive"))
      (node (ref "U7") (pin "9") (pinfunction "Y0_9") (pintype "bidirectional"))
    )
    (net (code "58") (name "/A4Y1") (class "Default")
      (node (ref "J1") (pin "C16") (pintype "bidirectional"))
      (node (ref "R103") (pin "1") (pinfunction "1_1") (pintype "passive"))
      (node (ref "U7") (pin "8") (pinfunction "Y1_8") (pintype "bidirectional"))
    )
    (net (code "59") (name "/A4Y2") (class "Default")
      (node (ref "J1") (pin "C17") (pintype "bidirectional"))
      (node (ref "R85") (pin "1") (pinfunction "1_1") (pintype "passive"))
      (node (ref "U7") (pin "7") (pinfunction "Y2_7") (pintype "bidirectional"))
    )
    (net (code "60") (name "/A4Y3") (class "Default")
      (node (ref "J1") (pin "D1") (pintype "bidirectional"))
      (node (ref "R131") (pin "1") (pinfunction "1_1") (pintype "passive"))
      (node (ref "U7") (pin "6") (pinfunction "Y3_6") (pintype "bidirectional"))
    )
    (net (code "61") (name "/A4Y4") (class "Default")
      (node (ref "J1") (pin "D2") (pintype "bidirectional"))
      (node (ref "R148") (pin "1") (pinfunction "1_1") (pintype "passive"))
      (node (ref "U7") (pin "5") (pinfunction "Y4_5") (pintype "bidirectional"))
    )
    (net (code "62") (name "/A4Y5") (class "Default")
      (node (ref "J1") (pin "D3") (pintype "bidirectional"))
      (node (ref "R130") (pin "1") (pinfunction "1_1") (pintype "passive"))
      (node (ref "U7") (pin "4") (pinfunction "Y5_4") (pintype "bidirectional"))
    )
    (net (code "63") (name "/A4Y6") (class "Default")
      (node (ref "J1") (pin "D4") (pintype "bidirectional"))
      (node (ref "R147") (pin "1") (pinfunction "1_1") (pintype "passive"))
      (node (ref "U7") (pin "3") (pinfunction "Y6_3") (pintype "bidirectional"))
    )
    (net (code "64") (name "/A4Y7") (class "Default")
      (node (ref "J1") (pin "D5") (pintype "bidirectional"))
      (node (ref "R129") (pin "1") (pinfunction "1_1") (pintype "passive"))
      (node (ref "U7") (pin "2") (pinfunction "Y7_2") (pintype "bidirectional"))
    )
    (net (code "65") (name "/A4Y8") (class "Default")
      (node (ref "J1") (pin "D6") (pintype "bidirectional"))
      (node (ref "R146") (pin "1") (pinfunction "1_1") (pintype "passive"))
      (node (ref "U7") (pin "23") (pinfunction "Y8_23") (pintype "bidirectional"))
    )
    (net (code "66") (name "/A4Y9") (class "Default")
      (node (ref "J1") (pin "D7") (pintype "bidirectional"))
      (node (ref "R128") (pin "1") (pinfunction "1_1") (pintype "passive"))
      (node (ref "U7") (pin "22") (pinfunction "Y9_22") (pintype "bidirectional"))
    )
    (net (code "67") (name "/A4Y10") (class "Default")
      (node (ref "J1") (pin "D8") (pintype "bidirectional"))
      (node (ref "R145") (pin "1") (pinfunction "1_1") (pintype "passive"))
      (node (ref "U7") (pin "21") (pinfunction "Y10_21") (pintype "bidirectional"))
    )
    (net (code "68") (name "/A4Y11") (class "Default")
      (node (ref "J1") (pin "D9") (pintype "bidirectional"))
      (node (ref "R127") (pin "1") (pinfunction "1_1") (pintype "passive"))
      (node (ref "U7") (pin "20") (pinfunction "Y11_20") (pintype "bidirectional"))
    )
    (net (code "69") (name "/A4Y12") (class "Default")
      (node (ref "J1") (pin "D10") (pintype "bidirectional"))
      (node (ref "R144") (pin "1") (pinfunction "1_1") (pintype "passive"))
      (node (ref "U7") (pin "19") (pinfunction "Y12_19") (pintype "bidirectional"))
    )
    (net (code "70") (name "/A4Y13") (class "Default")
      (node (ref "J1") (pin "D11") (pintype "bidirectional"))
      (node (ref "R126") (pin "1") (pinfunction "1_1") (pintype "passive"))
      (node (ref "U7") (pin "18") (pinfunction "Y13_18") (pintype "bidirectional"))
    )
    (net (code "71") (name "/A4Y14") (class "Default")
      (node (ref "J1") (pin "D12") (pintype "bidirectional"))
      (node (ref "R143") (pin "1") (pinfunction "1_1") (pintype "passive"))
      (node (ref "U7") (pin "17") (pinfunction "Y14_17") (pintype "bidirectional"))
    )
    (net (code "72") (name "/A4Y15") (class "Default")
      (node (ref "J1") (pin "D13") (pintype "bidirectional"))
      (node (ref "R125") (pin "1") (pinfunction "1_1") (pintype "passive"))
      (node (ref "U7") (pin "16") (pinfunction "Y15_16") (pintype "bidirectional"))
    )
    (net (code "73") (name "/A4_ENABLE") (class "Default")
      (node (ref "R251") (pin "2") (pinfunction "2_2") (pintype "passive"))
      (node (ref "U7") (pin "15") (pinfunction "/E_15") (pintype "input"))
    )
    (net (code "74") (name "/A4_Z_MCU") (class "Default")
      (node (ref "R82") (pin "1") (pinfunction "1_1") (pintype "passive"))
      (node (ref "U10") (pin "11") (pinfunction "PWM2L/RE2_11") (pintype "bidirectional"))
    )
    (net (code "75") (name "/A5Y0") (class "Default")
      (node (ref "J1") (pin "D14") (pintype "bidirectional"))
      (node (ref "R142") (pin "1") (pinfunction "1_1") (pintype "passive"))
      (node (ref "U11") (pin "9") (pinfunction "Y0_9") (pintype "bidirectional"))
    )
    (net (code "76") (name "/A5Y1") (class "Default")
      (node (ref "J1") (pin "D15") (pintype "bidirectional"))
      (node (ref "R124") (pin "1") (pinfunction "1_1") (pintype "passive"))
      (node (ref "U11") (pin "8") (pinfunction "Y1_8") (pintype "bidirectional"))
    )
    (net (code "77") (name "/A5Y2") (class "Default")
      (node (ref "J1") (pin "D16") (pintype "bidirectional"))
      (node (ref "R141") (pin "1") (pinfunction "1_1") (pintype "passive"))
      (node (ref "U11") (pin "7") (pinfunction "Y2_7") (pintype "bidirectional"))
    )
    (net (code "78") (name "/A5Y3") (class "Default")
      (node (ref "J1") (pin "D17") (pintype "bidirectional"))
      (node (ref "R123") (pin "1") (pinfunction "1_1") (pintype "passive"))
      (node (ref "U11") (pin "6") (pinfunction "Y3_6") (pintype "bidirectional"))
    )
    (net (code "79") (name "/A5Y4") (class "Default")
      (node (ref "J1") (pin "E1") (pintype "bidirectional"))
      (node (ref "R170") (pin "1") (pinfunction "1_1") (pintype "passive"))
      (node (ref "U11") (pin "5") (pinfunction "Y4_5") (pintype "bidirectional"))
    )
    (net (code "80") (name "/A5Y5") (class "Default")
      (node (ref "J1") (pin "E2") (pintype "bidirectional"))
      (node (ref "R187") (pin "1") (pinfunction "1_1") (pintype "passive"))
      (node (ref "U11") (pin "4") (pinfunction "Y5_4") (pintype "bidirectional"))
    )
    (net (code "81") (name "/A5Y6") (class "Default")
      (node (ref "J1") (pin "E3") (pintype "bidirectional"))
      (node (ref "R169") (pin "1") (pinfunction "1_1") (pintype "passive"))
      (node (ref "U11") (pin "3") (pinfunction "Y6_3") (pintype "bidirectional"))
    )
    (net (code "82") (name "/A5Y7") (class "Default")
      (node (ref "J1") (pin "E4") (pintype "bidirectional"))
      (node (ref "R186") (pin "1") (pinfunction "1_1") (pintype "passive"))
      (node (ref "U11") (pin "2") (pinfunction "Y7_2") (pintype "bidirectional"))
    )
    (net (code "83") (name "/A5Y8") (class "Default")
      (node (ref "J1") (pin "E5") (pintype "bidirectional"))
      (node (ref "R168") (pin "1") (pinfunction "1_1") (pintype "passive"))
      (node (ref "U11") (pin "23") (pinfunction "Y8_23") (pintype "bidirectional"))
    )
    (net (code "84") (name "/A5Y9") (class "Default")
      (node (ref "J1") (pin "E6") (pintype "bidirectional"))
      (node (ref "R185") (pin "1") (pinfunction "1_1") (pintype "passive"))
      (node (ref "U11") (pin "22") (pinfunction "Y9_22") (pintype "bidirectional"))
    )
    (net (code "85") (name "/A5Y10") (class "Default")
      (node (ref "J1") (pin "E7") (pintype "bidirectional"))
      (node (ref "R167") (pin "1") (pinfunction "1_1") (pintype "passive"))
      (node (ref "U11") (pin "21") (pinfunction "Y10_21") (pintype "bidirectional"))
    )
    (net (code "86") (name "/A5Y11") (class "Default")
      (node (ref "J1") (pin "E8") (pintype "bidirectional"))
      (node (ref "R184") (pin "1") (pinfunction "1_1") (pintype "passive"))
      (node (ref "U11") (pin "20") (pinfunction "Y11_20") (pintype "bidirectional"))
    )
    (net (code "87") (name "/A5Y12") (class "Default")
      (node (ref "J1") (pin "E9") (pintype "bidirectional"))
      (node (ref "R166") (pin "1") (pinfunction "1_1") (pintype "passive"))
      (node (ref "U11") (pin "19") (pinfunction "Y12_19") (pintype "bidirectional"))
    )
    (net (code "88") (name "/A5Y13") (class "Default")
      (node (ref "J1") (pin "E10") (pintype "bidirectional"))
      (node (ref "R183") (pin "1") (pinfunction "1_1") (pintype "passive"))
      (node (ref "U11") (pin "18") (pinfunction "Y13_18") (pintype "bidirectional"))
    )
    (net (code "89") (name "/A5Y14") (class "Default")
      (node (ref "J1") (pin "E11") (pintype "bidirectional"))
      (node (ref "R165") (pin "1") (pinfunction "1_1") (pintype "passive"))
      (node (ref "U11") (pin "17") (pinfunction "Y14_17") (pintype "bidirectional"))
    )
    (net (code "90") (name "/A5Y15") (class "Default")
      (node (ref "J1") (pin "E12") (pintype "bidirectional"))
      (node (ref "R182") (pin "1") (pinfunction "1_1") (pintype "passive"))
      (node (ref "U11") (pin "16") (pinfunction "Y15_16") (pintype "bidirectional"))
    )
    (net (code "91") (name "/A5_ENABLE") (class "Default")
      (node (ref "R254") (pin "1") (pinfunction "1_1") (pintype "passive"))
      (node (ref "U11") (pin "15") (pinfunction "/E_15") (pintype "input"))
    )
    (net (code "92") (name "/A5_Z_MCU") (class "Default")
      (node (ref "R119") (pin "1") (pinfunction "1_1") (pintype "passive"))
      (node (ref "U10") (pin "5") (pinfunction "C1RX/RF0_5") (pintype "bidirectional"))
    )
    (net (code "93") (name "/A6Y0") (class "Default")
      (node (ref "J1") (pin "E13") (pintype "bidirectional"))
      (node (ref "R164") (pin "1") (pinfunction "1_1") (pintype "passive"))
      (node (ref "U12") (pin "9") (pinfunction "Y0_9") (pintype "bidirectional"))
    )
    (net (code "94") (name "/A6Y1") (class "Default")
      (node (ref "J1") (pin "E14") (pintype "bidirectional"))
      (node (ref "R181") (pin "1") (pinfunction "1_1") (pintype "passive"))
      (node (ref "U12") (pin "8") (pinfunction "Y1_8") (pintype "bidirectional"))
    )
    (net (code "95") (name "/A6Y2") (class "Default")
      (node (ref "J1") (pin "E15") (pintype "bidirectional"))
      (node (ref "R163") (pin "1") (pinfunction "1_1") (pintype "passive"))
      (node (ref "U12") (pin "7") (pinfunction "Y2_7") (pintype "bidirectional"))
    )
    (net (code "96") (name "/A6Y3") (class "Default")
      (node (ref "J1") (pin "E16") (pintype "bidirectional"))
      (node (ref "R180") (pin "1") (pinfunction "1_1") (pintype "passive"))
      (node (ref "U12") (pin "6") (pinfunction "Y3_6") (pintype "bidirectional"))
    )
    (net (code "97") (name "/A6Y4") (class "Default")
      (node (ref "J1") (pin "F1") (pintype "bidirectional"))
      (node (ref "R203") (pin "1") (pinfunction "1_1") (pintype "passive"))
      (node (ref "U12") (pin "5") (pinfunction "Y4_5") (pintype "bidirectional"))
    )
    (net (code "98") (name "/A6Y5") (class "Default")
      (node (ref "J1") (pin "F2") (pintype "bidirectional"))
      (node (ref "R227") (pin "1") (pinfunction "1_1") (pintype "passive"))
      (node (ref "U12") (pin "4") (pinfunction "Y5_4") (pintype "bidirectional"))
    )
    (net (code "99") (name "/A6Y6") (class "Default")
      (node (ref "J1") (pin "F3") (pintype "bidirectional"))
      (node (ref "R202") (pin "1") (pinfunction "1_1") (pintype "passive"))
      (node (ref "U12") (pin "3") (pinfunction "Y6_3") (pintype "bidirectional"))
    )
    (net (code "100") (name "/A6Y7") (class "Default")
      (node (ref "J1") (pin "F4") (pintype "bidirectional"))
      (node (ref "R226") (pin "1") (pinfunction "1_1") (pintype "passive"))
      (node (ref "U12") (pin "2") (pinfunction "Y7_2") (pintype "bidirectional"))
    )
    (net (code "101") (name "/A6Y8") (class "Default")
      (node (ref "J1") (pin "F5") (pintype "bidirectional"))
      (node (ref "R201") (pin "1") (pinfunction "1_1") (pintype "passive"))
      (node (ref "U12") (pin "23") (pinfunction "Y8_23") (pintype "bidirectional"))
    )
    (net (code "102") (name "/A6Y9") (class "Default")
      (node (ref "J1") (pin "F6") (pintype "bidirectional"))
      (node (ref "R225") (pin "1") (pinfunction "1_1") (pintype "passive"))
      (node (ref "U12") (pin "22") (pinfunction "Y9_22") (pintype "bidirectional"))
    )
    (net (code "103") (name "/A6Y10") (class "Default")
      (node (ref "J1") (pin "F7") (pintype "bidirectional"))
      (node (ref "R200") (pin "1") (pinfunction "1_1") (pintype "passive"))
      (node (ref "U12") (pin "21") (pinfunction "Y10_21") (pintype "bidirectional"))
    )
    (net (code "104") (name "/A6Y11") (class "Default")
      (node (ref "J1") (pin "F8") (pintype "bidirectional"))
      (node (ref "R224") (pin "1") (pinfunction "1_1") (pintype "passive"))
      (node (ref "U12") (pin "20") (pinfunction "Y11_20") (pintype "bidirectional"))
    )
    (net (code "105") (name "/A6Y12") (class "Default")
      (node (ref "J1") (pin "F9") (pintype "bidirectional"))
      (node (ref "R199") (pin "1") (pinfunction "1_1") (pintype "passive"))
      (node (ref "U12") (pin "19") (pinfunction "Y12_19") (pintype "bidirectional"))
    )
    (net (code "106") (name "/A6Y13") (class "Default")
      (node (ref "J1") (pin "F10") (pintype "bidirectional"))
      (node (ref "R223") (pin "1") (pinfunction "1_1") (pintype "passive"))
      (node (ref "U12") (pin "18") (pinfunction "Y13_18") (pintype "bidirectional"))
    )
    (net (code "107") (name "/A6Y14") (class "Default")
      (node (ref "J1") (pin "F11") (pintype "bidirectional"))
      (node (ref "R198") (pin "1") (pinfunction "1_1") (pintype "passive"))
      (node (ref "U12") (pin "17") (pinfunction "Y14_17") (pintype "bidirectional"))
    )
    (net (code "108") (name "/A6Y15") (class "Default")
      (node (ref "J1") (pin "F12") (pintype "bidirectional"))
      (node (ref "R222") (pin "1") (pinfunction "1_1") (pintype "passive"))
      (node (ref "U12") (pin "16") (pinfunction "Y15_16") (pintype "bidirectional"))
    )
    (net (code "109") (name "/A6_ENABLE") (class "Default")
      (node (ref "R246") (pin "1") (pinfunction "1_1") (pintype "passive"))
      (node (ref "U12") (pin "15") (pinfunction "/E_15") (pintype "input"))
    )
    (net (code "110") (name "/A6_Z_MCU") (class "Default")
      (node (ref "R120") (pin "1") (pinfunction "1_1") (pintype "passive"))
      (node (ref "U10") (pin "9") (pinfunction "PWM3L/RE4_9") (pintype "bidirectional"))
    )
    (net (code "111") (name "/A7Y0") (class "Default")
      (node (ref "J1") (pin "F13") (pintype "bidirectional"))
      (node (ref "R197") (pin "1") (pinfunction "1_1") (pintype "passive"))
      (node (ref "U15") (pin "9") (pinfunction "Y0_9") (pintype "bidirectional"))
    )
    (net (code "112") (name "/A7Y1") (class "Default")
      (node (ref "J1") (pin "F14") (pintype "bidirectional"))
      (node (ref "R221") (pin "1") (pinfunction "1_1") (pintype "passive"))
      (node (ref "U15") (pin "8") (pinfunction "Y1_8") (pintype "bidirectional"))
    )
    (net (code "113") (name "/A7Y2") (class "Default")
      (node (ref "J1") (pin "F15") (pintype "bidirectional"))
      (node (ref "R196") (pin "1") (pinfunction "1_1") (pintype "passive"))
      (node (ref "U15") (pin "7") (pinfunction "Y2_7") (pintype "bidirectional"))
    )
    (net (code "114") (name "/A7Y3") (class "Default")
      (node (ref "J1") (pin "F16") (pintype "bidirectional"))
      (node (ref "R220") (pin "1") (pinfunction "1_1") (pintype "passive"))
      (node (ref "U15") (pin "6") (pinfunction "Y3_6") (pintype "bidirectional"))
    )
    (net (code "115") (name "/A7Y4") (class "Default")
      (node (ref "J1") (pin "G1") (pintype "bidirectional"))
      (node (ref "R276") (pin "1") (pinfunction "1_1") (pintype "passive"))
      (node (ref "U15") (pin "5") (pinfunction "Y4_5") (pintype "bidirectional"))
    )
    (net (code "116") (name "/A7Y5") (class "Default")
      (node (ref "J1") (pin "G2") (pintype "bidirectional"))
      (node (ref "R292") (pin "1") (pinfunction "1_1") (pintype "passive"))
      (node (ref "U15") (pin "4") (pinfunction "Y5_4") (pintype "bidirectional"))
    )
    (net (code "117") (name "/A7Y6") (class "Default")
      (node (ref "J1") (pin "G3") (pintype "bidirectional"))
      (node (ref "R275") (pin "1") (pinfunction "1_1") (pintype "passive"))
      (node (ref "U15") (pin "3") (pinfunction "Y6_3") (pintype "bidirectional"))
    )
    (net (code "118") (name "/A7Y7") (class "Default")
      (node (ref "J1") (pin "G4") (pintype "bidirectional"))
      (node (ref "R291") (pin "1") (pinfunction "1_1") (pintype "passive"))
      (node (ref "U15") (pin "2") (pinfunction "Y7_2") (pintype "bidirectional"))
    )
    (net (code "119") (name "/A7Y8") (class "Default")
      (node (ref "J1") (pin "G5") (pintype "bidirectional"))
      (node (ref "R274") (pin "1") (pinfunction "1_1") (pintype "passive"))
      (node (ref "U15") (pin "23") (pinfunction "Y8_23") (pintype "bidirectional"))
    )
    (net (code "120") (name "/A7Y9") (class "Default")
      (node (ref "J1") (pin "G6") (pintype "bidirectional"))
      (node (ref "R290") (pin "1") (pinfunction "1_1") (pintype "passive"))
      (node (ref "U15") (pin "22") (pinfunction "Y9_22") (pintype "bidirectional"))
    )
    (net (code "121") (name "/A7Y10") (class "Default")
      (node (ref "J1") (pin "G7") (pintype "bidirectional"))
      (node (ref "R273") (pin "1") (pinfunction "1_1") (pintype "passive"))
      (node (ref "U15") (pin "21") (pinfunction "Y10_21") (pintype "bidirectional"))
    )
    (net (code "122") (name "/A7Y11") (class "Default")
      (node (ref "J1") (pin "G8") (pintype "bidirectional"))
      (node (ref "R289") (pin "1") (pinfunction "1_1") (pintype "passive"))
      (node (ref "U15") (pin "20") (pinfunction "Y11_20") (pintype "bidirectional"))
    )
    (net (code "123") (name "/A7Y12") (class "Default")
      (node (ref "J1") (pin "G9") (pintype "bidirectional"))
      (node (ref "R272") (pin "1") (pinfunction "1_1") (pintype "passive"))
      (node (ref "U15") (pin "19") (pinfunction "Y12_19") (pintype "bidirectional"))
    )
    (net (code "124") (name "/A7Y13") (class "Default")
      (node (ref "J1") (pin "G10") (pintype "bidirectional"))
      (node (ref "R288") (pin "1") (pinfunction "1_1") (pintype "passive"))
      (node (ref "U15") (pin "18") (pinfunction "Y13_18") (pintype "bidirectional"))
    )
    (net (code "125") (name "/A7Y14") (class "Default")
      (node (ref "J1") (pin "G11") (pintype "bidirectional"))
      (node (ref "R271") (pin "1") (pinfunction "1_1") (pintype "passive"))
      (node (ref "U15") (pin "17") (pinfunction "Y14_17") (pintype "bidirectional"))
    )
    (net (code "126") (name "/A7Y15") (class "Default")
      (node (ref "J1") (pin "G12") (pintype "bidirectional"))
      (node (ref "R287") (pin "1") (pinfunction "1_1") (pintype "passive"))
      (node (ref "U15") (pin "16") (pinfunction "Y15_16") (pintype "bidirectional"))
    )
    (net (code "127") (name "/A7_ENABLE") (class "Default")
      (node (ref "R255") (pin "2") (pinfunction "2_2") (pintype "passive"))
      (node (ref "U15") (pin "15") (pinfunction "/E_15") (pintype "input"))
    )
    (net (code "128") (name "/A7_Z_MCU") (class "Default")
      (node (ref "R159") (pin "1") (pinfunction "1_1") (pintype "passive"))
      (node (ref "U10") (pin "14") (pinfunction "PWM1H/RE1_14") (pintype "bidirectional"))
    )
    (net (code "129") (name "/A8Y0") (class "Default")
      (node (ref "J1") (pin "G13") (pintype "bidirectional"))
      (node (ref "R270") (pin "1") (pinfunction "1_1") (pintype "passive"))
      (node (ref "U16") (pin "9") (pinfunction "Y0_9") (pintype "bidirectional"))
    )
    (net (code "130") (name "/A8Y1") (class "Default")
      (node (ref "J1") (pin "G14") (pintype "bidirectional"))
      (node (ref "R286") (pin "1") (pinfunction "1_1") (pintype "passive"))
      (node (ref "U16") (pin "8") (pinfunction "Y1_8") (pintype "bidirectional"))
    )
    (net (code "131") (name "/A8Y2") (class "Default")
      (node (ref "J1") (pin "G15") (pintype "bidirectional"))
      (node (ref "R269") (pin "1") (pinfunction "1_1") (pintype "passive"))
      (node (ref "U16") (pin "7") (pinfunction "Y2_7") (pintype "bidirectional"))
    )
    (net (code "132") (name "/A8Y3") (class "Default")
      (node (ref "J1") (pin "G16") (pintype "bidirectional"))
      (node (ref "R285") (pin "1") (pinfunction "1_1") (pintype "passive"))
      (node (ref "U16") (pin "6") (pinfunction "Y3_6") (pintype "bidirectional"))
    )
    (net (code "133") (name "/A8_ENABLE") (class "Default")
      (node (ref "R247") (pin "2") (pinfunction "2_2") (pintype "passive"))
      (node (ref "U16") (pin "15") (pinfunction "/E_15") (pintype "input"))
    )
    (net (code "134") (name "/A8_Z_MCU") (class "Default")
      (node (ref "R160") (pin "1") (pinfunction "1_1") (pintype "passive"))
      (node (ref "U10") (pin "10") (pinfunction "PWM2H/RE3_10") (pintype "bidirectional"))
    )
    (net (code "135") (name "/AS0") (class "Default")
      (node (ref "R236") (pin "1") (pinfunction "1_1") (pintype "passive"))
      (node (ref "U11") (pin "10") (pinfunction "S0_10") (pintype "input"))
      (node (ref "U12") (pin "10") (pinfunction "S0_10") (pintype "input"))
      (node (ref "U15") (pin "10") (pinfunction "S0_10") (pintype "input"))
      (node (ref "U16") (pin "10") (pinfunction "S0_10") (pintype "input"))
      (node (ref "U2") (pin "10") (pinfunction "S0_10") (pintype "input"))
      (node (ref "U3") (pin "10") (pinfunction "S0_10") (pintype "input"))
      (node (ref "U6") (pin "10") (pinfunction "S0_10") (pintype "input"))
      (node (ref "U7") (pin "10") (pinfunction "S0_10") (pintype "input"))
    )
    (net (code "136") (name "/AS1") (class "Default")
      (node (ref "R238") (pin "1") (pinfunction "1_1") (pintype "passive"))
      (node (ref "U11") (pin "11") (pinfunction "S1_11") (pintype "input"))
      (node (ref "U12") (pin "11") (pinfunction "S1_11") (pintype "input"))
      (node (ref "U15") (pin "11") (pinfunction "S1_11") (pintype "input"))
      (node (ref "U16") (pin "11") (pinfunction "S1_11") (pintype "input"))
      (node (ref "U2") (pin "11") (pinfunction "S1_11") (pintype "input"))
      (node (ref "U3") (pin "11") (pinfunction "S1_11") (pintype "input"))
      (node (ref "U6") (pin "11") (pinfunction "S1_11") (pintype "input"))
      (node (ref "U7") (pin "11") (pinfunction "S1_11") (pintype "input"))
    )
    (net (code "137") (name "/AS2") (class "Default")
      (node (ref "R241") (pin "1") (pinfunction "1_1") (pintype "passive"))
      (node (ref "U11") (pin "14") (pinfunction "S2_14") (pintype "input"))
      (node (ref "U12") (pin "14") (pinfunction "S2_14") (pintype "input"))
      (node (ref "U15") (pin "14") (pinfunction "S2_14") (pintype "input"))
      (node (ref "U16") (pin "14") (pinfunction "S2_14") (pintype "input"))
      (node (ref "U2") (pin "14") (pinfunction "S2_14") (pintype "input"))
      (node (ref "U3") (pin "14") (pinfunction "S2_14") (pintype "input"))
      (node (ref "U6") (pin "14") (pinfunction "S2_14") (pintype "input"))
      (node (ref "U7") (pin "14") (pinfunction "S2_14") (pintype "input"))
    )
    (net (code "138") (name "/AS3") (class "Default")
      (node (ref "R243") (pin "1") (pinfunction "1_1") (pintype "passive"))
      (node (ref "U11") (pin "13") (pinfunction "S3_13") (pintype "input"))
      (node (ref "U12") (pin "13") (pinfunction "S3_13") (pintype "input"))
      (node (ref "U15") (pin "13") (pinfunction "S3_13") (pintype "input"))
      (node (ref "U16") (pin "13") (pinfunction "S3_13") (pintype "input"))
      (node (ref "U2") (pin "13") (pinfunction "S3_13") (pintype "input"))
      (node (ref "U3") (pin "13") (pinfunction "S3_13") (pintype "input"))
      (node (ref "U6") (pin "13") (pinfunction "S3_13") (pintype "input"))
      (node (ref "U7") (pin "13") (pinfunction "S3_13") (pintype "input"))
    )
    (net (code "139") (name "/B1Y0") (class "Default")
      (node (ref "J2") (pin "A1") (pintype "bidirectional"))
      (node (ref "R10") (pin "1") (pinfunction "1_1") (pintype "passive"))
      (node (ref "U4") (pin "9") (pinfunction "Y0_9") (pintype "bidirectional"))
    )
    (net (code "140") (name "/B1Y1") (class "Default")
      (node (ref "J2") (pin "A2") (pintype "bidirectional"))
      (node (ref "R27") (pin "1") (pinfunction "1_1") (pintype "passive"))
      (node (ref "U4") (pin "8") (pinfunction "Y1_8") (pintype "bidirectional"))
    )
    (net (code "141") (name "/B1Y2") (class "Default")
      (node (ref "J2") (pin "A3") (pintype "bidirectional"))
      (node (ref "R11") (pin "1") (pinfunction "1_1") (pintype "passive"))
      (node (ref "U4") (pin "7") (pinfunction "Y2_7") (pintype "bidirectional"))
    )
    (net (code "142") (name "/B1Y3") (class "Default")
      (node (ref "J2") (pin "A4") (pintype "bidirectional"))
      (node (ref "R28") (pin "1") (pinfunction "1_1") (pintype "passive"))
      (node (ref "U4") (pin "6") (pinfunction "Y3_6") (pintype "bidirectional"))
    )
    (net (code "143") (name "/B1Y4") (class "Default")
      (node (ref "J2") (pin "A5") (pintype "bidirectional"))
      (node (ref "R12") (pin "1") (pinfunction "1_1") (pintype "passive"))
      (node (ref "U4") (pin "5") (pinfunction "Y4_5") (pintype "bidirectional"))
    )
    (net (code "144") (name "/B1Y5") (class "Default")
      (node (ref "J2") (pin "A6") (pintype "bidirectional"))
      (node (ref "R29") (pin "1") (pinfunction "1_1") (pintype "passive"))
      (node (ref "U4") (pin "4") (pinfunction "Y5_4") (pintype "bidirectional"))
    )
    (net (code "145") (name "/B1Y6") (class "Default")
      (node (ref "J2") (pin "A7") (pintype "bidirectional"))
      (node (ref "R13") (pin "1") (pinfunction "1_1") (pintype "passive"))
      (node (ref "U4") (pin "3") (pinfunction "Y6_3") (pintype "bidirectional"))
    )
    (net (code "146") (name "/B1Y7") (class "Default")
      (node (ref "J2") (pin "A8") (pintype "bidirectional"))
      (node (ref "R30") (pin "1") (pinfunction "1_1") (pintype "passive"))
      (node (ref "U4") (pin "2") (pinfunction "Y7_2") (pintype "bidirectional"))
    )
    (net (code "147") (name "/B1Y8") (class "Default")
      (node (ref "J2") (pin "A9") (pintype "bidirectional"))
      (node (ref "R14") (pin "1") (pinfunction "1_1") (pintype "passive"))
      (node (ref "U4") (pin "23") (pinfunction "Y8_23") (pintype "bidirectional"))
    )
    (net (code "148") (name "/B1Y9") (class "Default")
      (node (ref "J2") (pin "A10") (pintype "bidirectional"))
      (node (ref "R31") (pin "1") (pinfunction "1_1") (pintype "passive"))
      (node (ref "U4") (pin "22") (pinfunction "Y9_22") (pintype "bidirectional"))
    )
    (net (code "149") (name "/B1Y10") (class "Default")
      (node (ref "J2") (pin "A11") (pintype "bidirectional"))
      (node (ref "R15") (pin "1") (pinfunction "1_1") (pintype "passive"))
      (node (ref "U4") (pin "21") (pinfunction "Y10_21") (pintype "bidirectional"))
    )
    (net (code "150") (name "/B1Y11") (class "Default")
      (node (ref "J2") (pin "A12") (pintype "bidirectional"))
      (node (ref "R32") (pin "1") (pinfunction "1_1") (pintype "passive"))
      (node (ref "U4") (pin "20") (pinfunction "Y11_20") (pintype "bidirectional"))
    )
    (net (code "151") (name "/B1Y12") (class "Default")
      (node (ref "J2") (pin "A13") (pintype "bidirectional"))
      (node (ref "R16") (pin "1") (pinfunction "1_1") (pintype "passive"))
      (node (ref "U4") (pin "19") (pinfunction "Y12_19") (pintype "bidirectional"))
    )
    (net (code "152") (name "/B1Y13") (class "Default")
      (node (ref "J2") (pin "A14") (pintype "bidirectional"))
      (node (ref "R33") (pin "1") (pinfunction "1_1") (pintype "passive"))
      (node (ref "U4") (pin "18") (pinfunction "Y13_18") (pintype "bidirectional"))
    )
    (net (code "153") (name "/B1Y14") (class "Default")
      (node (ref "J2") (pin "A15") (pintype "bidirectional"))
      (node (ref "R17") (pin "1") (pinfunction "1_1") (pintype "passive"))
      (node (ref "U4") (pin "17") (pinfunction "Y14_17") (pintype "bidirectional"))
    )
    (net (code "154") (name "/B1Y15") (class "Default")
      (node (ref "J2") (pin "A16") (pintype "bidirectional"))
      (node (ref "R34") (pin "1") (pinfunction "1_1") (pintype "passive"))
      (node (ref "U4") (pin "16") (pinfunction "Y15_16") (pintype "bidirectional"))
    )
    (net (code "155") (name "/B1_ENABLE") (class "Default")
      (node (ref "R260") (pin "1") (pinfunction "1_1") (pintype "passive"))
      (node (ref "U4") (pin "15") (pinfunction "/E_15") (pintype "input"))
    )
    (net (code "156") (name "/B1_Z_MCU") (class "Default")
      (node (ref "R39") (pin "1") (pinfunction "1_1") (pintype "passive"))
      (node (ref "U10") (pin "22") (pinfunction "AN3/INDX/CN5/RB3_22") (pintype "bidirectional"))
    )
    (net (code "157") (name "/B2Y0") (class "Default")
      (node (ref "J2") (pin "A17") (pintype "bidirectional"))
      (node (ref "R18") (pin "1") (pinfunction "1_1") (pintype "passive"))
      (node (ref "U5") (pin "9") (pinfunction "Y0_9") (pintype "bidirectional"))
    )
    (net (code "158") (name "/B2Y1") (class "Default")
      (node (ref "J2") (pin "B1") (pintype "bidirectional"))
      (node (ref "R50") (pin "1") (pinfunction "1_1") (pintype "passive"))
      (node (ref "U5") (pin "8") (pinfunction "Y1_8") (pintype "bidirectional"))
    )
    (net (code "159") (name "/B2Y2") (class "Default")
      (node (ref "J2") (pin "B2") (pintype "bidirectional"))
      (node (ref "R67") (pin "1") (pinfunction "1_1") (pintype "passive"))
      (node (ref "U5") (pin "7") (pinfunction "Y2_7") (pintype "bidirectional"))
    )
    (net (code "160") (name "/B2Y3") (class "Default")
      (node (ref "J2") (pin "B3") (pintype "bidirectional"))
      (node (ref "R51") (pin "1") (pinfunction "1_1") (pintype "passive"))
      (node (ref "U5") (pin "6") (pinfunction "Y3_6") (pintype "bidirectional"))
    )
    (net (code "161") (name "/B2Y4") (class "Default")
      (node (ref "J2") (pin "B4") (pintype "bidirectional"))
      (node (ref "R68") (pin "1") (pinfunction "1_1") (pintype "passive"))
      (node (ref "U5") (pin "5") (pinfunction "Y4_5") (pintype "bidirectional"))
    )
    (net (code "162") (name "/B2Y5") (class "Default")
      (node (ref "J2") (pin "B5") (pintype "bidirectional"))
      (node (ref "R52") (pin "1") (pinfunction "1_1") (pintype "passive"))
      (node (ref "U5") (pin "4") (pinfunction "Y5_4") (pintype "bidirectional"))
    )
    (net (code "163") (name "/B2Y6") (class "Default")
      (node (ref "J2") (pin "B6") (pintype "bidirectional"))
      (node (ref "R69") (pin "1") (pinfunction "1_1") (pintype "passive"))
      (node (ref "U5") (pin "3") (pinfunction "Y6_3") (pintype "bidirectional"))
    )
    (net (code "164") (name "/B2Y7") (class "Default")
      (node (ref "J2") (pin "B7") (pintype "bidirectional"))
      (node (ref "R53") (pin "1") (pinfunction "1_1") (pintype "passive"))
      (node (ref "U5") (pin "2") (pinfunction "Y7_2") (pintype "bidirectional"))
    )
    (net (code "165") (name "/B2Y8") (class "Default")
      (node (ref "J2") (pin "B8") (pintype "bidirectional"))
      (node (ref "R70") (pin "1") (pinfunction "1_1") (pintype "passive"))
      (node (ref "U5") (pin "23") (pinfunction "Y8_23") (pintype "bidirectional"))
    )
    (net (code "166") (name "/B2Y9") (class "Default")
      (node (ref "J2") (pin "B9") (pintype "bidirectional"))
      (node (ref "R54") (pin "1") (pinfunction "1_1") (pintype "passive"))
      (node (ref "U5") (pin "22") (pinfunction "Y9_22") (pintype "bidirectional"))
    )
    (net (code "167") (name "/B2Y10") (class "Default")
      (node (ref "J2") (pin "B10") (pintype "bidirectional"))
      (node (ref "R71") (pin "1") (pinfunction "1_1") (pintype "passive"))
      (node (ref "U5") (pin "21") (pinfunction "Y10_21") (pintype "bidirectional"))
    )
    (net (code "168") (name "/B2Y11") (class "Default")
      (node (ref "J2") (pin "B11") (pintype "bidirectional"))
      (node (ref "R55") (pin "1") (pinfunction "1_1") (pintype "passive"))
      (node (ref "U5") (pin "20") (pinfunction "Y11_20") (pintype "bidirectional"))
    )
    (net (code "169") (name "/B2Y12") (class "Default")
      (node (ref "J2") (pin "B12") (pintype "bidirectional"))
      (node (ref "R72") (pin "1") (pinfunction "1_1") (pintype "passive"))
      (node (ref "U5") (pin "19") (pinfunction "Y12_19") (pintype "bidirectional"))
    )
    (net (code "170") (name "/B2Y13") (class "Default")
      (node (ref "J2") (pin "B13") (pintype "bidirectional"))
      (node (ref "R56") (pin "1") (pinfunction "1_1") (pintype "passive"))
      (node (ref "U5") (pin "18") (pinfunction "Y13_18") (pintype "bidirectional"))
    )
    (net (code "171") (name "/B2Y14") (class "Default")
      (node (ref "J2") (pin "B14") (pintype "bidirectional"))
      (node (ref "R73") (pin "1") (pinfunction "1_1") (pintype "passive"))
      (node (ref "U5") (pin "17") (pinfunction "Y14_17") (pintype "bidirectional"))
    )
    (net (code "172") (name "/B2Y15") (class "Default")
      (node (ref "J2") (pin "B15") (pintype "bidirectional"))
      (node (ref "R57") (pin "1") (pinfunction "1_1") (pintype "passive"))
      (node (ref "U5") (pin "16") (pinfunction "Y15_16") (pintype "bidirectional"))
    )
    (net (code "173") (name "/B2_ENABLE") (class "Default")
      (node (ref "R252") (pin "1") (pinfunction "1_1") (pintype "passive"))
      (node (ref "U5") (pin "15") (pinfunction "/E_15") (pintype "input"))
    )
    (net (code "174") (name "/B2_Z_MCU") (class "Default")
      (node (ref "R40") (pin "1") (pinfunction "1_1") (pintype "passive"))
      (node (ref "U10") (pin "20") (pinfunction "EMUC3/AN1/VREF-/CN3/RB1_20") (pintype "bidirectional"))
    )
    (net (code "175") (name "/B3Y0") (class "Default")
      (node (ref "J2") (pin "B16") (pintype "bidirectional"))
      (node (ref "R74") (pin "1") (pinfunction "1_1") (pintype "passive"))
      (node (ref "U8") (pin "9") (pinfunction "Y0_9") (pintype "bidirectional"))
    )
    (net (code "176") (name "/B3Y1") (class "Default")
      (node (ref "J2") (pin "B17") (pintype "bidirectional"))
      (node (ref "R58") (pin "1") (pinfunction "1_1") (pintype "passive"))
      (node (ref "U8") (pin "8") (pinfunction "Y1_8") (pintype "bidirectional"))
    )
    (net (code "177") (name "/B3Y2") (class "Default")
      (node (ref "J2") (pin "C1") (pintype "bidirectional"))
      (node (ref "R94") (pin "1") (pinfunction "1_1") (pintype "passive"))
      (node (ref "U8") (pin "7") (pinfunction "Y2_7") (pintype "bidirectional"))
    )
    (net (code "178") (name "/B3Y3") (class "Default")
      (node (ref "J2") (pin "C2") (pintype "bidirectional"))
      (node (ref "R111") (pin "1") (pinfunction "1_1") (pintype "passive"))
      (node (ref "U8") (pin "6") (pinfunction "Y3_6") (pintype "bidirectional"))
    )
    (net (code "179") (name "/B3Y4") (class "Default")
      (node (ref "J2") (pin "C3") (pintype "bidirectional"))
      (node (ref "R95") (pin "1") (pinfunction "1_1") (pintype "passive"))
      (node (ref "U8") (pin "5") (pinfunction "Y4_5") (pintype "bidirectional"))
    )
    (net (code "180") (name "/B3Y5") (class "Default")
      (node (ref "J2") (pin "C4") (pintype "bidirectional"))
      (node (ref "R112") (pin "1") (pinfunction "1_1") (pintype "passive"))
      (node (ref "U8") (pin "4") (pinfunction "Y5_4") (pintype "bidirectional"))
    )
    (net (code "181") (name "/B3Y6") (class "Default")
      (node (ref "J2") (pin "C5") (pintype "bidirectional"))
      (node (ref "R96") (pin "1") (pinfunction "1_1") (pintype "passive"))
      (node (ref "U8") (pin "3") (pinfunction "Y6_3") (pintype "bidirectional"))
    )
    (net (code "182") (name "/B3Y7") (class "Default")
      (node (ref "J2") (pin "C6") (pintype "bidirectional"))
      (node (ref "R113") (pin "1") (pinfunction "1_1") (pintype "passive"))
      (node (ref "U8") (pin "2") (pinfunction "Y7_2") (pintype "bidirectional"))
    )
    (net (code "183") (name "/B3Y8") (class "Default")
      (node (ref "J2") (pin "C7") (pintype "bidirectional"))
      (node (ref "R97") (pin "1") (pinfunction "1_1") (pintype "passive"))
      (node (ref "U8") (pin "23") (pinfunction "Y8_23") (pintype "bidirectional"))
    )
    (net (code "184") (name "/B3Y9") (class "Default")
      (node (ref "J2") (pin "C8") (pintype "bidirectional"))
      (node (ref "R114") (pin "1") (pinfunction "1_1") (pintype "passive"))
      (node (ref "U8") (pin "22") (pinfunction "Y9_22") (pintype "bidirectional"))
    )
    (net (code "185") (name "/B3Y10") (class "Default")
      (node (ref "J2") (pin "C9") (pintype "bidirectional"))
      (node (ref "R98") (pin "1") (pinfunction "1_1") (pintype "passive"))
      (node (ref "U8") (pin "21") (pinfunction "Y10_21") (pintype "bidirectional"))
    )
    (net (code "186") (name "/B3Y11") (class "Default")
      (node (ref "J2") (pin "C10") (pintype "bidirectional"))
      (node (ref "R115") (pin "1") (pinfunction "1_1") (pintype "passive"))
      (node (ref "U8") (pin "20") (pinfunction "Y11_20") (pintype "bidirectional"))
    )
    (net (code "187") (name "/B3Y12") (class "Default")
      (node (ref "J2") (pin "C11") (pintype "bidirectional"))
      (node (ref "R99") (pin "1") (pinfunction "1_1") (pintype "passive"))
      (node (ref "U8") (pin "19") (pinfunction "Y12_19") (pintype "bidirectional"))
    )
    (net (code "188") (name "/B3Y13") (class "Default")
      (node (ref "J2") (pin "C12") (pintype "bidirectional"))
      (node (ref "R116") (pin "1") (pinfunction "1_1") (pintype "passive"))
      (node (ref "U8") (pin "18") (pinfunction "Y13_18") (pintype "bidirectional"))
    )
    (net (code "189") (name "/B3Y14") (class "Default")
      (node (ref "J2") (pin "C13") (pintype "bidirectional"))
      (node (ref "R100") (pin "1") (pinfunction "1_1") (pintype "passive"))
      (node (ref "U8") (pin "17") (pinfunction "Y14_17") (pintype "bidirectional"))
    )
    (net (code "190") (name "/B3Y15") (class "Default")
      (node (ref "J2") (pin "C14") (pintype "bidirectional"))
      (node (ref "R117") (pin "1") (pinfunction "1_1") (pintype "passive"))
      (node (ref "U8") (pin "16") (pinfunction "Y15_16") (pintype "bidirectional"))
    )
    (net (code "191") (name "/B3_ENABLE") (class "Default")
      (node (ref "R261") (pin "2") (pinfunction "2_2") (pintype "passive"))
      (node (ref "U8") (pin "15") (pinfunction "/E_15") (pintype "input"))
    )
    (net (code "192") (name "/B3_Z_MCU") (class "Default")
      (node (ref "R83") (pin "1") (pinfunction "1_1") (pintype "passive"))
      (node (ref "U10") (pin "23") (pinfunction "AN4/QEA/IC7/CN6/RB4_23") (pintype "bidirectional"))
    )
    (net (code "193") (name "/B4Y0") (class "Default")
      (node (ref "J2") (pin "C15") (pintype "bidirectional"))
      (node (ref "R101") (pin "1") (pinfunction "1_1") (pintype "passive"))
      (node (ref "U9") (pin "9") (pinfunction "Y0_9") (pintype "bidirectional"))
    )
    (net (code "194") (name "/B4Y1") (class "Default")
      (node (ref "J2") (pin "C16") (pintype "bidirectional"))
      (node (ref "R118") (pin "1") (pinfunction "1_1") (pintype "passive"))
      (node (ref "U9") (pin "8") (pinfunction "Y1_8") (pintype "bidirectional"))
    )
    (net (code "195") (name "/B4Y2") (class "Default")
      (node (ref "J2") (pin "C17") (pintype "bidirectional"))
      (node (ref "R102") (pin "1") (pinfunction "1_1") (pintype "passive"))
      (node (ref "U9") (pin "7") (pinfunction "Y2_7") (pintype "bidirectional"))
    )
    (net (code "196") (name "/B4Y3") (class "Default")
      (node (ref "J2") (pin "D1") (pintype "bidirectional"))
      (node (ref "R132") (pin "1") (pinfunction "1_1") (pintype "passive"))
      (node (ref "U9") (pin "6") (pinfunction "Y3_6") (pintype "bidirectional"))
    )
    (net (code "197") (name "/B4Y4") (class "Default")
      (node (ref "J2") (pin "D2") (pintype "bidirectional"))
      (node (ref "R149") (pin "1") (pinfunction "1_1") (pintype "passive"))
      (node (ref "U9") (pin "5") (pinfunction "Y4_5") (pintype "bidirectional"))
    )
    (net (code "198") (name "/B4Y5") (class "Default")
      (node (ref "J2") (pin "D3") (pintype "bidirectional"))
      (node (ref "R133") (pin "1") (pinfunction "1_1") (pintype "passive"))
      (node (ref "U9") (pin "4") (pinfunction "Y5_4") (pintype "bidirectional"))
    )
    (net (code "199") (name "/B4Y6") (class "Default")
      (node (ref "J2") (pin "D4") (pintype "bidirectional"))
      (node (ref "R150") (pin "1") (pinfunction "1_1") (pintype "passive"))
      (node (ref "U9") (pin "3") (pinfunction "Y6_3") (pintype "bidirectional"))
    )
    (net (code "200") (name "/B4Y7") (class "Default")
      (node (ref "J2") (pin "D5") (pintype "bidirectional"))
      (node (ref "R134") (pin "1") (pinfunction "1_1") (pintype "passive"))
      (node (ref "U9") (pin "2") (pinfunction "Y7_2") (pintype "bidirectional"))
    )
    (net (code "201") (name "/B4Y8") (class "Default")
      (node (ref "J2") (pin "D6") (pintype "bidirectional"))
      (node (ref "R151") (pin "1") (pinfunction "1_1") (pintype "passive"))
      (node (ref "U9") (pin "23") (pinfunction "Y8_23") (pintype "bidirectional"))
    )
    (net (code "202") (name "/B4Y9") (class "Default")
      (node (ref "J2") (pin "D7") (pintype "bidirectional"))
      (node (ref "R135") (pin "1") (pinfunction "1_1") (pintype "passive"))
      (node (ref "U9") (pin "22") (pinfunction "Y9_22") (pintype "bidirectional"))
    )
    (net (code "203") (name "/B4Y10") (class "Default")
      (node (ref "J2") (pin "D8") (pintype "bidirectional"))
      (node (ref "R152") (pin "1") (pinfunction "1_1") (pintype "passive"))
      (node (ref "U9") (pin "21") (pinfunction "Y10_21") (pintype "bidirectional"))
    )
    (net (code "204") (name "/B4Y11") (class "Default")
      (node (ref "J2") (pin "D9") (pintype "bidirectional"))
      (node (ref "R136") (pin "1") (pinfunction "1_1") (pintype "passive"))
      (node (ref "U9") (pin "20") (pinfunction "Y11_20") (pintype "bidirectional"))
    )
    (net (code "205") (name "/B4Y12") (class "Default")
      (node (ref "J2") (pin "D10") (pintype "bidirectional"))
      (node (ref "R153") (pin "1") (pinfunction "1_1") (pintype "passive"))
      (node (ref "U9") (pin "19") (pinfunction "Y12_19") (pintype "bidirectional"))
    )
    (net (code "206") (name "/B4Y13") (class "Default")
      (node (ref "J2") (pin "D11") (pintype "bidirectional"))
      (node (ref "R137") (pin "1") (pinfunction "1_1") (pintype "passive"))
      (node (ref "U9") (pin "18") (pinfunction "Y13_18") (pintype "bidirectional"))
    )
    (net (code "207") (name "/B4Y14") (class "Default")
      (node (ref "J2") (pin "D12") (pintype "bidirectional"))
      (node (ref "R154") (pin "1") (pinfunction "1_1") (pintype "passive"))
      (node (ref "U9") (pin "17") (pinfunction "Y14_17") (pintype "bidirectional"))
    )
    (net (code "208") (name "/B4Y15") (class "Default")
      (node (ref "J2") (pin "D13") (pintype "bidirectional"))
      (node (ref "R138") (pin "1") (pinfunction "1_1") (pintype "passive"))
      (node (ref "U9") (pin "16") (pinfunction "Y15_16") (pintype "bidirectional"))
    )
    (net (code "209") (name "/B4_ENABLE") (class "Default")
      (node (ref "R253") (pin "2") (pinfunction "2_2") (pintype "passive"))
      (node (ref "U9") (pin "15") (pinfunction "/E_15") (pintype "input"))
    )
    (net (code "210") (name "/B4_Z_MCU") (class "Default")
      (node (ref "R84") (pin "1") (pinfunction "1_1") (pintype "passive"))
      (node (ref "U10") (pin "25") (pinfunction "AN6/OCFA/RB6_25") (pintype "bidirectional"))
    )
    (net (code "211") (name "/B5Y0") (class "Default")
      (node (ref "J2") (pin "D14") (pintype "bidirectional"))
      (node (ref "R155") (pin "1") (pinfunction "1_1") (pintype "passive"))
      (node (ref "U13") (pin "9") (pinfunction "Y0_9") (pintype "bidirectional"))
    )
    (net (code "212") (name "/B5Y1") (class "Default")
      (node (ref "J2") (pin "D15") (pintype "bidirectional"))
      (node (ref "R139") (pin "1") (pinfunction "1_1") (pintype "passive"))
      (node (ref "U13") (pin "8") (pinfunction "Y1_8") (pintype "bidirectional"))
    )
    (net (code "213") (name "/B5Y2") (class "Default")
      (node (ref "J2") (pin "D16") (pintype "bidirectional"))
      (node (ref "R156") (pin "1") (pinfunction "1_1") (pintype "passive"))
      (node (ref "U13") (pin "7") (pinfunction "Y2_7") (pintype "bidirectional"))
    )
    (net (code "214") (name "/B5Y3") (class "Default")
      (node (ref "J2") (pin "D17") (pintype "bidirectional"))
      (node (ref "R140") (pin "1") (pinfunction "1_1") (pintype "passive"))
      (node (ref "U13") (pin "6") (pinfunction "Y3_6") (pintype "bidirectional"))
    )
    (net (code "215") (name "/B5Y4") (class "Default")
      (node (ref "J2") (pin "E1") (pintype "bidirectional"))
      (node (ref "R171") (pin "1") (pinfunction "1_1") (pintype "passive"))
      (node (ref "U13") (pin "5") (pinfunction "Y4_5") (pintype "bidirectional"))
    )
    (net (code "216") (name "/B5Y5") (class "Default")
      (node (ref "J2") (pin "E2") (pintype "bidirectional"))
      (node (ref "R188") (pin "1") (pinfunction "1_1") (pintype "passive"))
      (node (ref "U13") (pin "4") (pinfunction "Y5_4") (pintype "bidirectional"))
    )
    (net (code "217") (name "/B5Y6") (class "Default")
      (node (ref "J2") (pin "E3") (pintype "bidirectional"))
      (node (ref "R172") (pin "1") (pinfunction "1_1") (pintype "passive"))
      (node (ref "U13") (pin "3") (pinfunction "Y6_3") (pintype "bidirectional"))
    )
    (net (code "218") (name "/B5Y7") (class "Default")
      (node (ref "J2") (pin "E4") (pintype "bidirectional"))
      (node (ref "R189") (pin "1") (pinfunction "1_1") (pintype "passive"))
      (node (ref "U13") (pin "2") (pinfunction "Y7_2") (pintype "bidirectional"))
    )
    (net (code "219") (name "/B5Y8") (class "Default")
      (node (ref "J2") (pin "E5") (pintype "bidirectional"))
      (node (ref "R173") (pin "1") (pinfunction "1_1") (pintype "passive"))
      (node (ref "U13") (pin "23") (pinfunction "Y8_23") (pintype "bidirectional"))
    )
    (net (code "220") (name "/B5Y9") (class "Default")
      (node (ref "J2") (pin "E6") (pintype "bidirectional"))
      (node (ref "R190") (pin "1") (pinfunction "1_1") (pintype "passive"))
      (node (ref "U13") (pin "22") (pinfunction "Y9_22") (pintype "bidirectional"))
    )
    (net (code "221") (name "/B5Y10") (class "Default")
      (node (ref "J2") (pin "E7") (pintype "bidirectional"))
      (node (ref "R174") (pin "1") (pinfunction "1_1") (pintype "passive"))
      (node (ref "U13") (pin "21") (pinfunction "Y10_21") (pintype "bidirectional"))
    )
    (net (code "222") (name "/B5Y11") (class "Default")
      (node (ref "J2") (pin "E8") (pintype "bidirectional"))
      (node (ref "R191") (pin "1") (pinfunction "1_1") (pintype "passive"))
      (node (ref "U13") (pin "20") (pinfunction "Y11_20") (pintype "bidirectional"))
    )
    (net (code "223") (name "/B5Y12") (class "Default")
      (node (ref "J2") (pin "E9") (pintype "bidirectional"))
      (node (ref "R175") (pin "1") (pinfunction "1_1") (pintype "passive"))
      (node (ref "U13") (pin "19") (pinfunction "Y12_19") (pintype "bidirectional"))
    )
    (net (code "224") (name "/B5Y13") (class "Default")
      (node (ref "J2") (pin "E10") (pintype "bidirectional"))
      (node (ref "R192") (pin "1") (pinfunction "1_1") (pintype "passive"))
      (node (ref "U13") (pin "18") (pinfunction "Y13_18") (pintype "bidirectional"))
    )
    (net (code "225") (name "/B5Y14") (class "Default")
      (node (ref "J2") (pin "E11") (pintype "bidirectional"))
      (node (ref "R176") (pin "1") (pinfunction "1_1") (pintype "passive"))
      (node (ref "U13") (pin "17") (pinfunction "Y14_17") (pintype "bidirectional"))
    )
    (net (code "226") (name "/B5Y15") (class "Default")
      (node (ref "J2") (pin "E12") (pintype "bidirectional"))
      (node (ref "R193") (pin "1") (pinfunction "1_1") (pintype "passive"))
      (node (ref "U13") (pin "16") (pinfunction "Y15_16") (pintype "bidirectional"))
    )
    (net (code "227") (name "/B5_ENABLE") (class "Default")
      (node (ref "R256") (pin "1") (pinfunction "1_1") (pintype "passive"))
      (node (ref "U13") (pin "15") (pinfunction "/E_15") (pintype "input"))
    )
    (net (code "228") (name "/B5_Z_MCU") (class "Default")
      (node (ref "R121") (pin "1") (pinfunction "1_1") (pintype "passive"))
      (node (ref "U10") (pin "21") (pinfunction "AN2/~{SS1}/CN4/RB2_21") (pintype "bidirectional"))
    )
    (net (code "229") (name "/B6Y0") (class "Default")
      (node (ref "J2") (pin "E13") (pintype "bidirectional"))
      (node (ref "R177") (pin "1") (pinfunction "1_1") (pintype "passive"))
      (node (ref "U14") (pin "9") (pinfunction "Y0_9") (pintype "bidirectional"))
    )
    (net (code "230") (name "/B6Y1") (class "Default")
      (node (ref "J2") (pin "E14") (pintype "bidirectional"))
      (node (ref "R194") (pin "1") (pinfunction "1_1") (pintype "passive"))
      (node (ref "U14") (pin "8") (pinfunction "Y1_8") (pintype "bidirectional"))
    )
    (net (code "231") (name "/B6Y2") (class "Default")
      (node (ref "J2") (pin "E15") (pintype "bidirectional"))
      (node (ref "R178") (pin "1") (pinfunction "1_1") (pintype "passive"))
      (node (ref "U14") (pin "7") (pinfunction "Y2_7") (pintype "bidirectional"))
    )
    (net (code "232") (name "/B6Y3") (class "Default")
      (node (ref "J2") (pin "E16") (pintype "bidirectional"))
      (node (ref "R195") (pin "1") (pinfunction "1_1") (pintype "passive"))
      (node (ref "U14") (pin "6") (pinfunction "Y3_6") (pintype "bidirectional"))
    )
    (net (code "233") (name "/B6Y4") (class "Default")
      (node (ref "J2") (pin "F1") (pintype "bidirectional"))
      (node (ref "R204") (pin "1") (pinfunction "1_1") (pintype "passive"))
      (node (ref "U14") (pin "5") (pinfunction "Y4_5") (pintype "bidirectional"))
    )
    (net (code "234") (name "/B6Y5") (class "Default")
      (node (ref "J2") (pin "F2") (pintype "bidirectional"))
      (node (ref "R228") (pin "1") (pinfunction "1_1") (pintype "passive"))
      (node (ref "U14") (pin "4") (pinfunction "Y5_4") (pintype "bidirectional"))
    )
    (net (code "235") (name "/B6Y6") (class "Default")
      (node (ref "J2") (pin "F3") (pintype "bidirectional"))
      (node (ref "R205") (pin "1") (pinfunction "1_1") (pintype "passive"))
      (node (ref "U14") (pin "3") (pinfunction "Y6_3") (pintype "bidirectional"))
    )
    (net (code "236") (name "/B6Y7") (class "Default")
      (node (ref "J2") (pin "F4") (pintype "bidirectional"))
      (node (ref "R229") (pin "1") (pinfunction "1_1") (pintype "passive"))
      (node (ref "U14") (pin "2") (pinfunction "Y7_2") (pintype "bidirectional"))
    )
    (net (code "237") (name "/B6Y8") (class "Default")
      (node (ref "J2") (pin "F5") (pintype "bidirectional"))
      (node (ref "R206") (pin "1") (pinfunction "1_1") (pintype "passive"))
      (node (ref "U14") (pin "23") (pinfunction "Y8_23") (pintype "bidirectional"))
    )
    (net (code "238") (name "/B6Y9") (class "Default")
      (node (ref "J2") (pin "F6") (pintype "bidirectional"))
      (node (ref "R230") (pin "1") (pinfunction "1_1") (pintype "passive"))
      (node (ref "U14") (pin "22") (pinfunction "Y9_22") (pintype "bidirectional"))
    )
    (net (code "239") (name "/B6Y10") (class "Default")
      (node (ref "J2") (pin "F7") (pintype "bidirectional"))
      (node (ref "R207") (pin "1") (pinfunction "1_1") (pintype "passive"))
      (node (ref "U14") (pin "21") (pinfunction "Y10_21") (pintype "bidirectional"))
    )
    (net (code "240") (name "/B6Y11") (class "Default")
      (node (ref "J2") (pin "F8") (pintype "bidirectional"))
      (node (ref "R231") (pin "1") (pinfunction "1_1") (pintype "passive"))
      (node (ref "U14") (pin "20") (pinfunction "Y11_20") (pintype "bidirectional"))
    )
    (net (code "241") (name "/B6Y12") (class "Default")
      (node (ref "J2") (pin "F9") (pintype "bidirectional"))
      (node (ref "R208") (pin "1") (pinfunction "1_1") (pintype "passive"))
      (node (ref "U14") (pin "19") (pinfunction "Y12_19") (pintype "bidirectional"))
    )
    (net (code "242") (name "/B6Y13") (class "Default")
      (node (ref "J2") (pin "F10") (pintype "bidirectional"))
      (node (ref "R232") (pin "1") (pinfunction "1_1") (pintype "passive"))
      (node (ref "U14") (pin "18") (pinfunction "Y13_18") (pintype "bidirectional"))
    )
    (net (code "243") (name "/B6Y14") (class "Default")
      (node (ref "J2") (pin "F11") (pintype "bidirectional"))
      (node (ref "R209") (pin "1") (pinfunction "1_1") (pintype "passive"))
      (node (ref "U14") (pin "17") (pinfunction "Y14_17") (pintype "bidirectional"))
    )
    (net (code "244") (name "/B6Y15") (class "Default")
      (node (ref "J2") (pin "F12") (pintype "bidirectional"))
      (node (ref "R233") (pin "1") (pinfunction "1_1") (pintype "passive"))
      (node (ref "U14") (pin "16") (pinfunction "Y15_16") (pintype "bidirectional"))
    )
    (net (code "245") (name "/B6_ENABLE") (class "Default")
      (node (ref "R248") (pin "1") (pinfunction "1_1") (pintype "passive"))
      (node (ref "U14") (pin "15") (pinfunction "/E_15") (pintype "input"))
    )
    (net (code "246") (name "/B6_Z_MCU") (class "Default")
      (node (ref "R122") (pin "1") (pinfunction "1_1") (pintype "passive"))
      (node (ref "U10") (pin "19") (pinfunction "EMUD3/AN0/VREF+/CN2/RB0_19") (pintype "bidirectional"))
    )
    (net (code "247") (name "/B7Y0") (class "Default")
      (node (ref "J2") (pin "F13") (pintype "bidirectional"))
      (node (ref "R210") (pin "1") (pinfunction "1_1") (pintype "passive"))
      (node (ref "U17") (pin "9") (pinfunction "Y0_9") (pintype "bidirectional"))
    )
    (net (code "248") (name "/B7Y1") (class "Default")
      (node (ref "J2") (pin "F14") (pintype "bidirectional"))
      (node (ref "R234") (pin "1") (pinfunction "1_1") (pintype "passive"))
      (node (ref "U17") (pin "8") (pinfunction "Y1_8") (pintype "bidirectional"))
    )
    (net (code "249") (name "/B7Y2") (class "Default")
      (node (ref "J2") (pin "F15") (pintype "bidirectional"))
      (node (ref "R211") (pin "1") (pinfunction "1_1") (pintype "passive"))
      (node (ref "U17") (pin "7") (pinfunction "Y2_7") (pintype "bidirectional"))
    )
    (net (code "250") (name "/B7Y3") (class "Default")
      (node (ref "J2") (pin "F16") (pintype "bidirectional"))
      (node (ref "R235") (pin "1") (pinfunction "1_1") (pintype "passive"))
      (node (ref "U17") (pin "6") (pinfunction "Y3_6") (pintype "bidirectional"))
    )
    (net (code "251") (name "/B7Y4") (class "Default")
      (node (ref "J2") (pin "G1") (pintype "bidirectional"))
      (node (ref "R277") (pin "1") (pinfunction "1_1") (pintype "passive"))
      (node (ref "U17") (pin "5") (pinfunction "Y4_5") (pintype "bidirectional"))
    )
    (net (code "252") (name "/B7Y5") (class "Default")
      (node (ref "J2") (pin "G2") (pintype "bidirectional"))
      (node (ref "R293") (pin "1") (pinfunction "1_1") (pintype "passive"))
      (node (ref "U17") (pin "4") (pinfunction "Y5_4") (pintype "bidirectional"))
    )
    (net (code "253") (name "/B7Y6") (class "Default")
      (node (ref "J2") (pin "G3") (pintype "bidirectional"))
      (node (ref "R278") (pin "1") (pinfunction "1_1") (pintype "passive"))
      (node (ref "U17") (pin "3") (pinfunction "Y6_3") (pintype "bidirectional"))
    )
    (net (code "254") (name "/B7Y7") (class "Default")
      (node (ref "J2") (pin "G4") (pintype "bidirectional"))
      (node (ref "R294") (pin "1") (pinfunction "1_1") (pintype "passive"))
      (node (ref "U17") (pin "2") (pinfunction "Y7_2") (pintype "bidirectional"))
    )
    (net (code "255") (name "/B7Y8") (class "Default")
      (node (ref "J2") (pin "G5") (pintype "bidirectional"))
      (node (ref "R279") (pin "1") (pinfunction "1_1") (pintype "passive"))
      (node (ref "U17") (pin "23") (pinfunction "Y8_23") (pintype "bidirectional"))
    )
    (net (code "256") (name "/B7Y9") (class "Default")
      (node (ref "J2") (pin "G6") (pintype "bidirectional"))
      (node (ref "R295") (pin "1") (pinfunction "1_1") (pintype "passive"))
      (node (ref "U17") (pin "22") (pinfunction "Y9_22") (pintype "bidirectional"))
    )
    (net (code "257") (name "/B7Y10") (class "Default")
      (node (ref "J2") (pin "G7") (pintype "bidirectional"))
      (node (ref "R280") (pin "1") (pinfunction "1_1") (pintype "passive"))
      (node (ref "U17") (pin "21") (pinfunction "Y10_21") (pintype "bidirectional"))
    )
    (net (code "258") (name "/B7Y11") (class "Default")
      (node (ref "J2") (pin "G8") (pintype "bidirectional"))
      (node (ref "R296") (pin "1") (pinfunction "1_1") (pintype "passive"))
      (node (ref "U17") (pin "20") (pinfunction "Y11_20") (pintype "bidirectional"))
    )
    (net (code "259") (name "/B7Y12") (class "Default")
      (node (ref "J2") (pin "G9") (pintype "bidirectional"))
      (node (ref "R281") (pin "1") (pinfunction "1_1") (pintype "passive"))
      (node (ref "U17") (pin "19") (pinfunction "Y12_19") (pintype "bidirectional"))
    )
    (net (code "260") (name "/B7Y13") (class "Default")
      (node (ref "J2") (pin "G10") (pintype "bidirectional"))
      (node (ref "R297") (pin "1") (pinfunction "1_1") (pintype "passive"))
      (node (ref "U17") (pin "18") (pinfunction "Y13_18") (pintype "bidirectional"))
    )
    (net (code "261") (name "/B7Y14") (class "Default")
      (node (ref "J2") (pin "G11") (pintype "bidirectional"))
      (node (ref "R282") (pin "1") (pinfunction "1_1") (pintype "passive"))
      (node (ref "U17") (pin "17") (pinfunction "Y14_17") (pintype "bidirectional"))
    )
    (net (code "262") (name "/B7Y15") (class "Default")
      (node (ref "J2") (pin "G12") (pintype "bidirectional"))
      (node (ref "R298") (pin "1") (pinfunction "1_1") (pintype "passive"))
      (node (ref "U17") (pin "16") (pinfunction "Y15_16") (pintype "bidirectional"))
    )
    (net (code "263") (name "/B7_ENABLE") (class "Default")
      (node (ref "R257") (pin "2") (pinfunction "2_2") (pintype "passive"))
      (node (ref "U17") (pin "15") (pinfunction "/E_15") (pintype "input"))
    )
    (net (code "264") (name "/B7_Z_MCU") (class "Default")
      (node (ref "R161") (pin "1") (pinfunction "1_1") (pintype "passive"))
      (node (ref "U10") (pin "24") (pinfunction "AN5/QEB/IC8/CN7/RB5_24") (pintype "bidirectional"))
    )
    (net (code "265") (name "/B8Y0") (class "Default")
      (node (ref "J2") (pin "G13") (pintype "bidirectional"))
      (node (ref "R283") (pin "1") (pinfunction "1_1") (pintype "passive"))
      (node (ref "U18") (pin "9") (pinfunction "Y0_9") (pintype "bidirectional"))
    )
    (net (code "266") (name "/B8Y1") (class "Default")
      (node (ref "J2") (pin "G14") (pintype "bidirectional"))
      (node (ref "R299") (pin "1") (pinfunction "1_1") (pintype "passive"))
      (node (ref "U18") (pin "8") (pinfunction "Y1_8") (pintype "bidirectional"))
    )
    (net (code "267") (name "/B8Y2") (class "Default")
      (node (ref "J2") (pin "G15") (pintype "bidirectional"))
      (node (ref "R284") (pin "1") (pinfunction "1_1") (pintype "passive"))
      (node (ref "U18") (pin "7") (pinfunction "Y2_7") (pintype "bidirectional"))
    )
    (net (code "268") (name "/B8Y3") (class "Default")
      (node (ref "J2") (pin "G16") (pintype "bidirectional"))
      (node (ref "R300") (pin "1") (pinfunction "1_1") (pintype "passive"))
      (node (ref "U18") (pin "6") (pinfunction "Y3_6") (pintype "bidirectional"))
    )
    (net (code "269") (name "/B8_ENABLE") (class "Default")
      (node (ref "R249") (pin "2") (pinfunction "2_2") (pintype "passive"))
      (node (ref "U18") (pin "15") (pinfunction "/E_15") (pintype "input"))
    )
    (net (code "270") (name "/B8_Z_MCU") (class "Default")
      (node (ref "R162") (pin "1") (pinfunction "1_1") (pintype "passive"))
      (node (ref "U10") (pin "26") (pinfunction "AN7/RB7_26") (pintype "bidirectional"))
    )
    (net (code "271") (name "/BS0") (class "Default")
      (node (ref "R237") (pin "1") (pinfunction "1_1") (pintype "passive"))
      (node (ref "U13") (pin "10") (pinfunction "S0_10") (pintype "input"))
      (node (ref "U14") (pin "10") (pinfunction "S0_10") (pintype "input"))
      (node (ref "U17") (pin "10") (pinfunction "S0_10") (pintype "input"))
      (node (ref "U18") (pin "10") (pinfunction "S0_10") (pintype "input"))
      (node (ref "U4") (pin "10") (pinfunction "S0_10") (pintype "input"))
      (node (ref "U5") (pin "10") (pinfunction "S0_10") (pintype "input"))
      (node (ref "U8") (pin "10") (pinfunction "S0_10") (pintype "input"))
      (node (ref "U9") (pin "10") (pinfunction "S0_10") (pintype "input"))
    )
    (net (code "272") (name "/BS1") (class "Default")
      (node (ref "R240") (pin "1") (pinfunction "1_1") (pintype "passive"))
      (node (ref "U13") (pin "11") (pinfunction "S1_11") (pintype "input"))
      (node (ref "U14") (pin "11") (pinfunction "S1_11") (pintype "input"))
      (node (ref "U17") (pin "11") (pinfunction "S1_11") (pintype "input"))
      (node (ref "U18") (pin "11") (pinfunction "S1_11") (pintype "input"))
      (node (ref "U4") (pin "11") (pinfunction "S1_11") (pintype "input"))
      (node (ref "U5") (pin "11") (pinfunction "S1_11") (pintype "input"))
      (node (ref "U8") (pin "11") (pinfunction "S1_11") (pintype "input"))
      (node (ref "U9") (pin "11") (pinfunction "S1_11") (pintype "input"))
    )
    (net (code "273") (name "/BS2") (class "Default")
      (node (ref "R242") (pin "1") (pinfunction "1_1") (pintype "passive"))
      (node (ref "U13") (pin "14") (pinfunction "S2_14") (pintype "input"))
      (node (ref "U14") (pin "14") (pinfunction "S2_14") (pintype "input"))
      (node (ref "U17") (pin "14") (pinfunction "S2_14") (pintype "input"))
      (node (ref "U18") (pin "14") (pinfunction "S2_14") (pintype "input"))
      (node (ref "U4") (pin "14") (pinfunction "S2_14") (pintype "input"))
      (node (ref "U5") (pin "14") (pinfunction "S2_14") (pintype "input"))
      (node (ref "U8") (pin "14") (pinfunction "S2_14") (pintype "input"))
      (node (ref "U9") (pin "14") (pinfunction "S2_14") (pintype "input"))
    )
    (net (code "274") (name "/BS3") (class "Default")
      (node (ref "R244") (pin "1") (pinfunction "1_1") (pintype "passive"))
      (node (ref "U13") (pin "13") (pinfunction "S3_13") (pintype "input"))
      (node (ref "U14") (pin "13") (pinfunction "S3_13") (pintype "input"))
      (node (ref "U17") (pin "13") (pinfunction "S3_13") (pintype "input"))
      (node (ref "U18") (pin "13") (pinfunction "S3_13") (pintype "input"))
      (node (ref "U4") (pin "13") (pinfunction "S3_13") (pintype "input"))
      (node (ref "U5") (pin "13") (pinfunction "S3_13") (pintype "input"))
      (node (ref "U8") (pin "13") (pinfunction "S3_13") (pintype "input"))
      (node (ref "U9") (pin "13") (pinfunction "S3_13") (pintype "input"))
    )
    (net (code "275") (name "/BUTTON1") (class "Default")
      (node (ref "C28") (pin "1") (pinfunction "1_1") (pintype "passive"))
      (node (ref "R158") (pin "1") (pinfunction "1_1") (pintype "passive"))
      (node (ref "SW1") (pin "1") (pintype "passive"))
      (node (ref "SW1") (pin "3") (pintype "passive"))
      (node (ref "U10") (pin "36") (pinfunction "~{FLTA}/INT0/RE8_36") (pintype "bidirectional"))
    )
    (net (code "276") (name "/BUTTON2") (class "Default")
      (node (ref "C29") (pin "1") (pinfunction "1_1") (pintype "passive"))
      (node (ref "R179") (pin "1") (pinfunction "1_1") (pintype "passive"))
      (node (ref "SW2") (pin "1") (pintype "passive"))
      (node (ref "SW2") (pin "3") (pintype "passive"))
      (node (ref "U10") (pin "37") (pinfunction "EMUD2/OC2/IC2/INT2/RD1_37") (pintype "bidirectional"))
    )
    (net (code "277") (name "/CNN_D_N") (class "Default")
      (node (ref "J3") (pin "2") (pinfunction "D-_2") (pintype "bidirectional"))
      (node (ref "R301") (pin "2") (pinfunction "2_2") (pintype "passive"))
    )
    (net (code "278") (name "/CNN_D_P") (class "Default")
      (node (ref "J3") (pin "3") (pinfunction "D+_3") (pintype "bidirectional"))
      (node (ref "R302") (pin "2") (pinfunction "2_2") (pintype "passive"))
    )
    (net (code "280") (name "/LED1") (class "Default")
      (node (ref "R76") (pin "2") (pinfunction "2_2") (pintype "passive"))
      (node (ref "U10") (pin "27") (pinfunction "AN8/RB8_27") (pintype "bidirectional"))
    )
    (net (code "281") (name "/LED2") (class "Default")
      (node (ref "R77") (pin "2") (pinfunction "2_2") (pintype "passive"))
      (node (ref "U10") (pin "32") (pinfunction "EMUD1/SOSCI/T2CK/U1ATX/CN1/RC13_32") (pintype "bidirectional"))
    )
    (net (code "282") (name "/LED3") (class "Default")
      (node (ref "R78") (pin "2") (pinfunction "2_2") (pintype "passive"))
      (node (ref "U10") (pin "35") (pinfunction "EMUC1/SOSCO/T1CK/U1ARX/CN0/RC14_35") (pintype "bidirectional"))
    )
    (net (code "283") (name "/LED4") (class "Default")
      (node (ref "R79") (pin "2") (pinfunction "2_2") (pintype "passive"))
      (node (ref "U10") (pin "38") (pinfunction "OC4/RD3_38") (pintype "bidirectional"))
    )
    (net (code "284") (name "/LED5") (class "Default")
      (node (ref "R80") (pin "2") (pinfunction "2_2") (pintype "passive"))
      (node (ref "U10") (pin "41") (pinfunction "OC3/RD2_41") (pintype "bidirectional"))
    )
    (net (code "285") (name "/MCLR") (class "Default")
      (node (ref "ICSP 1") (pin "1") (pinfunction "1_1") (pintype "passive"))
      (node (ref "R157") (pin "2") (pinfunction "2_2") (pintype "passive"))
      (node (ref "U10") (pin "18") (pinfunction "~{MCLR}_18") (pintype "input"))
    )
    (net (code "287") (name "/OSC1") (class "Default")
      (node (ref "C18") (pin "1") (pinfunction "1_1") (pintype "passive"))
      (node (ref "U10") (pin "30") (pinfunction "OSC1/CLKI_30") (pintype "input"))
      (node (ref "X1") (pin "2") (pinfunction "2_2") (pintype "passive"))
    )
    (net (code "288") (name "/OSC2") (class "Default")
      (node (ref "C23") (pin "1") (pinfunction "1_1") (pintype "passive"))
      (node (ref "U10") (pin "31") (pinfunction "OSC2/CLKO/RC15_31") (pintype "bidirectional"))
      (node (ref "X1") (pin "1") (pinfunction "1_1") (pintype "passive"))
    )
    (net (code "289") (name "/PGC") (class "Default")
      (node (ref "ICSP 1") (pin "5") (pinfunction "5_5") (pintype "passive"))
      (node (ref "R262") (pin "1") (pinfunction "1_1") (pintype "passive"))
      (node (ref "U10") (pin "1") (pinfunction "PGC/EMUC/U1RX/SDI1/SDA/RF2_1") (pintype "bidirectional"))
    )
    (net (code "290") (name "/PGD") (class "Default")
      (node (ref "ICSP 1") (pin "4") (pinfunction "4_4") (pintype "passive"))
      (node (ref "R218") (pin "1") (pinfunction "1_1") (pintype "passive"))
      (node (ref "U10") (pin "44") (pinfunction "PGD/EMUD/U1TX/SDO1/SCL/RF3_44") (pintype "bidirectional"))
    )
    (net (code "292") (name "/SCL1_MCU") (class "Default")
      (node (ref "R213") (pin "2") (pinfunction "2_2") (pintype "passive"))
      (node (ref "R218") (pin "2") (pinfunction "2_2") (pintype "passive"))
      (node (ref "R219") (pin "2") (pinfunction "2_2") (pintype "passive"))
      (node (ref "U19") (pin "22") (pinfunction "SCL_22") (pintype "input"))
    )
    (net (code "293") (name "/SCL2_MCU") (class "Default")
      (node (ref "R239") (pin "2") (pinfunction "2_2") (pintype "passive"))
      (node (ref "U10") (pin "42") (pinfunction "EMUC2/OC1/IC1/INT1/RD0_42") (pintype "bidirectional"))
    )
    (net (code "294") (name "/SDA1_MCU") (class "Default")
      (node (ref "R212") (pin "2") (pinfunction "2_2") (pintype "passive"))
      (node (ref "R262") (pin "2") (pinfunction "2_2") (pintype "passive"))
      (node (ref "R263") (pin "2") (pinfunction "2_2") (pintype "passive"))
      (node (ref "U19") (pin "23") (pinfunction "SDA_23") (pintype "bidirectional"))
    )
    (net (code "295") (name "/SDA2_MCU") (class "Default")
      (node (ref "R265") (pin "2") (pinfunction "2_2") (pintype "passive"))
      (node (ref "U10") (pin "43") (pinfunction "SCK1/RF6_43") (pintype "bidirectional"))
    )
    (net (code "297") (name "/U2RX_MCU") (class "Default")
      (node (ref "R264") (pin "2") (pinfunction "2_2") (pintype "passive"))
      (node (ref "U10") (pin "3") (pinfunction "U2RX/CN17/RF4_3") (pintype "bidirectional"))
    )
    (net (code "298") (name "/U2TX_MCU") (class "Default")
      (node (ref "R266") (pin "2") (pinfunction "2_2") (pintype "passive"))
      (node (ref "U10") (pin "2") (pinfunction "U2TX/CN18/RF5_2") (pintype "bidirectional"))
    )
    (net (code "300") (name "/USBD_N") (class "Default")
      (node (ref "R301") (pin "1") (pinfunction "1_1") (pintype "passive"))
      (node (ref "U21") (pin "16") (pinfunction "USBDM_16") (pintype "bidirectional"))
    )
    (net (code "301") (name "/USBD_P") (class "Default")
      (node (ref "R302") (pin "1") (pinfunction "1_1") (pintype "passive"))
      (node (ref "U21") (pin "15") (pinfunction "USBDP_15") (pintype "bidirectional"))
    )
    (net (code "302") (name "GND") (class "Default")
      (node (ref "C1") (pin "2") (pinfunction "2_2") (pintype "passive"))
      (node (ref "C10") (pin "2") (pinfunction "2_2") (pintype "passive"))
      (node (ref "C11") (pin "2") (pinfunction "2_2") (pintype "passive"))
      (node (ref "C12") (pin "2") (pinfunction "2_2") (pintype "passive"))
      (node (ref "C13") (pin "2") (pinfunction "2_2") (pintype "passive"))
      (node (ref "C14") (pin "2") (pinfunction "2_2") (pintype "passive"))
      (node (ref "C15") (pin "2") (pinfunction "2_2") (pintype "passive"))
      (node (ref "C16") (pin "2") (pinfunction "2_2") (pintype "passive"))
      (node (ref "C17") (pin "2") (pinfunction "2_2") (pintype "passive"))
      (node (ref "C18") (pin "2") (pinfunction "2_2") (pintype "passive"))
      (node (ref "C19") (pin "2") (pinfunction "2_2") (pintype "passive"))
      (node (ref "C2") (pin "2") (pinfunction "2_2") (pintype "passive"))
      (node (ref "C20") (pin "2") (pinfunction "2_2") (pintype "passive"))
      (node (ref "C21") (pin "2") (pinfunction "2_2") (pintype "passive"))
      (node (ref "C22") (pin "2") (pinfunction "2_2") (pintype "passive"))
      (node (ref "C23") (pin "2") (pinfunction "2_2") (pintype "passive"))
      (node (ref "C24") (pin "2") (pinfunction "2_2") (pintype "passive"))
      (node (ref "C25") (pin "2") (pinfunction "2_2") (pintype "passive"))
      (node (ref "C26") (pin "2") (pinfunction "2_2") (pintype "passive"))
      (node (ref "C27") (pin "2") (pinfunction "2_2") (pintype "passive"))
      (node (ref "C28") (pin "2") (pinfunction "2_2") (pintype "passive"))
      (node (ref "C29") (pin "2") (pinfunction "2_2") (pintype "passive"))
      (node (ref "C3") (pin "2") (pinfunction "2_2") (pintype "passive"))
      (node (ref "C30") (pin "2") (pinfunction "2_2") (pintype "passive"))
      (node (ref "C31") (pin "2") (pinfunction "2_2") (pintype "passive"))
      (node (ref "C32") (pin "2") (pinfunction "2_2") (pintype "passive"))
      (node (ref "C33") (pin "2") (pinfunction "2_2") (pintype "passive"))
      (node (ref "C34") (pin "2") (pinfunction "2_2") (pintype "passive"))
      (node (ref "C35") (pin "2") (pinfunction "2_2") (pintype "passive"))
      (node (ref "C4") (pin "2") (pinfunction "2_2") (pintype "passive"))
      (node (ref "C5") (pin "2") (pinfunction "2_2") (pintype "passive"))
      (node (ref "C6") (pin "2") (pinfunction "2_2") (pintype "passive"))
      (node (ref "C7") (pin "2") (pinfunction "2_2") (pintype "passive"))
      (node (ref "C8") (pin "2") (pinfunction "2_2") (pintype "passive"))
      (node (ref "C9") (pin "2") (pinfunction "2_2") (pintype "passive"))
      (node (ref "D2") (pin "A") (pinfunction "A_A") (pintype "passive"))
      (node (ref "ICSP 1") (pin "3") (pinfunction "3_3") (pintype "passive"))
      (node (ref "J1") (pin "HOLE1") (pintype "passive"))
      (node (ref "J1") (pin "HOLE2") (pintype "passive"))
      (node (ref "J2") (pin "HOLE1") (pintype "passive"))
      (node (ref "J2") (pin "HOLE2") (pintype "passive"))
      (node (ref "J3") (pin "5") (pinfunction "GND_5") (pintype "power_in"))
      (node (ref "J3") (pin "6") (pinfunction "MP1_6") (pintype "passive"))
      (node (ref "J3") (pin "7") (pinfunction "MP2_7") (pintype "passive"))
      (node (ref "J3") (pin "8") (pinfunction "MP3_8") (pintype "passive"))
      (node (ref "J3") (pin "9") (pinfunction "MP4_9") (pintype "passive"))
      (node (ref "JDC1") (pin "2") (pinfunction "TN_2") (pintype "passive"))
      (node (ref "JDC1") (pin "3") (pinfunction "S_3") (pintype "power_in"))
      (node (ref "POWER1") (pin "1") (pinfunction "1_1") (pintype "passive"))
      (node (ref "POWER2") (pin "1") (pinfunction "1_1") (pintype "passive"))
      (node (ref "POWER3") (pin "1") (pinfunction "1_1") (pintype "passive"))
      (node (ref "POWER4") (pin "1") (pinfunction "1_1") (pintype "passive"))
      (node (ref "POWER5") (pin "1") (pinfunction "1_1") (pintype "passive"))
      (node (ref "POWER6") (pin "1") (pinfunction "1_1") (pintype "passive"))
      (node (ref "SW1") (pin "2") (pintype "passive"))
      (node (ref "SW1") (pin "4") (pintype "passive"))
      (node (ref "SW2") (pin "2") (pintype "passive"))
      (node (ref "SW2") (pin "4") (pintype "passive"))
      (node (ref "U1") (pin "3") (pinfunction "GND_3") (pintype "passive"))
      (node (ref "U1") (pin "5") (pinfunction "ON/OFF_5") (pintype "passive"))
      (node (ref "U10") (pin "16") (pinfunction "AVSS_16") (pintype "power_in"))
      (node (ref "U10") (pin "29") (pinfunction "VSS_29") (pintype "power_in"))
      (node (ref "U10") (pin "39") (pinfunction "VSS_39") (pintype "power_in"))
      (node (ref "U10") (pin "6") (pinfunction "VSS_6") (pintype "power_in"))
      (node (ref "U11") (pin "12") (pinfunction "GND_12") (pintype "power_in"))
      (node (ref "U12") (pin "12") (pinfunction "GND_12") (pintype "power_in"))
      (node (ref "U13") (pin "12") (pinfunction "GND_12") (pintype "power_in"))
      (node (ref "U14") (pin "12") (pinfunction "GND_12") (pintype "power_in"))
      (node (ref "U15") (pin "12") (pinfunction "GND_12") (pintype "power_in"))
      (node (ref "U16") (pin "12") (pinfunction "GND_12") (pintype "power_in"))
      (node (ref "U17") (pin "12") (pinfunction "GND_12") (pintype "power_in"))
      (node (ref "U18") (pin "12") (pinfunction "GND_12") (pintype "power_in"))
      (node (ref "U19") (pin "12") (pinfunction "VSS_12") (pintype "power_in"))
      (node (ref "U19") (pin "2") (pinfunction "A1_2") (pintype "input"))
      (node (ref "U19") (pin "21") (pinfunction "A0_21") (pintype "input"))
      (node (ref "U19") (pin "3") (pinfunction "A2_3") (pintype "input"))
      (node (ref "U2") (pin "12") (pinfunction "GND_12") (pintype "power_in"))
      (node (ref "U20") (pin "12") (pinfunction "VSS_12") (pintype "power_in"))
      (node (ref "U20") (pin "2") (pinfunction "A1_2") (pintype "input"))
      (node (ref "U20") (pin "21") (pinfunction "A0_21") (pintype "input"))
      (node (ref "U21") (pin "18") (pinfunction "GND_18") (pintype "power_in"))
      (node (ref "U21") (pin "21") (pinfunction "GND_21") (pintype "power_in"))
      (node (ref "U21") (pin "25") (pinfunction "AGND_25") (pintype "power_in"))
      (node (ref "U21") (pin "26") (pinfunction "TEST_26") (pintype "input"))
      (node (ref "U21") (pin "7") (pinfunction "GND_7") (pintype "power_in"))
      (node (ref "U3") (pin "12") (pinfunction "GND_12") (pintype "power_in"))
      (node (ref "U4") (pin "12") (pinfunction "GND_12") (pintype "power_in"))
      (node (ref "U5") (pin "12") (pinfunction "GND_12") (pintype "power_in"))
      (node (ref "U6") (pin "12") (pinfunction "GND_12") (pintype "power_in"))
      (node (ref "U7") (pin "12") (pinfunction "GND_12") (pintype "power_in"))
      (node (ref "U8") (pin "12") (pinfunction "GND_12") (pintype "power_in"))
      (node (ref "U9") (pin "12") (pinfunction "GND_12") (pintype "power_in"))
    )
    (net (code "303") (name "Net-(JDC1-T)") (class "Default")
      (node (ref "D1") (pin "A") (pinfunction "A_A") (pintype "passive"))
      (node (ref "JDC1") (pin "1") (pinfunction "T_1") (pintype "passive"))
    )
    (net (code "304") (name "Net-(POWER1-Pad2)") (class "Default")
      (node (ref "POWER1") (pin "2") (pinfunction "2_2") (pintype "passive"))
      (node (ref "R36") (pin "1") (pinfunction "1_1") (pintype "passive"))
    )
    (net (code "305") (name "Net-(POWER2-Pad2)") (class "Default")
      (node (ref "POWER2") (pin "2") (pinfunction "2_2") (pintype "passive"))
      (node (ref "R76") (pin "1") (pinfunction "1_1") (pintype "passive"))
    )
    (net (code "306") (name "Net-(POWER3-Pad2)") (class "Default")
      (node (ref "POWER3") (pin "2") (pinfunction "2_2") (pintype "passive"))
      (node (ref "R77") (pin "1") (pinfunction "1_1") (pintype "passive"))
    )
    (net (code "307") (name "Net-(POWER4-Pad2)") (class "Default")
      (node (ref "POWER4") (pin "2") (pinfunction "2_2") (pintype "passive"))
      (node (ref "R78") (pin "1") (pinfunction "1_1") (pintype "passive"))
    )
    (net (code "308") (name "Net-(POWER5-Pad2)") (class "Default")
      (node (ref "POWER5") (pin "2") (pinfunction "2_2") (pintype "passive"))
      (node (ref "R79") (pin "1") (pinfunction "1_1") (pintype "passive"))
    )
    (net (code "309") (name "Net-(POWER6-Pad2)") (class "Default")
      (node (ref "POWER6") (pin "2") (pinfunction "2_2") (pintype "passive"))
      (node (ref "R80") (pin "1") (pinfunction "1_1") (pintype "passive"))
    )
    (net (code "310") (name "Net-(POWER7-Pad2)") (class "Default")
      (node (ref "POWER7") (pin "2") (pinfunction "2_2") (pintype "passive"))
      (node (ref "R267") (pin "1") (pinfunction "1_1") (pintype "passive"))
    )
    (net (code "311") (name "Net-(POWER8-Pad2)") (class "Default")
      (node (ref "POWER8") (pin "2") (pinfunction "2_2") (pintype "passive"))
      (node (ref "R268") (pin "1") (pinfunction "1_1") (pintype "passive"))
    )
    (net (code "312") (name "Net-(U1-+VIN)") (class "Default")
      (node (ref "C1") (pin "1") (pinfunction "1_1") (pintype "passive"))
      (node (ref "C2") (pin "1") (pinfunction "1_1") (pintype "passive"))
      (node (ref "D1") (pin "K") (pinfunction "K_K") (pintype "passive"))
      (node (ref "U1") (pin "1") (pinfunction "+VIN_1") (pintype "passive"))
    )
    (net (code "313") (name "Net-(U1-FB)") (class "Default")
      (node (ref "C7") (pin "1") (pinfunction "1_1") (pintype "passive"))
      (node (ref "C8") (pin "1") (pinfunction "1_1") (pintype "passive"))
      (node (ref "L1") (pin "2") (pinfunction "2_2") (pintype "passive"))
      (node (ref "R35") (pin "2") (pinfunction "2_2") (pintype "passive"))
      (node (ref "R36") (pin "2") (pinfunction "2_2") (pintype "passive"))
      (node (ref "U1") (pin "4") (pinfunction "FB_4") (pintype "passive"))
    )
    (net (code "314") (name "Net-(U1-OUTPUT)") (class "Default")
      (node (ref "D2") (pin "K") (pinfunction "K_K") (pintype "passive"))
      (node (ref "L1") (pin "1") (pinfunction "1_1") (pintype "passive"))
      (node (ref "U1") (pin "2") (pinfunction "OUTPUT_2") (pintype "passive"))
    )
    (net (code "315") (name "Net-(U2-Z)") (class "Default")
      (node (ref "R37") (pin "2") (pinfunction "2_2") (pintype "passive"))
      (node (ref "U2") (pin "1") (pinfunction "Z_1") (pintype "bidirectional"))
    )
    (net (code "316") (name "Net-(U3-Z)") (class "Default")
      (node (ref "R38") (pin "2") (pinfunction "2_2") (pintype "passive"))
      (node (ref "U3") (pin "1") (pinfunction "Z_1") (pintype "bidirectional"))
    )
    (net (code "317") (name "Net-(U4-Z)") (class "Default")
      (node (ref "R39") (pin "2") (pinfunction "2_2") (pintype "passive"))
      (node (ref "U4") (pin "1") (pinfunction "Z_1") (pintype "bidirectional"))
    )
    (net (code "318") (name "Net-(U5-Z)") (class "Default")
      (node (ref "R40") (pin "2") (pinfunction "2_2") (pintype "passive"))
      (node (ref "U5") (pin "1") (pinfunction "Z_1") (pintype "bidirectional"))
    )
    (net (code "319") (name "Net-(U6-Z)") (class "Default")
      (node (ref "R81") (pin "2") (pinfunction "2_2") (pintype "passive"))
      (node (ref "U6") (pin "1") (pinfunction "Z_1") (pintype "bidirectional"))
    )
    (net (code "320") (name "Net-(U7-Z)") (class "Default")
      (node (ref "R82") (pin "2") (pinfunction "2_2") (pintype "passive"))
      (node (ref "U7") (pin "1") (pinfunction "Z_1") (pintype "bidirectional"))
    )
    (net (code "321") (name "Net-(U8-Z)") (class "Default")
      (node (ref "R83") (pin "2") (pinfunction "2_2") (pintype "passive"))
      (node (ref "U8") (pin "1") (pinfunction "Z_1") (pintype "bidirectional"))
    )
    (net (code "322") (name "Net-(U9-Z)") (class "Default")
      (node (ref "R84") (pin "2") (pinfunction "2_2") (pintype "passive"))
      (node (ref "U9") (pin "1") (pinfunction "Z_1") (pintype "bidirectional"))
    )
    (net (code "323") (name "Net-(U11-Z)") (class "Default")
      (node (ref "R119") (pin "2") (pinfunction "2_2") (pintype "passive"))
      (node (ref "U11") (pin "1") (pinfunction "Z_1") (pintype "bidirectional"))
    )
    (net (code "324") (name "Net-(U12-Z)") (class "Default")
      (node (ref "R120") (pin "2") (pinfunction "2_2") (pintype "passive"))
      (node (ref "U12") (pin "1") (pinfunction "Z_1") (pintype "bidirectional"))
    )
    (net (code "325") (name "Net-(U13-Z)") (class "Default")
      (node (ref "R121") (pin "2") (pinfunction "2_2") (pintype "passive"))
      (node (ref "U13") (pin "1") (pinfunction "Z_1") (pintype "bidirectional"))
    )
    (net (code "326") (name "Net-(U14-Z)") (class "Default")
      (node (ref "R122") (pin "2") (pinfunction "2_2") (pintype "passive"))
      (node (ref "U14") (pin "1") (pinfunction "Z_1") (pintype "bidirectional"))
    )
    (net (code "327") (name "Net-(U15-Z)") (class "Default")
      (node (ref "R159") (pin "2") (pinfunction "2_2") (pintype "passive"))
      (node (ref "U15") (pin "1") (pinfunction "Z_1") (pintype "bidirectional"))
    )
    (net (code "328") (name "Net-(U16-Z)") (class "Default")
      (node (ref "R160") (pin "2") (pinfunction "2_2") (pintype "passive"))
      (node (ref "U16") (pin "1") (pinfunction "Z_1") (pintype "bidirectional"))
    )
    (net (code "329") (name "Net-(U17-Z)") (class "Default")
      (node (ref "R161") (pin "2") (pinfunction "2_2") (pintype "passive"))
      (node (ref "U17") (pin "1") (pinfunction "Z_1") (pintype "bidirectional"))
    )
    (net (code "330") (name "Net-(U18-Z)") (class "Default")
      (node (ref "R162") (pin "2") (pinfunction "2_2") (pintype "passive"))
      (node (ref "U18") (pin "1") (pinfunction "Z_1") (pintype "bidirectional"))
    )
    (net (code "331") (name "Net-(U19-IO0_0)") (class "Default")
      (node (ref "R236") (pin "2") (pinfunction "2_2") (pintype "passive"))
      (node (ref "U19") (pin "4") (pinfunction "IO0_0_4") (pintype "bidirectional"))
    )
    (net (code "332") (name "Net-(U19-IO0_1)") (class "Default")
      (node (ref "R238") (pin "2") (pinfunction "2_2") (pintype "passive"))
      (node (ref "U19") (pin "5") (pinfunction "IO0_1_5") (pintype "bidirectional"))
    )
    (net (code "333") (name "Net-(U19-IO0_2)") (class "Default")
      (node (ref "R241") (pin "2") (pinfunction "2_2") (pintype "passive"))
      (node (ref "U19") (pin "6") (pinfunction "IO0_2_6") (pintype "bidirectional"))
    )
    (net (code "334") (name "Net-(U19-IO0_3)") (class "Default")
      (node (ref "R243") (pin "2") (pinfunction "2_2") (pintype "passive"))
      (node (ref "U19") (pin "7") (pinfunction "IO0_3_7") (pintype "bidirectional"))
    )
    (net (code "335") (name "Net-(U19-IO0_4)") (class "Default")
      (node (ref "R246") (pin "2") (pinfunction "2_2") (pintype "passive"))
      (node (ref "U19") (pin "8") (pinfunction "IO0_4_8") (pintype "bidirectional"))
    )
    (net (code "336") (name "Net-(U19-IO0_5)") (class "Default")
      (node (ref "R250") (pin "2") (pinfunction "2_2") (pintype "passive"))
      (node (ref "U19") (pin "9") (pinfunction "IO0_5_9") (pintype "bidirectional"))
    )
    (net (code "337") (name "Net-(U19-IO0_6)") (class "Default")
      (node (ref "R254") (pin "2") (pinfunction "2_2") (pintype "passive"))
      (node (ref "U19") (pin "10") (pinfunction "IO0_6_10") (pintype "bidirectional"))
    )
    (net (code "338") (name "Net-(U19-IO0_7)") (class "Default")
      (node (ref "R258") (pin "2") (pinfunction "2_2") (pintype "passive"))
      (node (ref "U19") (pin "11") (pinfunction "IO0_7_11") (pintype "bidirectional"))
    )
    (net (code "339") (name "Net-(U19-IO1_4)") (class "Default")
      (node (ref "R247") (pin "1") (pinfunction "1_1") (pintype "passive"))
      (node (ref "U19") (pin "17") (pinfunction "IO1_4_17") (pintype "bidirectional"))
    )
    (net (code "340") (name "Net-(U19-IO1_5)") (class "Default")
      (node (ref "R251") (pin "1") (pinfunction "1_1") (pintype "passive"))
      (node (ref "U19") (pin "18") (pinfunction "IO1_5_18") (pintype "bidirectional"))
    )
    (net (code "341") (name "Net-(U19-IO1_6)") (class "Default")
      (node (ref "R255") (pin "1") (pinfunction "1_1") (pintype "passive"))
      (node (ref "U19") (pin "19") (pinfunction "IO1_6_19") (pintype "bidirectional"))
    )
    (net (code "342") (name "Net-(U19-IO1_7)") (class "Default")
      (node (ref "R259") (pin "1") (pinfunction "1_1") (pintype "passive"))
      (node (ref "U19") (pin "20") (pinfunction "IO1_7_20") (pintype "bidirectional"))
    )
    (net (code "343") (name "Net-(U19-~{INT})") (class "Default")
      (node (ref "R216") (pin "1") (pinfunction "1_1") (pintype "passive"))
      (node (ref "U19") (pin "1") (pinfunction "~{INT}_1") (pintype "output"))
    )
    (net (code "344") (name "Net-(U20-IO0_0)") (class "Default")
      (node (ref "R237") (pin "2") (pinfunction "2_2") (pintype "passive"))
      (node (ref "U20") (pin "4") (pinfunction "IO0_0_4") (pintype "bidirectional"))
    )
    (net (code "345") (name "Net-(U20-IO0_1)") (class "Default")
      (node (ref "R240") (pin "2") (pinfunction "2_2") (pintype "passive"))
      (node (ref "U20") (pin "5") (pinfunction "IO0_1_5") (pintype "bidirectional"))
    )
    (net (code "346") (name "Net-(U20-IO0_2)") (class "Default")
      (node (ref "R242") (pin "2") (pinfunction "2_2") (pintype "passive"))
      (node (ref "U20") (pin "6") (pinfunction "IO0_2_6") (pintype "bidirectional"))
    )
    (net (code "347") (name "Net-(U20-IO0_3)") (class "Default")
      (node (ref "R244") (pin "2") (pinfunction "2_2") (pintype "passive"))
      (node (ref "U20") (pin "7") (pinfunction "IO0_3_7") (pintype "bidirectional"))
    )
    (net (code "348") (name "Net-(U20-IO0_4)") (class "Default")
      (node (ref "R248") (pin "2") (pinfunction "2_2") (pintype "passive"))
      (node (ref "U20") (pin "8") (pinfunction "IO0_4_8") (pintype "bidirectional"))
    )
    (net (code "349") (name "Net-(U20-IO0_5)") (class "Default")
      (node (ref "R252") (pin "2") (pinfunction "2_2") (pintype "passive"))
      (node (ref "U20") (pin "9") (pinfunction "IO0_5_9") (pintype "bidirectional"))
    )
    (net (code "350") (name "Net-(U20-IO0_6)") (class "Default")
      (node (ref "R256") (pin "2") (pinfunction "2_2") (pintype "passive"))
      (node (ref "U20") (pin "10") (pinfunction "IO0_6_10") (pintype "bidirectional"))
    )
    (net (code "351") (name "Net-(U20-IO0_7)") (class "Default")
      (node (ref "R260") (pin "2") (pinfunction "2_2") (pintype "passive"))
      (node (ref "U20") (pin "11") (pinfunction "IO0_7_11") (pintype "bidirectional"))
    )
    (net (code "352") (name "Net-(U20-IO1_4)") (class "Default")
      (node (ref "R249") (pin "1") (pinfunction "1_1") (pintype "passive"))
      (node (ref "U20") (pin "17") (pinfunction "IO1_4_17") (pintype "bidirectional"))
    )
    (net (code "353") (name "Net-(U20-IO1_5)") (class "Default")
      (node (ref "R253") (pin "1") (pinfunction "1_1") (pintype "passive"))
      (node (ref "U20") (pin "18") (pinfunction "IO1_5_18") (pintype "bidirectional"))
    )
    (net (code "354") (name "Net-(U20-IO1_6)") (class "Default")
      (node (ref "R257") (pin "1") (pinfunction "1_1") (pintype "passive"))
      (node (ref "U20") (pin "19") (pinfunction "IO1_6_19") (pintype "bidirectional"))
    )
    (net (code "355") (name "Net-(U20-IO1_7)") (class "Default")
      (node (ref "R261") (pin "1") (pinfunction "1_1") (pintype "passive"))
      (node (ref "U20") (pin "20") (pinfunction "IO1_7_20") (pintype "bidirectional"))
    )
    (net (code "356") (name "Net-(U20-SCL)") (class "Default")
      (node (ref "R215") (pin "2") (pinfunction "2_2") (pintype "passive"))
      (node (ref "R219") (pin "1") (pinfunction "1_1") (pintype "passive"))
      (node (ref "R239") (pin "1") (pinfunction "1_1") (pintype "passive"))
      (node (ref "U20") (pin "22") (pinfunction "SCL_22") (pintype "input"))
    )
    (net (code "357") (name "Net-(U20-SDA)") (class "Default")
      (node (ref "R214") (pin "2") (pinfunction "2_2") (pintype "passive"))
      (node (ref "R263") (pin "1") (pinfunction "1_1") (pintype "passive"))
      (node (ref "R265") (pin "1") (pinfunction "1_1") (pintype "passive"))
      (node (ref "U20") (pin "23") (pinfunction "SDA_23") (pintype "bidirectional"))
    )
    (net (code "358") (name "Net-(U20-~{INT})") (class "Default")
      (node (ref "R217") (pin "1") (pinfunction "1_1") (pintype "passive"))
      (node (ref "U20") (pin "1") (pinfunction "~{INT}_1") (pintype "output"))
    )
    (net (code "359") (name "Net-(U21-CBUS0)") (class "Default")
      (node (ref "POWER7") (pin "1") (pinfunction "1_1") (pintype "passive"))
      (node (ref "U21") (pin "23") (pinfunction "CBUS0_23") (pintype "bidirectional"))
    )
    (net (code "360") (name "Net-(U21-CBUS1)") (class "Default")
      (node (ref "POWER8") (pin "1") (pinfunction "1_1") (pintype "passive"))
      (node (ref "U21") (pin "22") (pinfunction "CBUS1_22") (pintype "bidirectional"))
    )
    (net (code "361") (name "Net-(U21-RXD)") (class "Default")
      (node (ref "R266") (pin "1") (pinfunction "1_1") (pintype "passive"))
      (node (ref "U21") (pin "5") (pinfunction "RXD_5") (pintype "input"))
    )
    (net (code "362") (name "Net-(U21-TXD)") (class "Default")
      (node (ref "R264") (pin "1") (pinfunction "1_1") (pintype "passive"))
      (node (ref "U21") (pin "1") (pinfunction "TXD_1") (pintype "output"))
    )
    (net (code "363") (name "VCC_USB") (class "Default")
      (node (ref "C32") (pin "1") (pinfunction "1_1") (pintype "passive"))
      (node (ref "C33") (pin "1") (pinfunction "1_1") (pintype "passive"))
      (node (ref "C34") (pin "1") (pinfunction "1_1") (pintype "passive"))
      (node (ref "R245") (pin "1") (pinfunction "1_1") (pintype "passive"))
      (node (ref "R267") (pin "2") (pinfunction "2_2") (pintype "passive"))
      (node (ref "R268") (pin "2") (pinfunction "2_2") (pintype "passive"))
      (node (ref "U21") (pin "20") (pinfunction "VCC_20") (pintype "power_in"))
      (node (ref "U21") (pin "4") (pinfunction "VCCIO_4") (pintype "power_in"))
    )
    (net (code "364") (name "VDD_MCU") (class "Default")
      (node (ref "C13") (pin "1") (pinfunction "1_1") (pintype "passive"))
      (node (ref "C14") (pin "1") (pinfunction "1_1") (pintype "passive"))
      (node (ref "C15") (pin "1") (pinfunction "1_1") (pintype "passive"))
      (node (ref "C16") (pin "1") (pinfunction "1_1") (pintype "passive"))
      (node (ref "C17") (pin "1") (pinfunction "1_1") (pintype "passive"))
      (node (ref "ICSP 1") (pin "2") (pinfunction "2_2") (pintype "passive"))
      (node (ref "R157") (pin "1") (pinfunction "1_1") (pintype "passive"))
      (node (ref "R75") (pin "1") (pinfunction "1_1") (pintype "passive"))
      (node (ref "U10") (pin "17") (pinfunction "AVDD_17") (pintype "power_in"))
      (node (ref "U10") (pin "28") (pinfunction "VDD_28") (pintype "power_in"))
      (node (ref "U10") (pin "40") (pinfunction "VDD_40") (pintype "power_in"))
      (node (ref "U10") (pin "7") (pinfunction "VDD_7") (pintype "power_in"))
    )
    (net (code "365") (name "unconnected-(J3-ID-Pad4)") (class "Default")
      (node (ref "J3") (pin "4") (pinfunction "ID_4") (pintype "passive+no_connect"))
    )
    (net (code "366") (name "unconnected-(U10-NC-Pad12)") (class "Default")
      (node (ref "U10") (pin "12") (pinfunction "NC_12") (pintype "passive+no_connect"))
    )
    (net (code "367") (name "unconnected-(U10-NC-Pad13)") (class "Default")
      (node (ref "U10") (pin "13") (pinfunction "NC_13") (pintype "passive+no_connect"))
    )
    (net (code "368") (name "unconnected-(U10-NC-Pad33)") (class "Default")
      (node (ref "U10") (pin "33") (pinfunction "NC_33") (pintype "passive+no_connect"))
    )
    (net (code "369") (name "unconnected-(U10-NC-Pad34)") (class "Default")
      (node (ref "U10") (pin "34") (pinfunction "NC_34") (pintype "passive+no_connect"))
    )
    (net (code "370") (name "unconnected-(U16-Y4-Pad5)") (class "Default")
      (node (ref "U16") (pin "5") (pinfunction "Y4_5") (pintype "bidirectional+no_connect"))
    )
    (net (code "371") (name "unconnected-(U16-Y5-Pad4)") (class "Default")
      (node (ref "U16") (pin "4") (pinfunction "Y5_4") (pintype "bidirectional+no_connect"))
    )
    (net (code "372") (name "unconnected-(U16-Y6-Pad3)") (class "Default")
      (node (ref "U16") (pin "3") (pinfunction "Y6_3") (pintype "bidirectional+no_connect"))
    )
    (net (code "373") (name "unconnected-(U16-Y7-Pad2)") (class "Default")
      (node (ref "U16") (pin "2") (pinfunction "Y7_2") (pintype "bidirectional+no_connect"))
    )
    (net (code "374") (name "unconnected-(U16-Y8-Pad23)") (class "Default")
      (node (ref "U16") (pin "23") (pinfunction "Y8_23") (pintype "bidirectional+no_connect"))
    )
    (net (code "375") (name "unconnected-(U16-Y9-Pad22)") (class "Default")
      (node (ref "U16") (pin "22") (pinfunction "Y9_22") (pintype "bidirectional+no_connect"))
    )
    (net (code "376") (name "unconnected-(U16-Y10-Pad21)") (class "Default")
      (node (ref "U16") (pin "21") (pinfunction "Y10_21") (pintype "bidirectional+no_connect"))
    )
    (net (code "377") (name "unconnected-(U16-Y11-Pad20)") (class "Default")
      (node (ref "U16") (pin "20") (pinfunction "Y11_20") (pintype "bidirectional+no_connect"))
    )
    (net (code "378") (name "unconnected-(U16-Y12-Pad19)") (class "Default")
      (node (ref "U16") (pin "19") (pinfunction "Y12_19") (pintype "bidirectional+no_connect"))
    )
    (net (code "379") (name "unconnected-(U16-Y13-Pad18)") (class "Default")
      (node (ref "U16") (pin "18") (pinfunction "Y13_18") (pintype "bidirectional+no_connect"))
    )
    (net (code "380") (name "unconnected-(U16-Y14-Pad17)") (class "Default")
      (node (ref "U16") (pin "17") (pinfunction "Y14_17") (pintype "bidirectional+no_connect"))
    )
    (net (code "381") (name "unconnected-(U16-Y15-Pad16)") (class "Default")
      (node (ref "U16") (pin "16") (pinfunction "Y15_16") (pintype "bidirectional+no_connect"))
    )
    (net (code "382") (name "unconnected-(U18-Y4-Pad5)") (class "Default")
      (node (ref "U18") (pin "5") (pinfunction "Y4_5") (pintype "bidirectional+no_connect"))
    )
    (net (code "383") (name "unconnected-(U18-Y5-Pad4)") (class "Default")
      (node (ref "U18") (pin "4") (pinfunction "Y5_4") (pintype "bidirectional+no_connect"))
    )
    (net (code "384") (name "unconnected-(U18-Y6-Pad3)") (class "Default")
      (node (ref "U18") (pin "3") (pinfunction "Y6_3") (pintype "bidirectional+no_connect"))
    )
    (net (code "385") (name "unconnected-(U18-Y7-Pad2)") (class "Default")
      (node (ref "U18") (pin "2") (pinfunction "Y7_2") (pintype "bidirectional+no_connect"))
    )
    (net (code "386") (name "unconnected-(U18-Y8-Pad23)") (class "Default")
      (node (ref "U18") (pin "23") (pinfunction "Y8_23") (pintype "bidirectional+no_connect"))
    )
    (net (code "387") (name "unconnected-(U18-Y9-Pad22)") (class "Default")
      (node (ref "U18") (pin "22") (pinfunction "Y9_22") (pintype "bidirectional+no_connect"))
    )
    (net (code "388") (name "unconnected-(U18-Y10-Pad21)") (class "Default")
      (node (ref "U18") (pin "21") (pinfunction "Y10_21") (pintype "bidirectional+no_connect"))
    )
    (net (code "389") (name "unconnected-(U18-Y11-Pad20)") (class "Default")
      (node (ref "U18") (pin "20") (pinfunction "Y11_20") (pintype "bidirectional+no_connect"))
    )
    (net (code "390") (name "unconnected-(U18-Y12-Pad19)") (class "Default")
      (node (ref "U18") (pin "19") (pinfunction "Y12_19") (pintype "bidirectional+no_connect"))
    )
    (net (code "391") (name "unconnected-(U18-Y13-Pad18)") (class "Default")
      (node (ref "U18") (pin "18") (pinfunction "Y13_18") (pintype "bidirectional+no_connect"))
    )
    (net (code "392") (name "unconnected-(U18-Y14-Pad17)") (class "Default")
      (node (ref "U18") (pin "17") (pinfunction "Y14_17") (pintype "bidirectional+no_connect"))
    )
    (net (code "393") (name "unconnected-(U18-Y15-Pad16)") (class "Default")
      (node (ref "U18") (pin "16") (pinfunction "Y15_16") (pintype "bidirectional+no_connect"))
    )
    (net (code "394") (name "unconnected-(U19-IO1_0-Pad13)") (class "Default")
      (node (ref "U19") (pin "13") (pinfunction "IO1_0_13") (pintype "bidirectional+no_connect"))
    )
    (net (code "395") (name "unconnected-(U19-IO1_1-Pad14)") (class "Default")
      (node (ref "U19") (pin "14") (pinfunction "IO1_1_14") (pintype "bidirectional+no_connect"))
    )
    (net (code "396") (name "unconnected-(U19-IO1_2-Pad15)") (class "Default")
      (node (ref "U19") (pin "15") (pinfunction "IO1_2_15") (pintype "bidirectional+no_connect"))
    )
    (net (code "397") (name "unconnected-(U19-IO1_3-Pad16)") (class "Default")
      (node (ref "U19") (pin "16") (pinfunction "IO1_3_16") (pintype "bidirectional+no_connect"))
    )
    (net (code "398") (name "unconnected-(U20-IO1_0-Pad13)") (class "Default")
      (node (ref "U20") (pin "13") (pinfunction "IO1_0_13") (pintype "bidirectional+no_connect"))
    )
    (net (code "399") (name "unconnected-(U20-IO1_1-Pad14)") (class "Default")
      (node (ref "U20") (pin "14") (pinfunction "IO1_1_14") (pintype "bidirectional+no_connect"))
    )
    (net (code "400") (name "unconnected-(U20-IO1_2-Pad15)") (class "Default")
      (node (ref "U20") (pin "15") (pinfunction "IO1_2_15") (pintype "bidirectional+no_connect"))
    )
    (net (code "401") (name "unconnected-(U20-IO1_3-Pad16)") (class "Default")
      (node (ref "U20") (pin "16") (pinfunction "IO1_3_16") (pintype "bidirectional+no_connect"))
    )
    (net (code "402") (name "unconnected-(U21-CBUS2-Pad13)") (class "Default")
      (node (ref "U21") (pin "13") (pinfunction "CBUS2_13") (pintype "bidirectional+no_connect"))
    )
    (net (code "403") (name "unconnected-(U21-CBUS3-Pad14)") (class "Default")
      (node (ref "U21") (pin "14") (pinfunction "CBUS3_14") (pintype "bidirectional+no_connect"))
    )
    (net (code "404") (name "unconnected-(U21-CBUS4-Pad12)") (class "Default")
      (node (ref "U21") (pin "12") (pinfunction "CBUS4_12") (pintype "bidirectional+no_connect"))
    )
    (net (code "405") (name "unconnected-(U21-NC-Pad8)") (class "Default")
      (node (ref "U21") (pin "8") (pinfunction "NC_8") (pintype "passive+no_connect"))
    )
    (net (code "406") (name "unconnected-(U21-NC-Pad24)") (class "Default")
      (node (ref "U21") (pin "24") (pinfunction "NC_24") (pintype "passive+no_connect"))
    )
    (net (code "407") (name "unconnected-(U21-OSCI-Pad27)") (class "Default")
      (node (ref "U21") (pin "27") (pinfunction "OSCI_27") (pintype "input+no_connect"))
    )
    (net (code "408") (name "unconnected-(U21-OSCO-Pad28)") (class "Default")
      (node (ref "U21") (pin "28") (pinfunction "OSCO_28") (pintype "output+no_connect"))
    )
    (net (code "409") (name "unconnected-(U21-~{CTS}-Pad11)") (class "Default")
      (node (ref "U21") (pin "11") (pinfunction "~{CTS}_11") (pintype "input+no_connect"))
    )
    (net (code "410") (name "unconnected-(U21-~{DCD}-Pad10)") (class "Default")
      (node (ref "U21") (pin "10") (pinfunction "~{DCD}_10") (pintype "input+no_connect"))
    )
    (net (code "411") (name "unconnected-(U21-~{DSR}-Pad9)") (class "Default")
      (node (ref "U21") (pin "9") (pinfunction "~{DSR}_9") (pintype "input+no_connect"))
    )
    (net (code "412") (name "unconnected-(U21-~{DTR}-Pad2)") (class "Default")
      (node (ref "U21") (pin "2") (pinfunction "~{DTR}_2") (pintype "output+no_connect"))
    )
    (net (code "413") (name "unconnected-(U21-~{RESET}-Pad19)") (class "Default")
      (node (ref "U21") (pin "19") (pinfunction "~{RESET}_19") (pintype "input+no_connect"))
    )
    (net (code "414") (name "unconnected-(U21-~{RI}-Pad6)") (class "Default")
      (node (ref "U21") (pin "6") (pinfunction "~{RI}_6") (pintype "input+no_connect"))
    )
    (net (code "415") (name "unconnected-(U21-~{RTS}-Pad3)") (class "Default")
      (node (ref "U21") (pin "3") (pinfunction "~{RTS}_3") (pintype "output+no_connect"))
    )
    (net (code "416") (name "unconnected-(VIT1-1-PadVIT1)") (class "Default")
      (node (ref "VIT1") (pin "VIT1") (pinfunction "1_VIT1") (pintype "passive+no_connect"))
    )
    (net (code "417") (name "unconnected-(VIT2-1-PadVIT1)") (class "Default")
      (node (ref "VIT2") (pin "VIT1") (pinfunction "1_VIT1") (pintype "passive+no_connect"))
    )
    (net (code "418") (name "unconnected-(VIT3-1-PadVIT1)") (class "Default")
      (node (ref "VIT3") (pin "VIT1") (pinfunction "1_VIT1") (pintype "passive+no_connect"))
    )
    (net (code "419") (name "unconnected-(VIT4-1-PadVIT1)") (class "Default")
      (node (ref "VIT4") (pin "VIT1") (pinfunction "1_VIT1") (pintype "passive+no_connect"))
    )
  )
)
